# ESense.net
KiCad netlist of a schematic drawn in Altium Designer
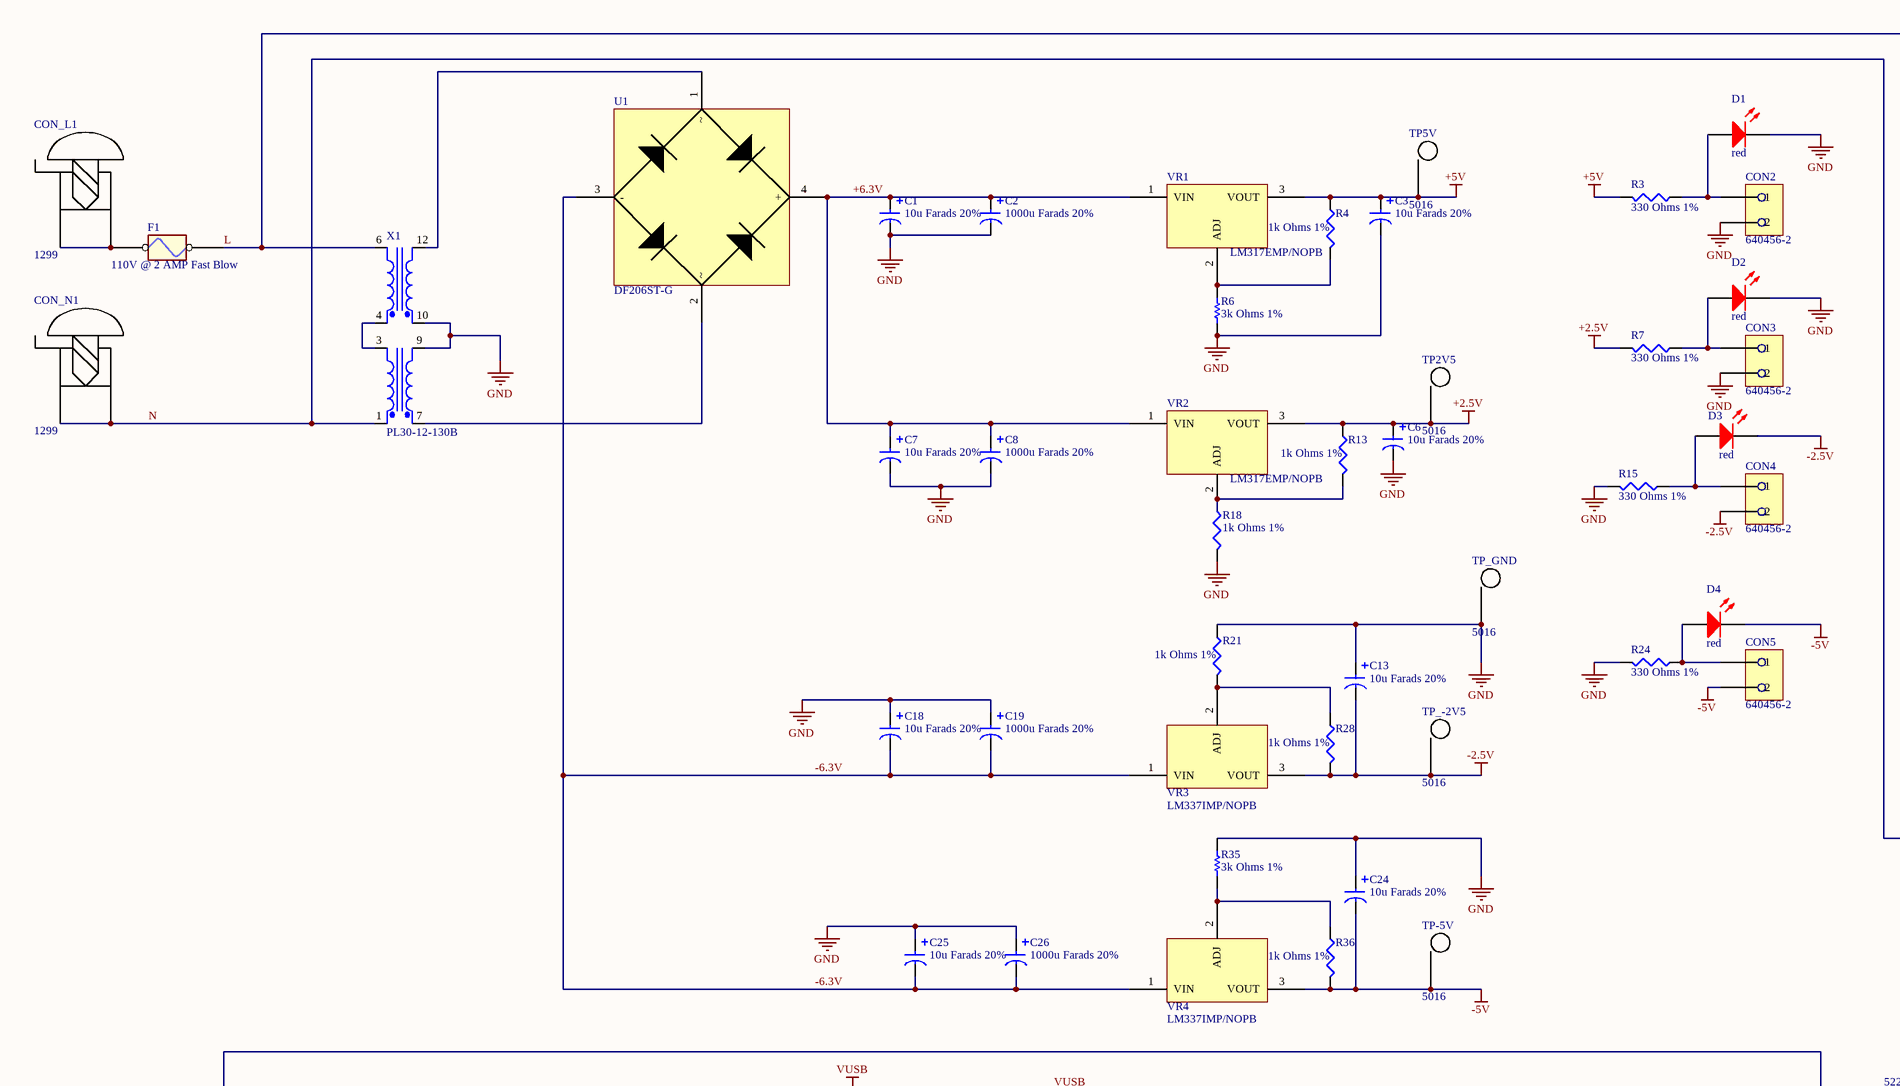
[diagram p0: ESense.SchDoc, top left]
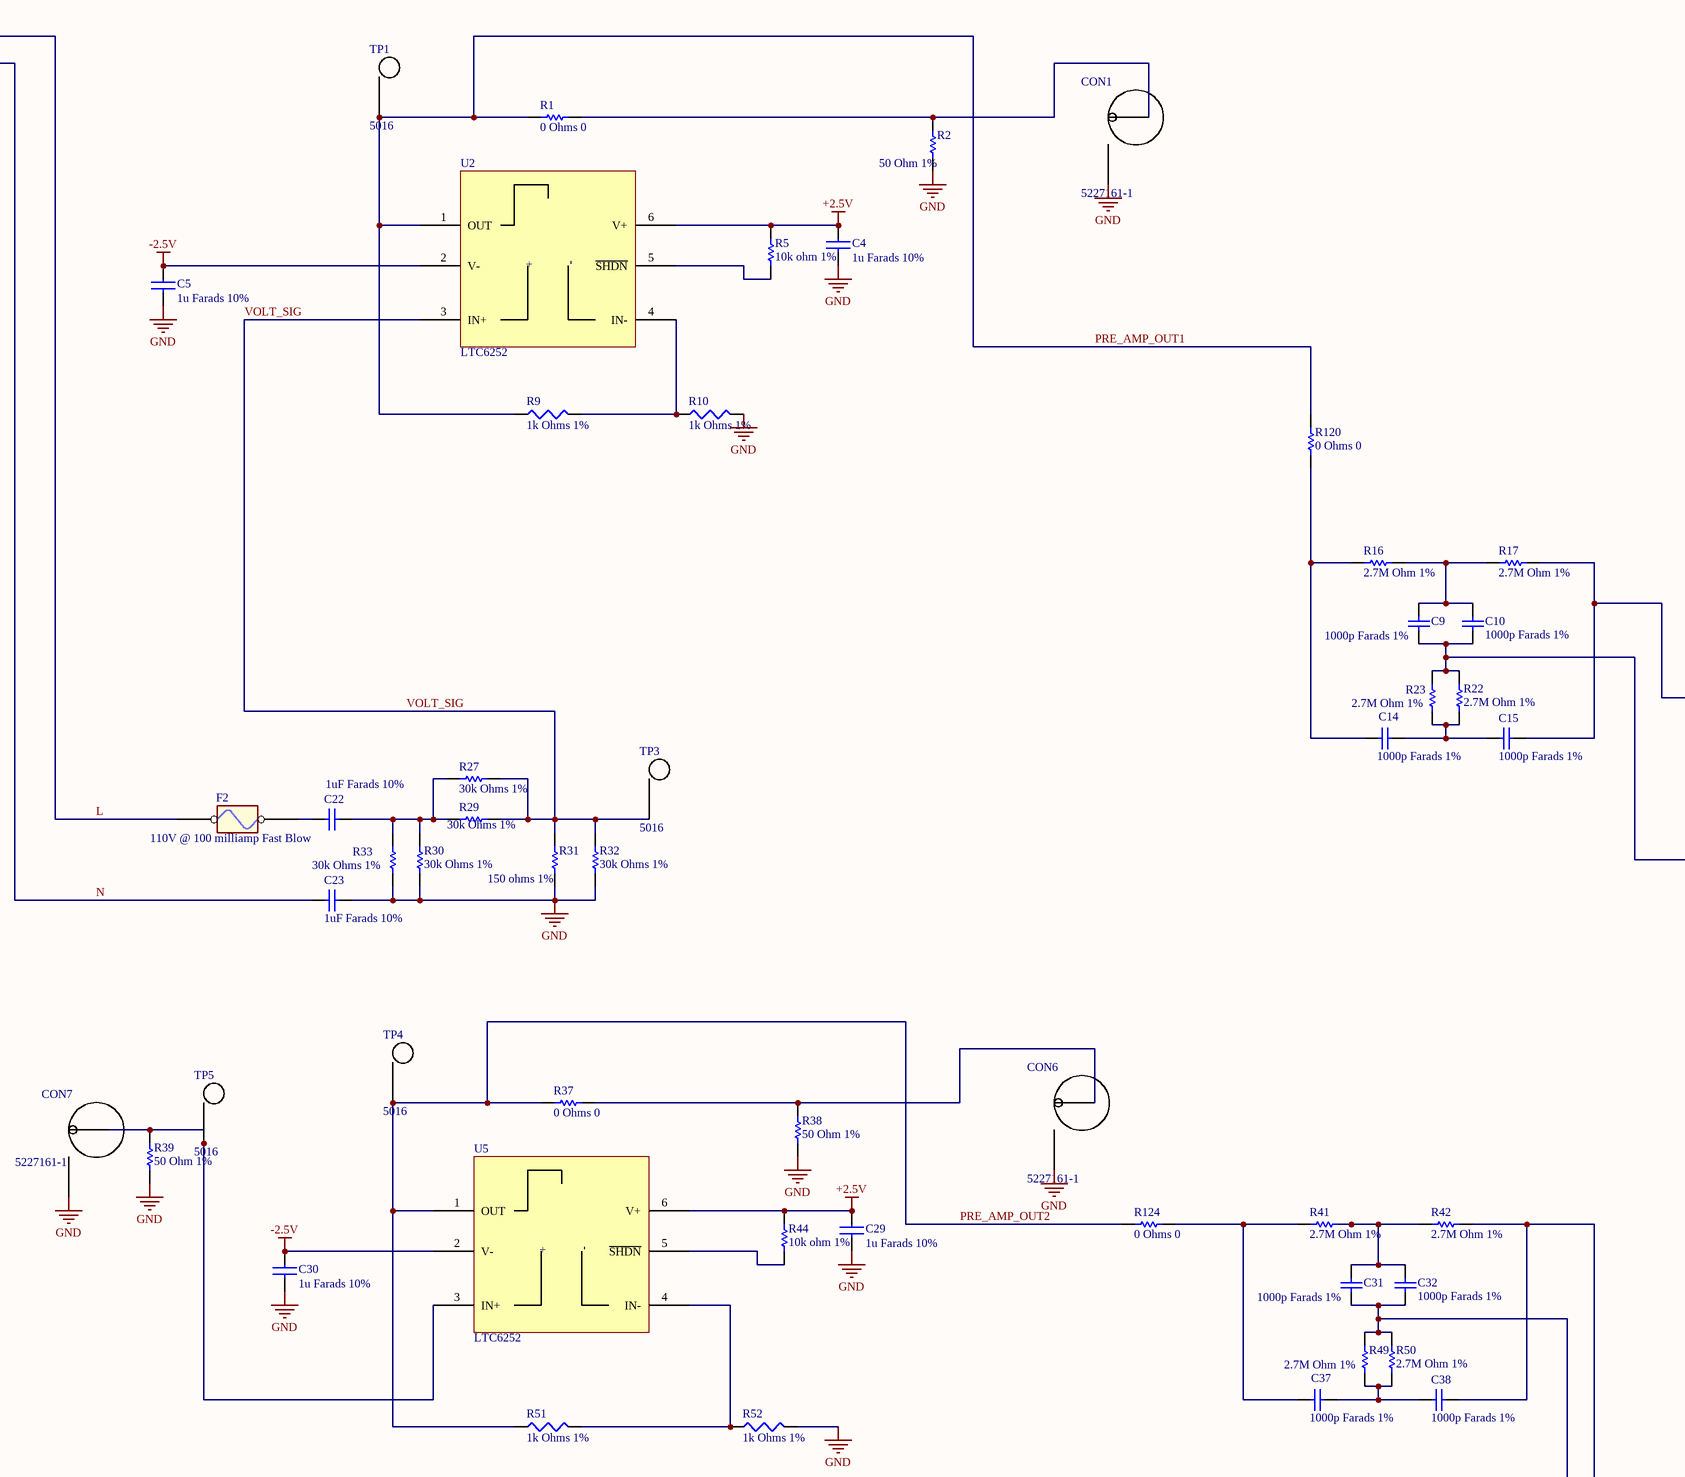
[diagram p1: ESense.SchDoc, top middle]
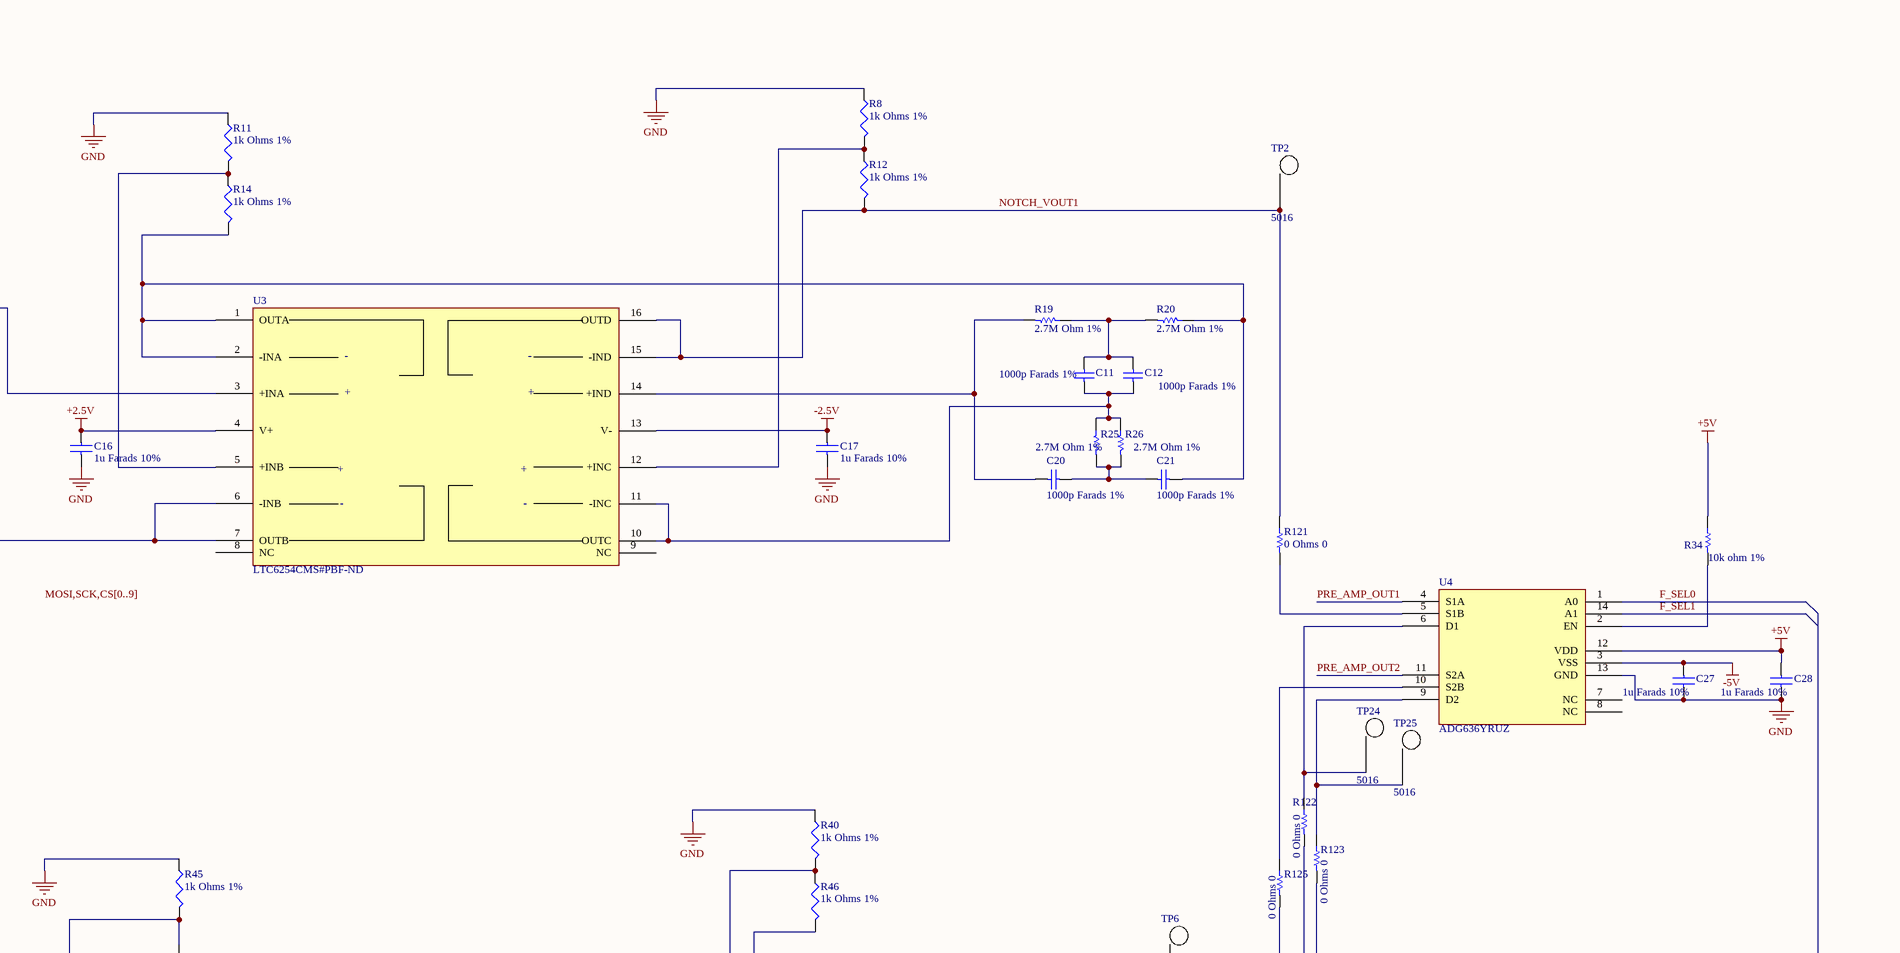
[diagram p2: ESense.SchDoc, top right]
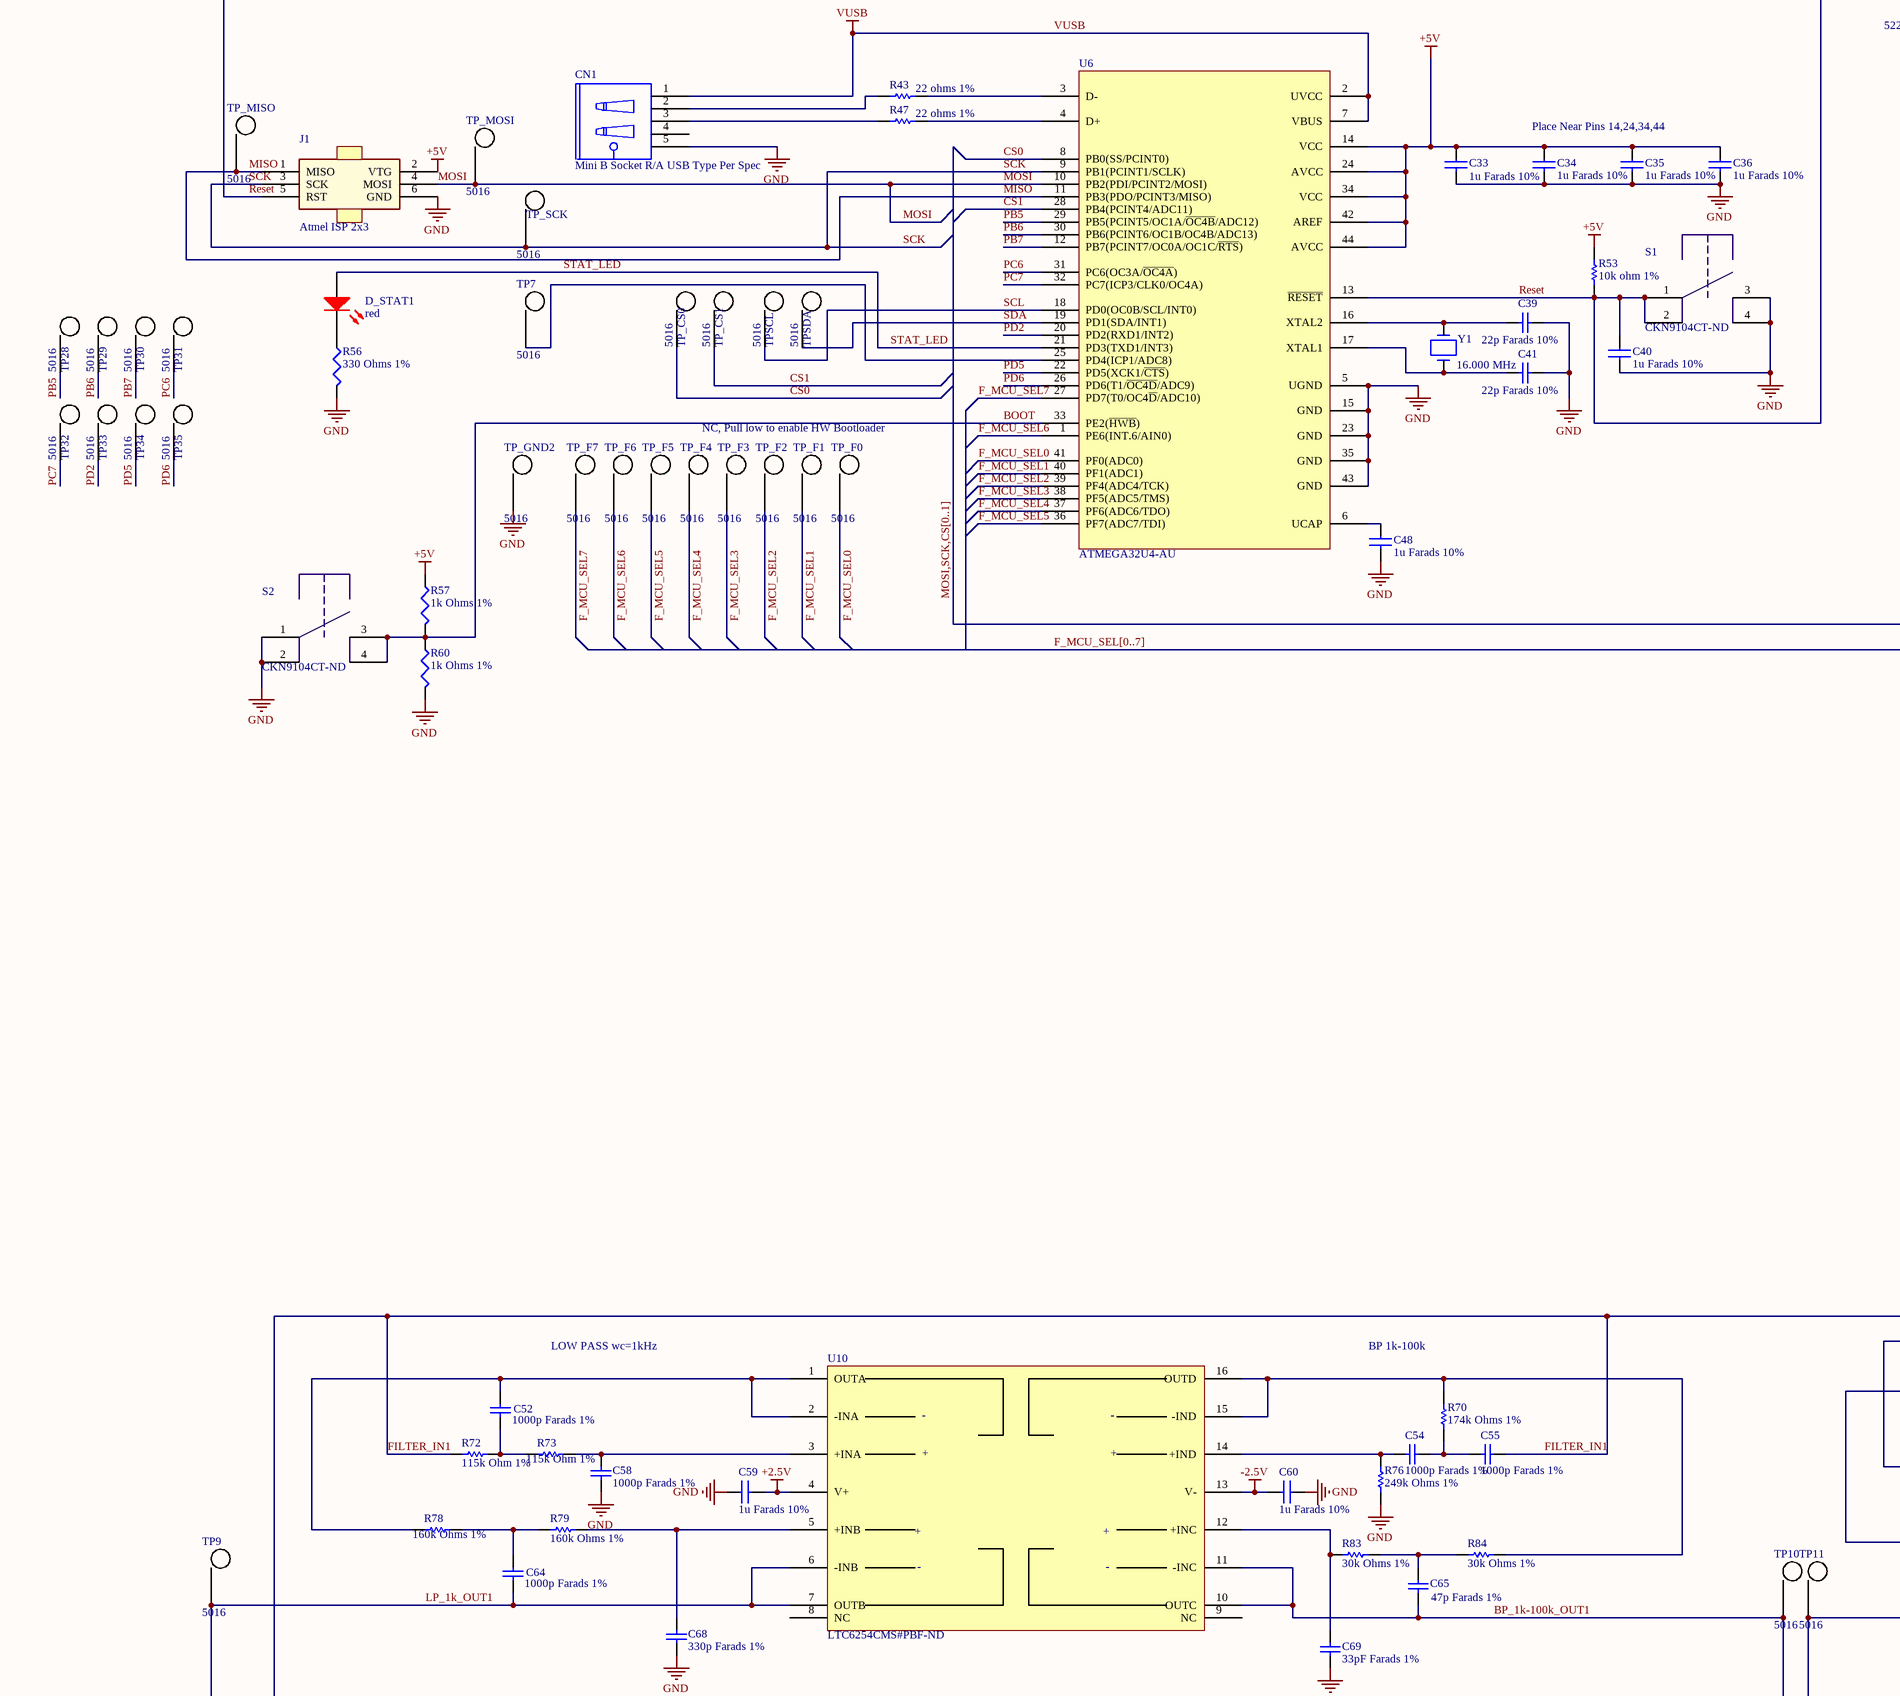
[diagram p3: ESense.SchDoc, centre left]
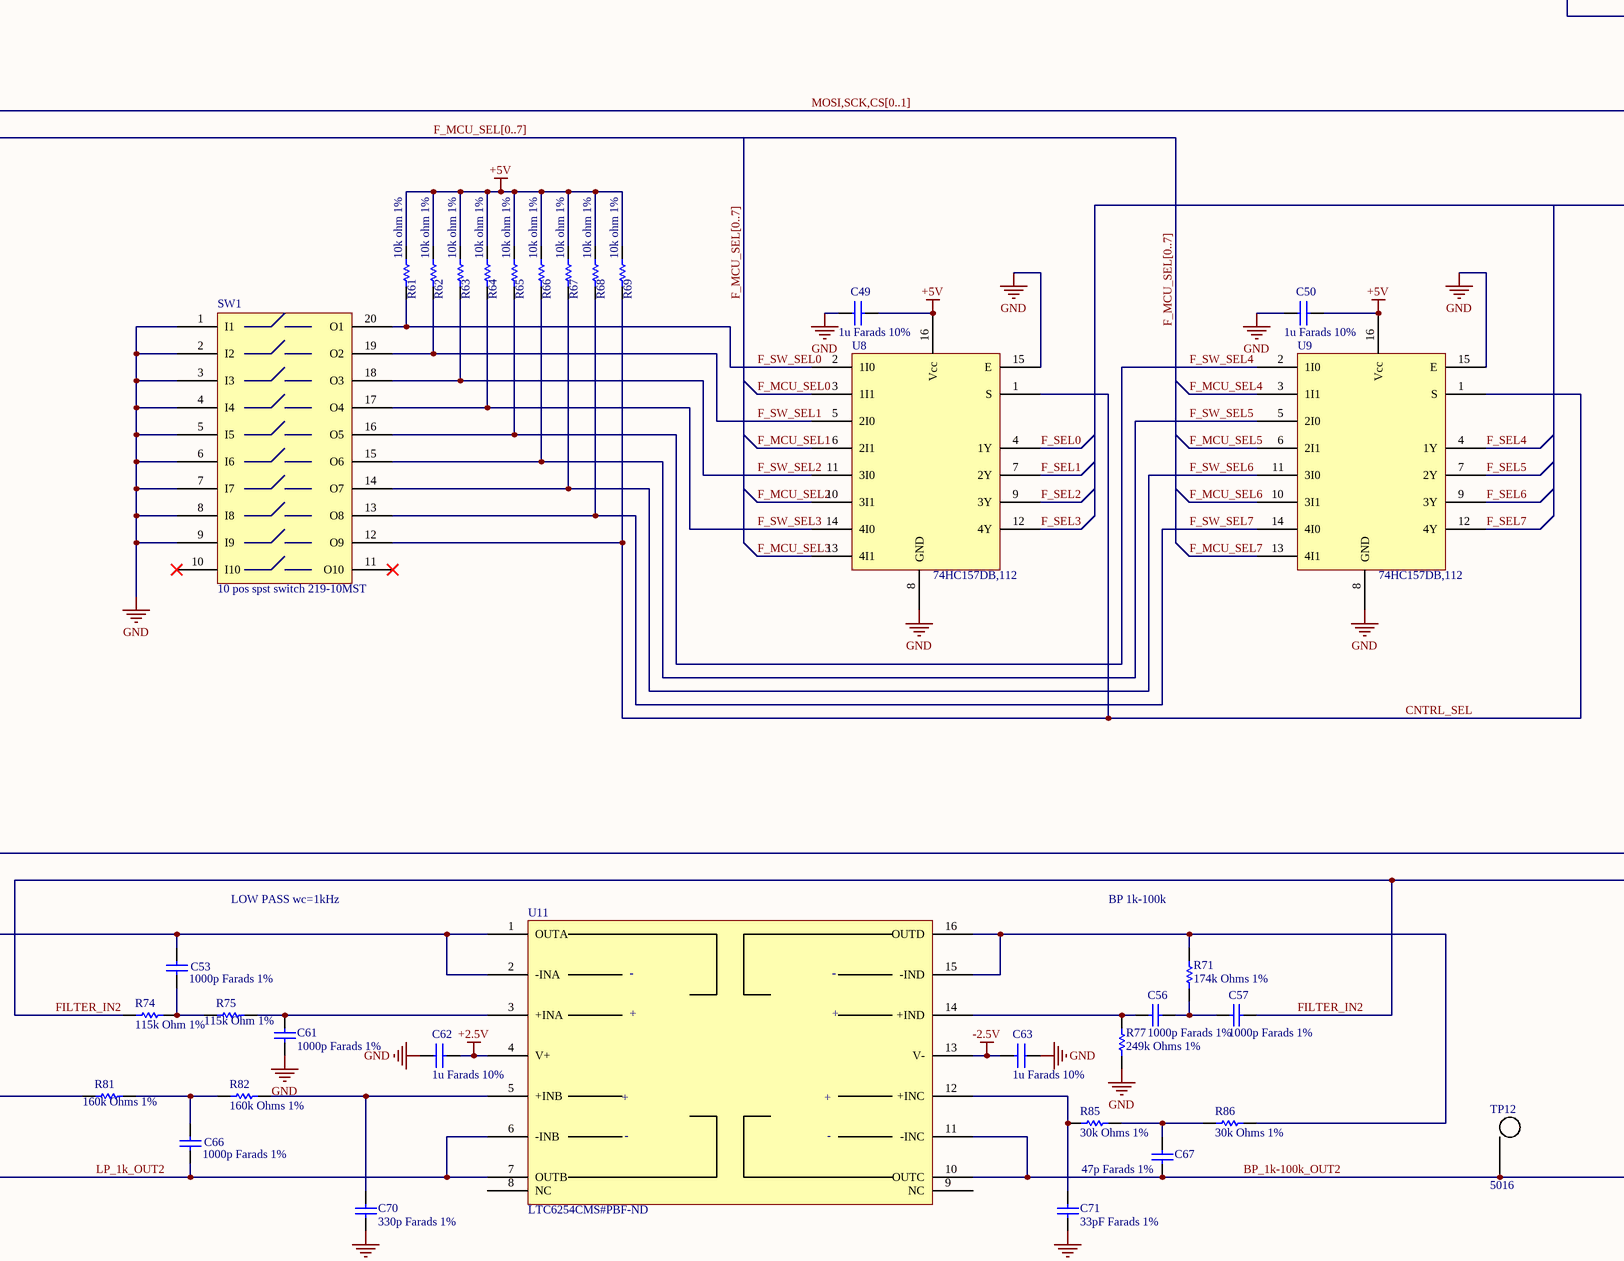
[diagram p4: ESense.SchDoc, centre middle]
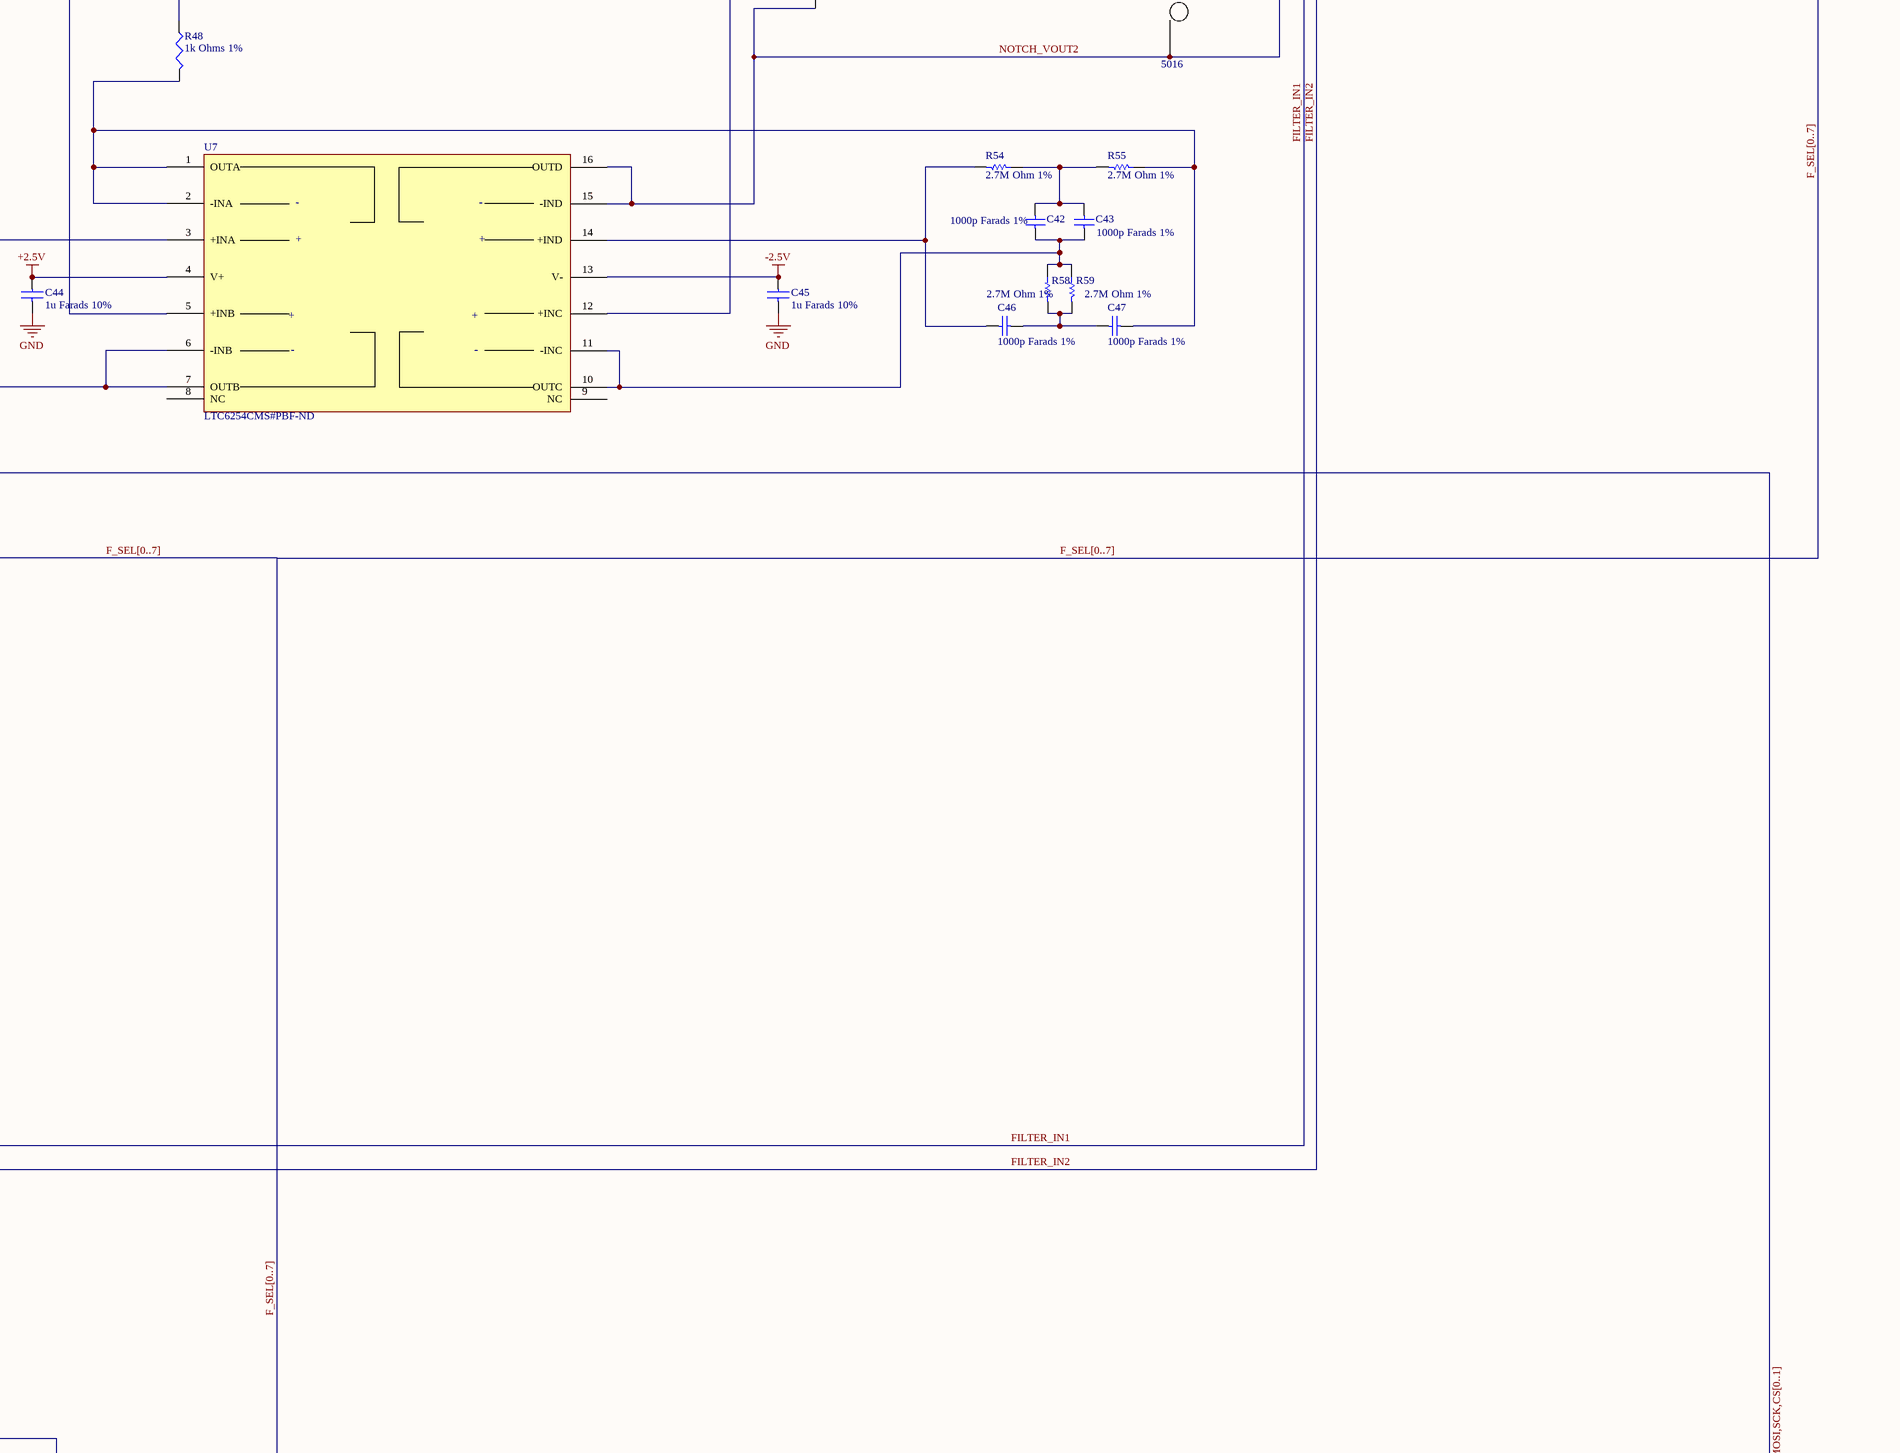
[diagram p5: ESense.SchDoc, centre right]
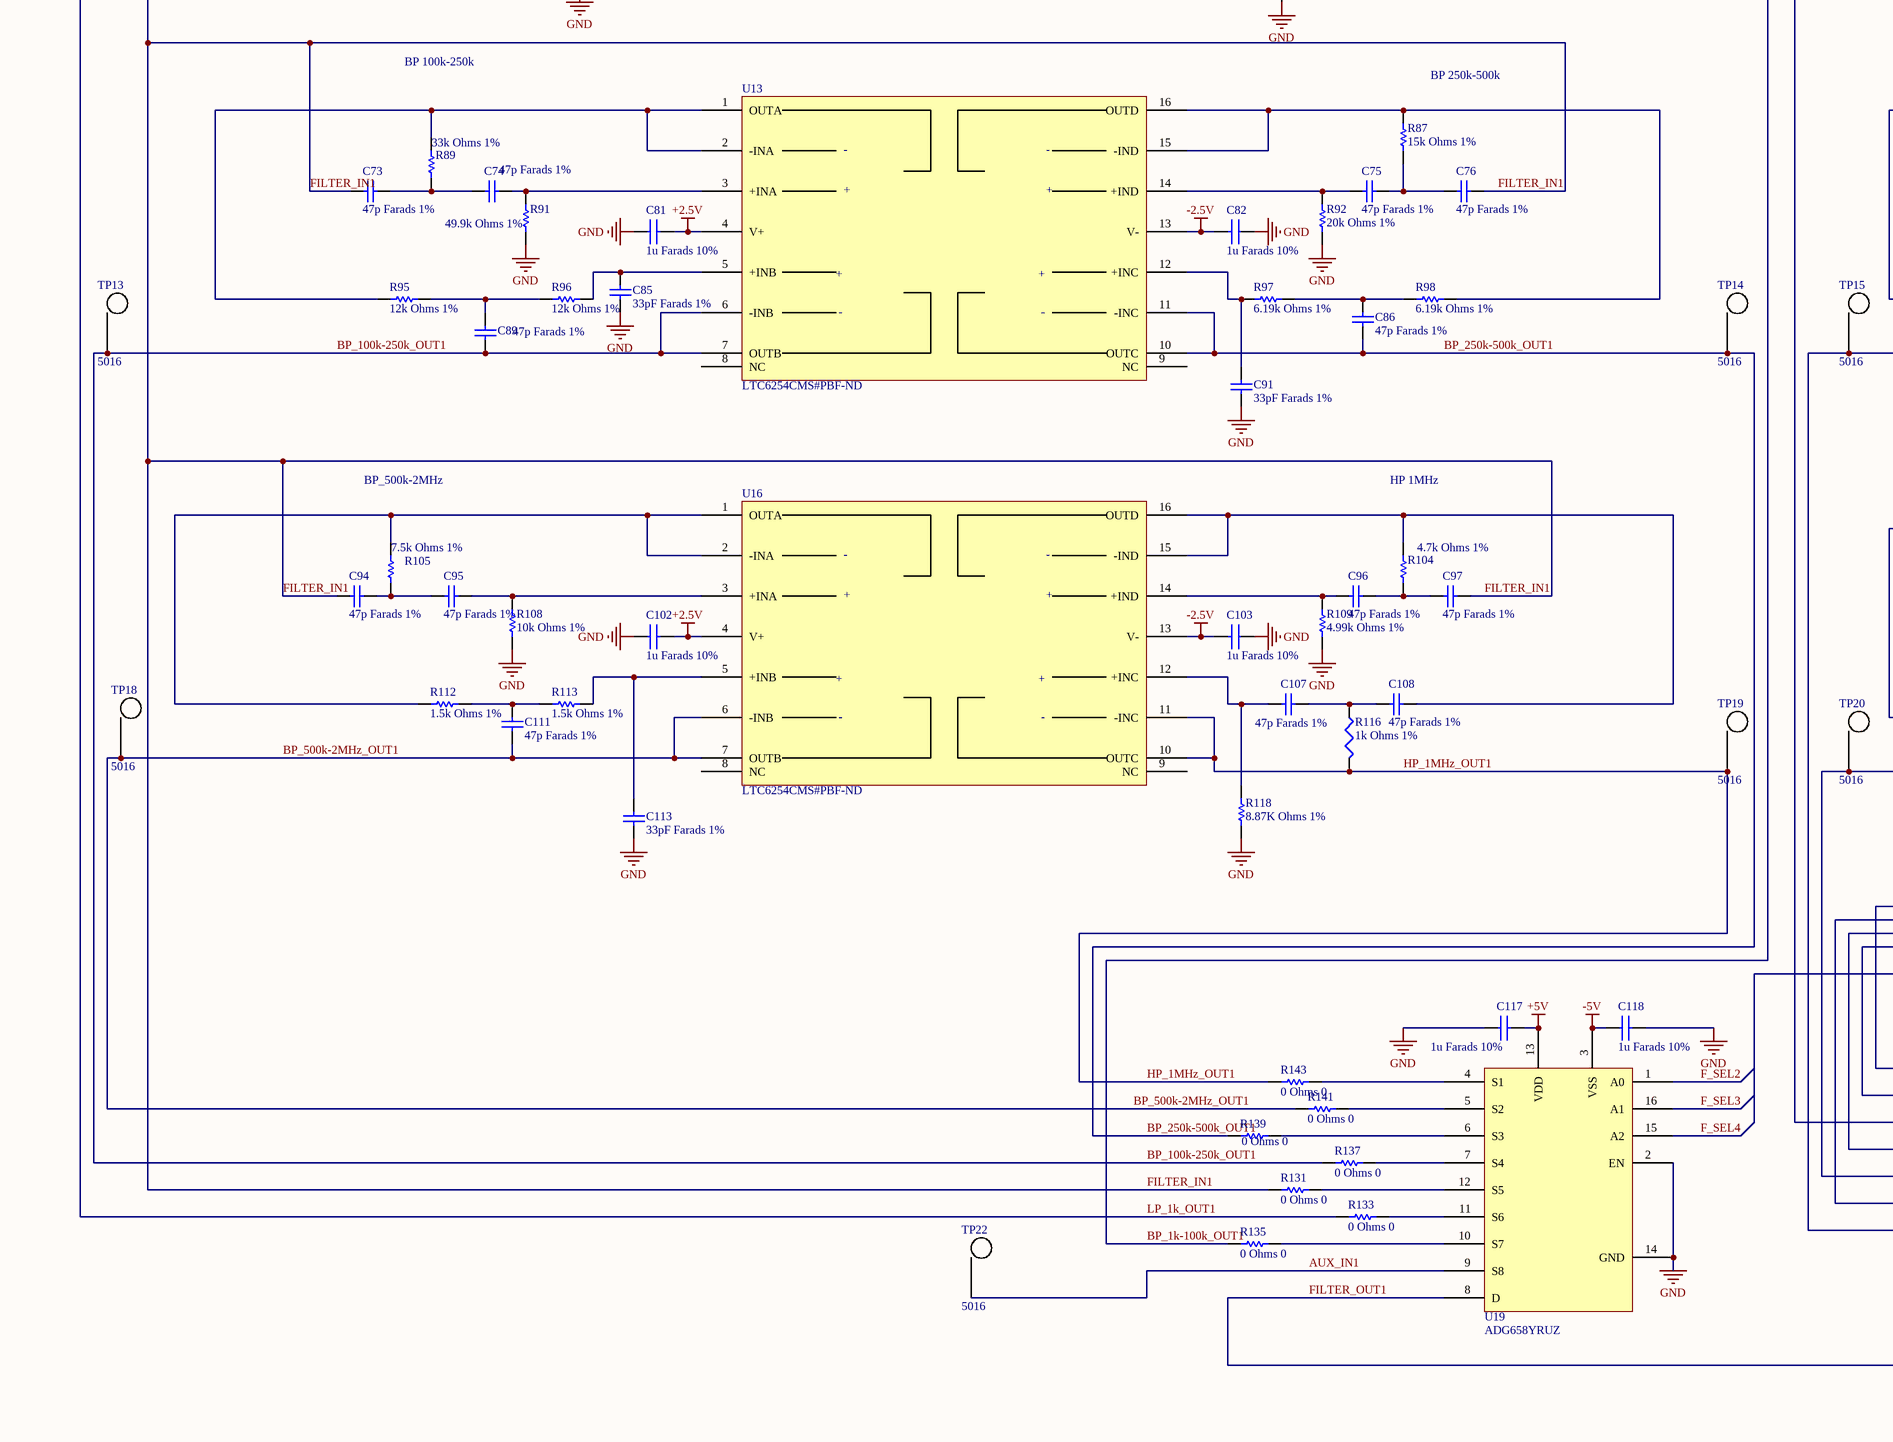
[diagram p6: ESense.SchDoc, bottom left]
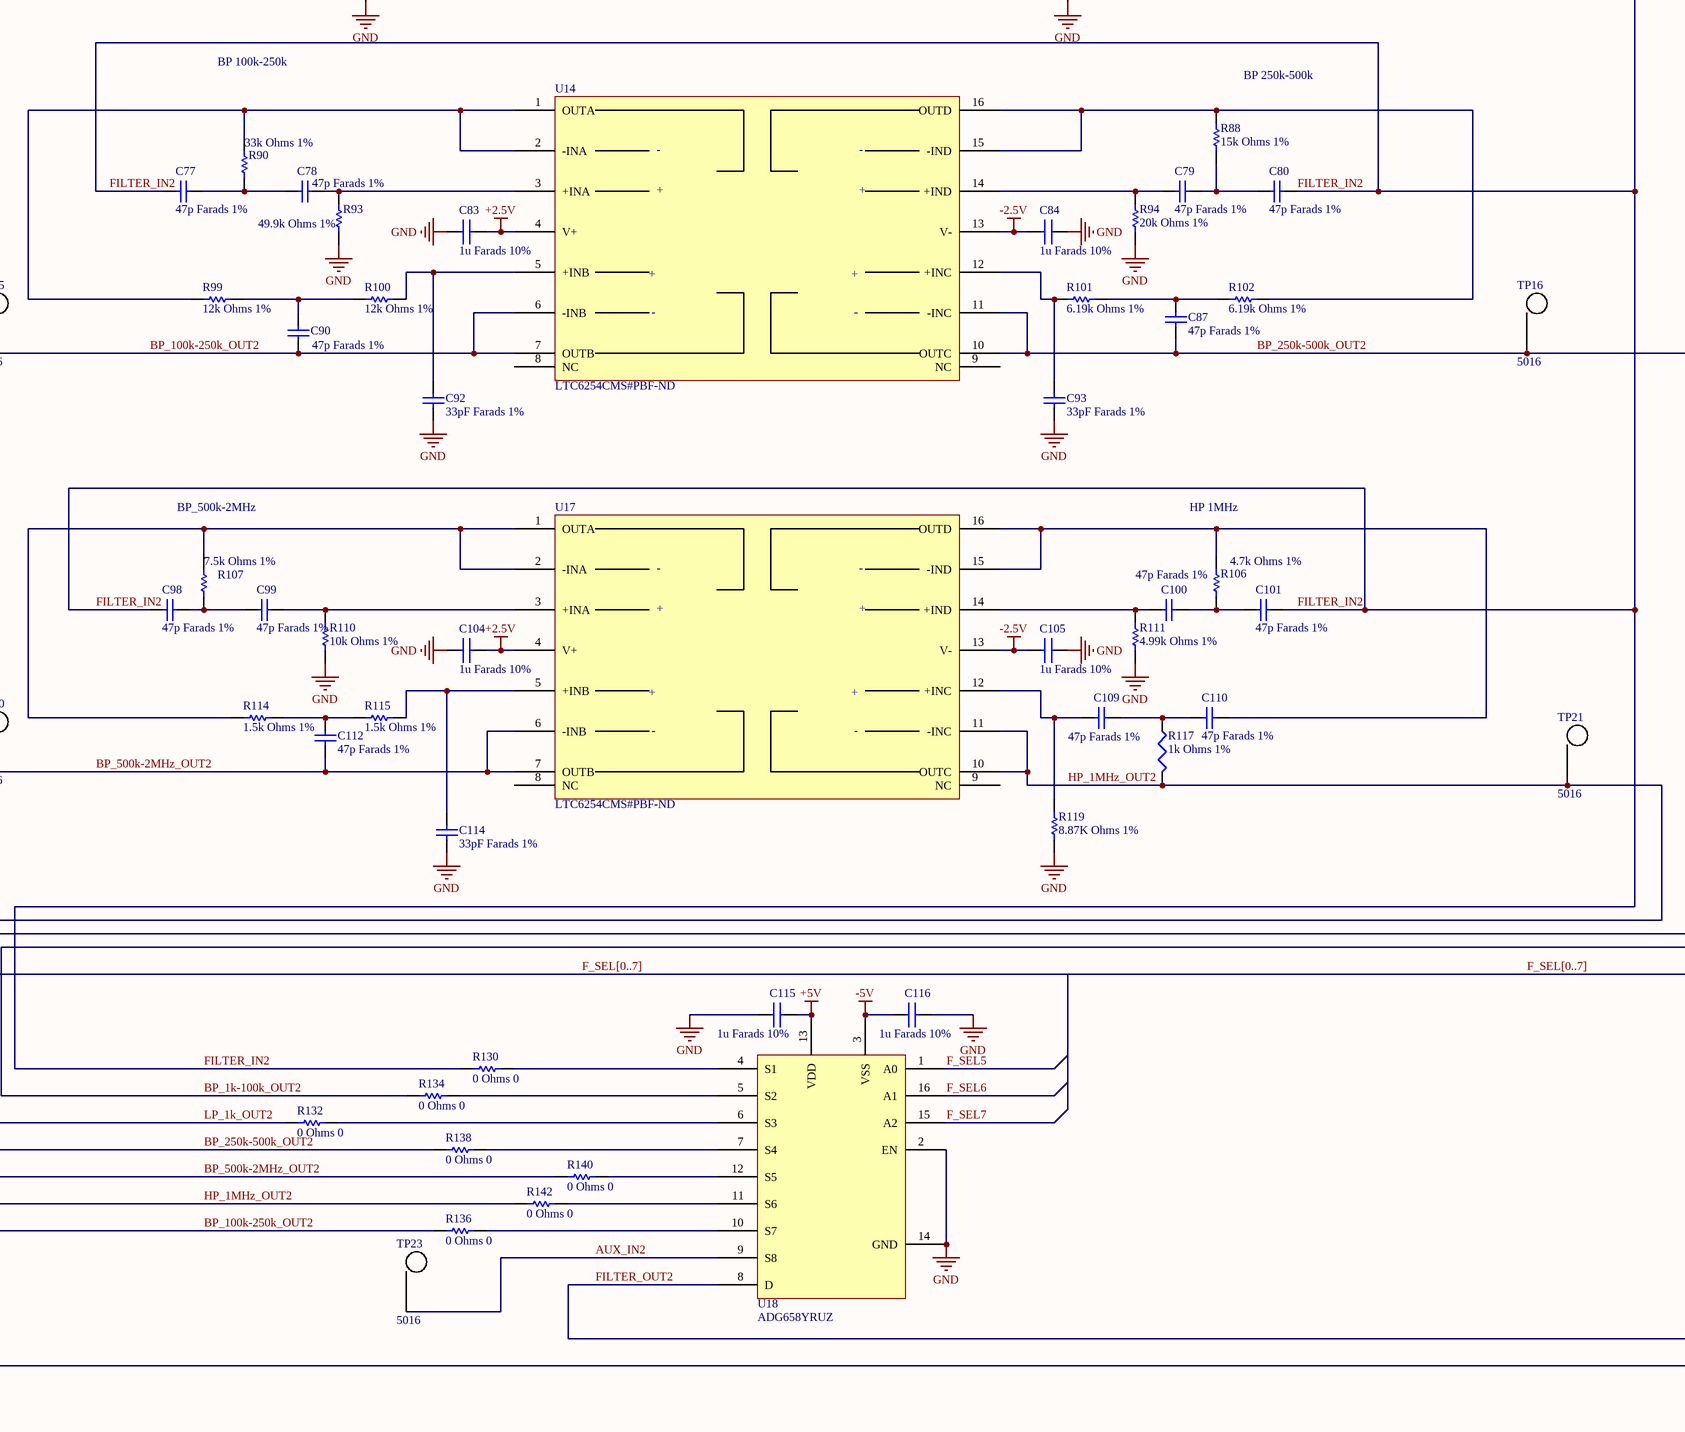
[diagram p7: ESense.SchDoc, bottom middle]
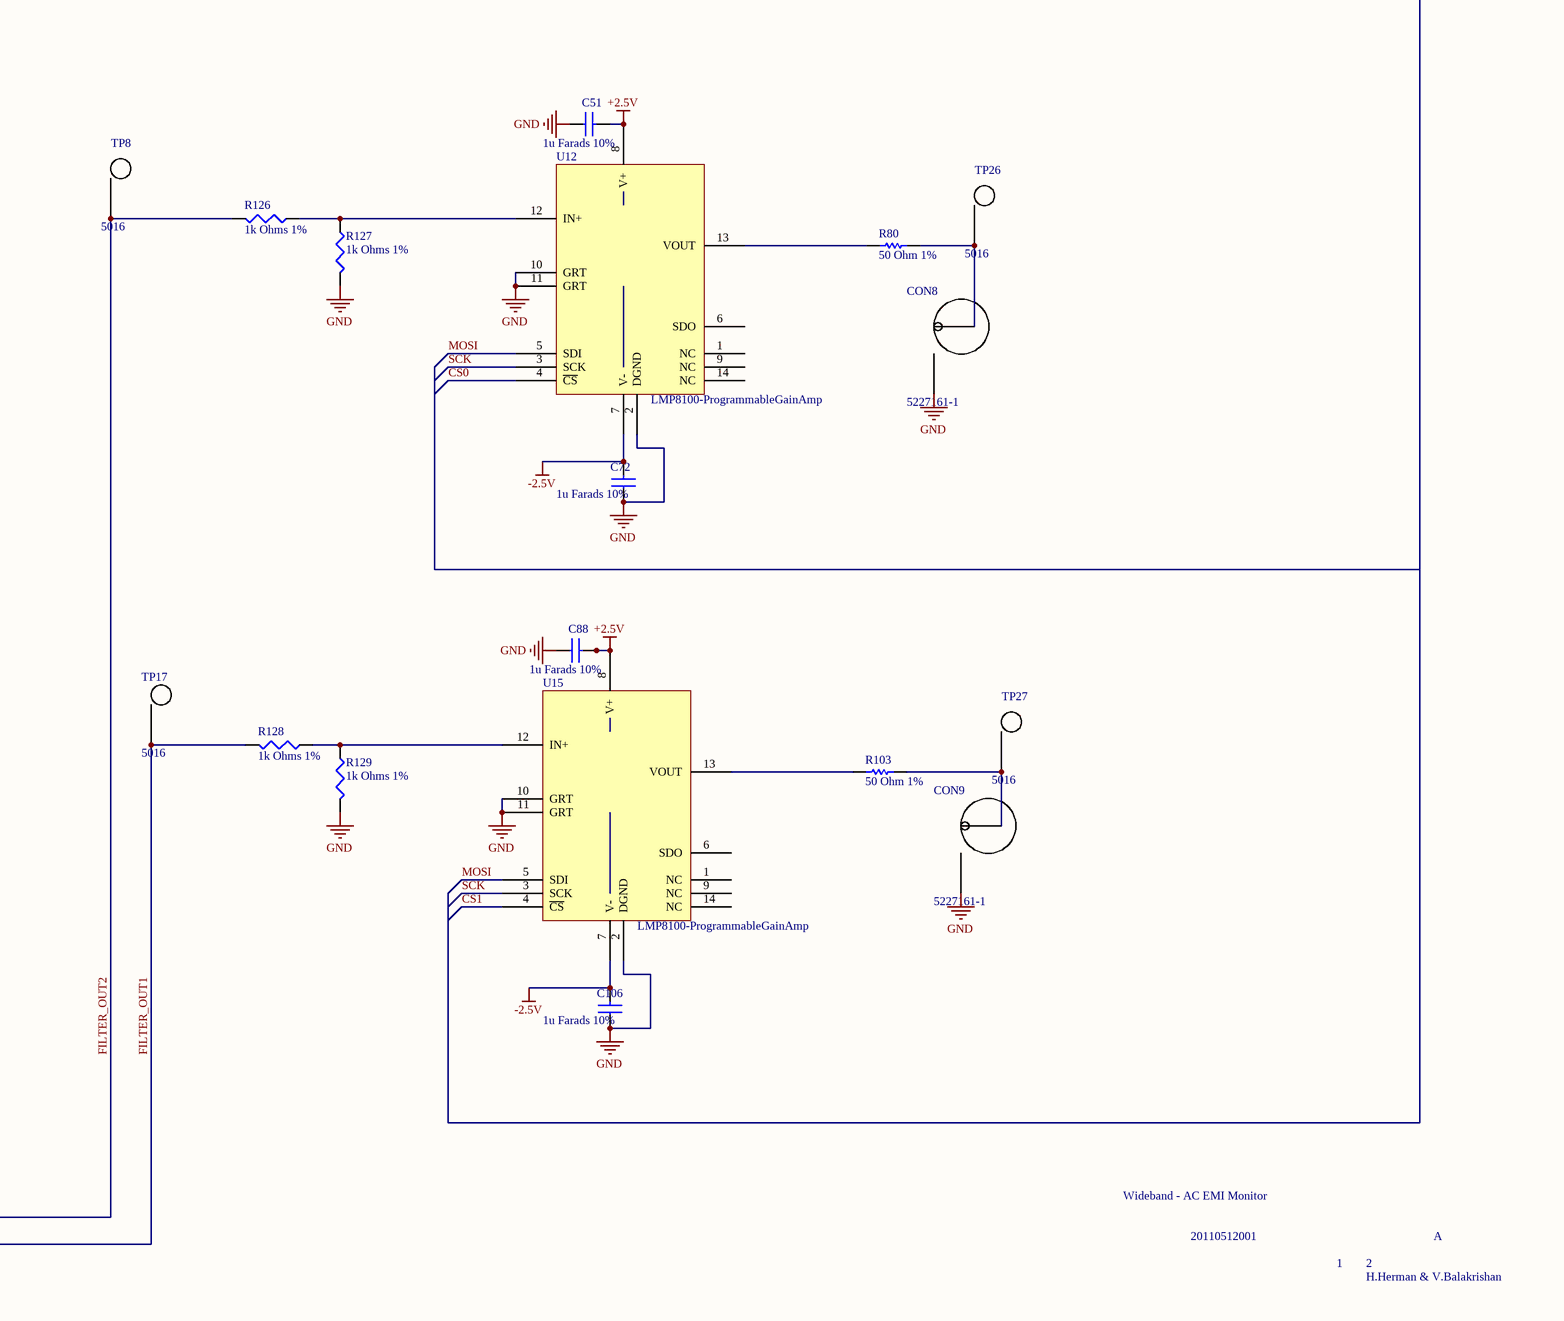
[diagram p8: ESense.SchDoc, bottom right]

(export (version "E")
  (design (tool "Eeschema 10.0.6"))
  (components
    (comp (ref "C1")
      (value "10u Farads 20%")
      (footprint "CAP-SMD-POL-5mmDia")
      (description "capacitor, case c, 10uf, 25v; application:general purpose;")
      (fields (field (name "MFRPARTNUM") "EEE1EA100SR"))
      (libsource (lib "FriedParts") (part "CAP_POL"))
    )
    (comp (ref "C2")
      (value "1000u Farads 20%")
      (footprint "CAP-CAN-SMD-POL-12.5mmDia")
      (description "cap aluminum 1000uf 25vdc 20% 12.5 x 13.5mm smd 1100ma 5000")
      (fields (field (name "MFRPARTNUM") "EEV-FK1E102Q"))
      (libsource (lib "FriedParts") (part "CAP_POL"))
    )
    (comp (ref "C3")
      (value "10u Farads 20%")
      (footprint "CAP-SMD-POL-5mmDia")
      (description "capacitor, case c, 10uf, 25v; application:general purpose;")
      (fields (field (name "MFRPARTNUM") "EEE1EA100SR"))
      (libsource (lib "FriedParts") (part "CAP_POL"))
    )
    (comp (ref "C4")
      (value "1u Farads 10%")
      (footprint "SM/C_0603")
      (description "CAP CER 1.0UF 10V 10% X5R 0603")
      (fields (field (name "MFRPARTNUM") "GRM188R61A105KA61D"))
      (libsource (lib "FriedParts") (part "CAP NP"))
    )
    (comp (ref "C5")
      (value "1u Farads 10%")
      (footprint "SM/C_0603")
      (description "CAP CER 1.0UF 10V 10% X5R 0603")
      (fields (field (name "MFRPARTNUM") "GRM188R61A105KA61D"))
      (libsource (lib "FriedParts") (part "CAP NP"))
    )
    (comp (ref "C6")
      (value "10u Farads 20%")
      (footprint "CAP-SMD-POL-5mmDia")
      (description "capacitor, case c, 10uf, 25v; application:general purpose;")
      (fields (field (name "MFRPARTNUM") "EEE1EA100SR"))
      (libsource (lib "FriedParts") (part "CAP_POL"))
    )
    (comp (ref "C7")
      (value "10u Farads 20%")
      (footprint "CAP-SMD-POL-5mmDia")
      (description "capacitor, case c, 10uf, 25v; application:general purpose;")
      (fields (field (name "MFRPARTNUM") "EEE1EA100SR"))
      (libsource (lib "FriedParts") (part "CAP_POL"))
    )
    (comp (ref "C8")
      (value "1000u Farads 20%")
      (footprint "CAP-CAN-SMD-POL-12.5mmDia")
      (description "cap aluminum 1000uf 25vdc 20% 12.5 x 13.5mm smd 1100ma 5000")
      (fields (field (name "MFRPARTNUM") "EEV-FK1E102Q"))
      (libsource (lib "FriedParts") (part "CAP_POL"))
    )
    (comp (ref "C9")
      (value "1000p Farads 1%")
      (footprint "SM/C_0603")
      (description "capacitor ceramic 1000pf, 50v, c0g, 0603; dielectric")
      (fields (field (name "MFRPARTNUM") "06035A102FAT2A"))
      (libsource (lib "FriedParts") (part "CAP"))
    )
    (comp (ref "C10")
      (value "1000p Farads 1%")
      (footprint "SM/C_0603")
      (description "capacitor ceramic 1000pf, 50v, c0g, 0603; dielectric")
      (fields (field (name "MFRPARTNUM") "06035A102FAT2A"))
      (libsource (lib "FriedParts") (part "CAP"))
    )
    (comp (ref "C11")
      (value "1000p Farads 1%")
      (footprint "SM/C_0603")
      (description "capacitor ceramic 1000pf, 50v, c0g, 0603; dielectric")
      (fields (field (name "MFRPARTNUM") "06035A102FAT2A"))
      (libsource (lib "FriedParts") (part "CAP"))
    )
    (comp (ref "C12")
      (value "1000p Farads 1%")
      (footprint "SM/C_0603")
      (description "capacitor ceramic 1000pf, 50v, c0g, 0603; dielectric")
      (fields (field (name "MFRPARTNUM") "06035A102FAT2A"))
      (libsource (lib "FriedParts") (part "CAP"))
    )
    (comp (ref "C13")
      (value "10u Farads 20%")
      (footprint "CAP-SMD-POL-5mmDia")
      (description "capacitor, case c, 10uf, 25v; application:general purpose;")
      (fields (field (name "MFRPARTNUM") "EEE1EA100SR"))
      (libsource (lib "FriedParts") (part "CAP_POL"))
    )
    (comp (ref "C14")
      (value "1000p Farads 1%")
      (footprint "SM/C_0603")
      (description "capacitor ceramic 1000pf, 50v, c0g, 0603; dielectric")
      (fields (field (name "MFRPARTNUM") "06035A102FAT2A"))
      (libsource (lib "FriedParts") (part "CAP"))
    )
    (comp (ref "C15")
      (value "1000p Farads 1%")
      (footprint "SM/C_0603")
      (description "capacitor ceramic 1000pf, 50v, c0g, 0603; dielectric")
      (fields (field (name "MFRPARTNUM") "06035A102FAT2A"))
      (libsource (lib "FriedParts") (part "CAP"))
    )
    (comp (ref "C16")
      (value "1u Farads 10%")
      (footprint "SM/C_0603")
      (description "CAP CER 1.0UF 10V 10% X5R 0603")
      (fields (field (name "MFRPARTNUM") "GRM188R61A105KA61D"))
      (libsource (lib "FriedParts") (part "CAP NP"))
    )
    (comp (ref "C17")
      (value "1u Farads 10%")
      (footprint "SM/C_0603")
      (description "CAP CER 1.0UF 10V 10% X5R 0603")
      (fields (field (name "MFRPARTNUM") "GRM188R61A105KA61D"))
      (libsource (lib "FriedParts") (part "CAP NP"))
    )
    (comp (ref "C18")
      (value "10u Farads 20%")
      (footprint "CAP-SMD-POL-5mmDia")
      (description "capacitor, case c, 10uf, 25v; application:general purpose;")
      (fields (field (name "MFRPARTNUM") "EEE1EA100SR"))
      (libsource (lib "FriedParts") (part "CAP_POL"))
    )
    (comp (ref "C19")
      (value "1000u Farads 20%")
      (footprint "CAP-CAN-SMD-POL-12.5mmDia")
      (description "cap aluminum 1000uf 25vdc 20% 12.5 x 13.5mm smd 1100ma 5000")
      (fields (field (name "MFRPARTNUM") "EEV-FK1E102Q"))
      (libsource (lib "FriedParts") (part "CAP_POL"))
    )
    (comp (ref "C20")
      (value "1000p Farads 1%")
      (footprint "SM/C_0603")
      (description "capacitor ceramic 1000pf, 50v, c0g, 0603; dielectric")
      (fields (field (name "MFRPARTNUM") "06035A102FAT2A"))
      (libsource (lib "FriedParts") (part "CAP"))
    )
    (comp (ref "C21")
      (value "1000p Farads 1%")
      (footprint "SM/C_0603")
      (description "capacitor ceramic 1000pf, 50v, c0g, 0603; dielectric")
      (fields (field (name "MFRPARTNUM") "06035A102FAT2A"))
      (libsource (lib "FriedParts") (part "CAP"))
    )
    (comp (ref "C22")
      (value "1uF Farads 10%")
      (footprint "Y2-Caps-Epocs-1uF-10%")
      (description "Y2 Caps 1uF Epocs")
      (fields (field (name "MFRPARTNUM") "B32026B3105K"))
      (libsource (lib "FriedParts") (part "CAP"))
    )
    (comp (ref "C23")
      (value "1uF Farads 10%")
      (footprint "Y2-Caps-Epocs-1uF-10%")
      (description "Y2 Caps 1uF Epocs")
      (fields (field (name "MFRPARTNUM") "B32026B3105K"))
      (libsource (lib "FriedParts") (part "CAP"))
    )
    (comp (ref "C24")
      (value "10u Farads 20%")
      (footprint "CAP-SMD-POL-5mmDia")
      (description "capacitor, case c, 10uf, 25v; application:general purpose;")
      (fields (field (name "MFRPARTNUM") "EEE1EA100SR"))
      (libsource (lib "FriedParts") (part "CAP_POL"))
    )
    (comp (ref "C25")
      (value "10u Farads 20%")
      (footprint "CAP-SMD-POL-5mmDia")
      (description "capacitor, case c, 10uf, 25v; application:general purpose;")
      (fields (field (name "MFRPARTNUM") "EEE1EA100SR"))
      (libsource (lib "FriedParts") (part "CAP_POL"))
    )
    (comp (ref "C26")
      (value "1000u Farads 20%")
      (footprint "CAP-CAN-SMD-POL-12.5mmDia")
      (description "cap aluminum 1000uf 25vdc 20% 12.5 x 13.5mm smd 1100ma 5000")
      (fields (field (name "MFRPARTNUM") "EEV-FK1E102Q"))
      (libsource (lib "FriedParts") (part "CAP_POL"))
    )
    (comp (ref "C27")
      (value "1u Farads 10%")
      (footprint "SM/C_0603")
      (description "CAP CER 1.0UF 10V 10% X5R 0603")
      (fields (field (name "MFRPARTNUM") "GRM188R61A105KA61D"))
      (libsource (lib "FriedParts") (part "CAP NP"))
    )
    (comp (ref "C28")
      (value "1u Farads 10%")
      (footprint "SM/C_0603")
      (description "CAP CER 1.0UF 10V 10% X5R 0603")
      (fields (field (name "MFRPARTNUM") "GRM188R61A105KA61D"))
      (libsource (lib "FriedParts") (part "CAP NP"))
    )
    (comp (ref "C29")
      (value "1u Farads 10%")
      (footprint "SM/C_0603")
      (description "CAP CER 1.0UF 10V 10% X5R 0603")
      (fields (field (name "MFRPARTNUM") "GRM188R61A105KA61D"))
      (libsource (lib "FriedParts") (part "CAP NP"))
    )
    (comp (ref "C30")
      (value "1u Farads 10%")
      (footprint "SM/C_0603")
      (description "CAP CER 1.0UF 10V 10% X5R 0603")
      (fields (field (name "MFRPARTNUM") "GRM188R61A105KA61D"))
      (libsource (lib "FriedParts") (part "CAP NP"))
    )
    (comp (ref "C31")
      (value "1000p Farads 1%")
      (footprint "SM/C_0603")
      (description "capacitor ceramic 1000pf, 50v, c0g, 0603; dielectric")
      (fields (field (name "MFRPARTNUM") "06035A102FAT2A"))
      (libsource (lib "FriedParts") (part "CAP"))
    )
    (comp (ref "C32")
      (value "1000p Farads 1%")
      (footprint "SM/C_0603")
      (description "capacitor ceramic 1000pf, 50v, c0g, 0603; dielectric")
      (fields (field (name "MFRPARTNUM") "06035A102FAT2A"))
      (libsource (lib "FriedParts") (part "CAP"))
    )
    (comp (ref "C33")
      (value "1u Farads 10%")
      (footprint "SM/C_0603")
      (description "CAP CER 1.0UF 10V 10% X5R 0603")
      (fields (field (name "MFRPARTNUM") "GRM188R61A105KA61D"))
      (libsource (lib "FriedParts") (part "CAP NP"))
    )
    (comp (ref "C34")
      (value "1u Farads 10%")
      (footprint "SM/C_0603")
      (description "CAP CER 1.0UF 10V 10% X5R 0603")
      (fields (field (name "MFRPARTNUM") "GRM188R61A105KA61D"))
      (libsource (lib "FriedParts") (part "CAP NP"))
    )
    (comp (ref "C35")
      (value "1u Farads 10%")
      (footprint "SM/C_0603")
      (description "CAP CER 1.0UF 10V 10% X5R 0603")
      (fields (field (name "MFRPARTNUM") "GRM188R61A105KA61D"))
      (libsource (lib "FriedParts") (part "CAP NP"))
    )
    (comp (ref "C36")
      (value "1u Farads 10%")
      (footprint "SM/C_0603")
      (description "CAP CER 1.0UF 10V 10% X5R 0603")
      (fields (field (name "MFRPARTNUM") "GRM188R61A105KA61D"))
      (libsource (lib "FriedParts") (part "CAP NP"))
    )
    (comp (ref "C37")
      (value "1000p Farads 1%")
      (footprint "SM/C_0603")
      (description "capacitor ceramic 1000pf, 50v, c0g, 0603; dielectric")
      (fields (field (name "MFRPARTNUM") "06035A102FAT2A"))
      (libsource (lib "FriedParts") (part "CAP"))
    )
    (comp (ref "C38")
      (value "1000p Farads 1%")
      (footprint "SM/C_0603")
      (description "capacitor ceramic 1000pf, 50v, c0g, 0603; dielectric")
      (fields (field (name "MFRPARTNUM") "06035A102FAT2A"))
      (libsource (lib "FriedParts") (part "CAP"))
    )
    (comp (ref "C39")
      (value "22p Farads 10%")
      (footprint "SM/C_0603")
      (description "ceramic multilayer capacitor; capacitor type:general")
      (fields (field (name "MFRPARTNUM") "06031A220KAT2A"))
      (libsource (lib "FriedParts") (part "CAP"))
    )
    (comp (ref "C40")
      (value "1u Farads 10%")
      (footprint "SM/C_0603")
      (description "CAP CER 1.0UF 10V 10% X5R 0603")
      (fields (field (name "MFRPARTNUM") "GRM188R61A105KA61D"))
      (libsource (lib "FriedParts") (part "CAP NP"))
    )
    (comp (ref "C41")
      (value "22p Farads 10%")
      (footprint "SM/C_0603")
      (description "ceramic multilayer capacitor; capacitor type:general")
      (fields (field (name "MFRPARTNUM") "06031A220KAT2A"))
      (libsource (lib "FriedParts") (part "CAP"))
    )
    (comp (ref "C42")
      (value "1000p Farads 1%")
      (footprint "SM/C_0603")
      (description "capacitor ceramic 1000pf, 50v, c0g, 0603; dielectric")
      (fields (field (name "MFRPARTNUM") "06035A102FAT2A"))
      (libsource (lib "FriedParts") (part "CAP"))
    )
    (comp (ref "C43")
      (value "1000p Farads 1%")
      (footprint "SM/C_0603")
      (description "capacitor ceramic 1000pf, 50v, c0g, 0603; dielectric")
      (fields (field (name "MFRPARTNUM") "06035A102FAT2A"))
      (libsource (lib "FriedParts") (part "CAP"))
    )
    (comp (ref "C44")
      (value "1u Farads 10%")
      (footprint "SM/C_0603")
      (description "CAP CER 1.0UF 10V 10% X5R 0603")
      (fields (field (name "MFRPARTNUM") "GRM188R61A105KA61D"))
      (libsource (lib "FriedParts") (part "CAP NP"))
    )
    (comp (ref "C45")
      (value "1u Farads 10%")
      (footprint "SM/C_0603")
      (description "CAP CER 1.0UF 10V 10% X5R 0603")
      (fields (field (name "MFRPARTNUM") "GRM188R61A105KA61D"))
      (libsource (lib "FriedParts") (part "CAP NP"))
    )
    (comp (ref "C46")
      (value "1000p Farads 1%")
      (footprint "SM/C_0603")
      (description "capacitor ceramic 1000pf, 50v, c0g, 0603; dielectric")
      (fields (field (name "MFRPARTNUM") "06035A102FAT2A"))
      (libsource (lib "FriedParts") (part "CAP"))
    )
    (comp (ref "C47")
      (value "1000p Farads 1%")
      (footprint "SM/C_0603")
      (description "capacitor ceramic 1000pf, 50v, c0g, 0603; dielectric")
      (fields (field (name "MFRPARTNUM") "06035A102FAT2A"))
      (libsource (lib "FriedParts") (part "CAP"))
    )
    (comp (ref "C48")
      (value "1u Farads 10%")
      (footprint "SM/C_0603")
      (description "CAP CER 1.0UF 10V 10% X5R 0603")
      (fields (field (name "MFRPARTNUM") "GRM188R61A105KA61D"))
      (libsource (lib "FriedParts") (part "CAP NP"))
    )
    (comp (ref "C49")
      (value "1u Farads 10%")
      (footprint "SM/C_0603")
      (description "CAP CER 1.0UF 10V 10% X5R 0603")
      (fields (field (name "MFRPARTNUM") "GRM188R61A105KA61D"))
      (libsource (lib "FriedParts") (part "CAP NP"))
    )
    (comp (ref "C50")
      (value "1u Farads 10%")
      (footprint "SM/C_0603")
      (description "CAP CER 1.0UF 10V 10% X5R 0603")
      (fields (field (name "MFRPARTNUM") "GRM188R61A105KA61D"))
      (libsource (lib "FriedParts") (part "CAP NP"))
    )
    (comp (ref "C51")
      (value "1u Farads 10%")
      (footprint "SM/C_0603")
      (description "CAP CER 1.0UF 10V 10% X5R 0603")
      (fields (field (name "MFRPARTNUM") "GRM188R61A105KA61D"))
      (libsource (lib "FriedParts") (part "CAP NP"))
    )
    (comp (ref "C52")
      (value "1000p Farads 1%")
      (footprint "SM/C_0603")
      (description "capacitor ceramic 1000pf, 50v, c0g, 0603; dielectric")
      (fields (field (name "MFRPARTNUM") "06035A102FAT2A"))
      (libsource (lib "FriedParts") (part "CAP"))
    )
    (comp (ref "C53")
      (value "1000p Farads 1%")
      (footprint "SM/C_0603")
      (description "capacitor ceramic 1000pf, 50v, c0g, 0603; dielectric")
      (fields (field (name "MFRPARTNUM") "06035A102FAT2A"))
      (libsource (lib "FriedParts") (part "CAP"))
    )
    (comp (ref "C54")
      (value "1000p Farads 1%")
      (footprint "SM/C_0603")
      (description "capacitor ceramic 1000pf, 50v, c0g, 0603; dielectric")
      (fields (field (name "MFRPARTNUM") "06035A102FAT2A"))
      (libsource (lib "FriedParts") (part "CAP"))
    )
    (comp (ref "C55")
      (value "1000p Farads 1%")
      (footprint "SM/C_0603")
      (description "capacitor ceramic 1000pf, 50v, c0g, 0603; dielectric")
      (fields (field (name "MFRPARTNUM") "06035A102FAT2A"))
      (libsource (lib "FriedParts") (part "CAP"))
    )
    (comp (ref "C56")
      (value "1000p Farads 1%")
      (footprint "SM/C_0603")
      (description "capacitor ceramic 1000pf, 50v, c0g, 0603; dielectric")
      (fields (field (name "MFRPARTNUM") "06035A102FAT2A"))
      (libsource (lib "FriedParts") (part "CAP"))
    )
    (comp (ref "C57")
      (value "1000p Farads 1%")
      (footprint "SM/C_0603")
      (description "capacitor ceramic 1000pf, 50v, c0g, 0603; dielectric")
      (fields (field (name "MFRPARTNUM") "06035A102FAT2A"))
      (libsource (lib "FriedParts") (part "CAP"))
    )
    (comp (ref "C58")
      (value "1000p Farads 1%")
      (footprint "SM/C_0603")
      (description "capacitor ceramic 1000pf, 50v, c0g, 0603; dielectric")
      (fields (field (name "MFRPARTNUM") "06035A102FAT2A"))
      (libsource (lib "FriedParts") (part "CAP"))
    )
    (comp (ref "C59")
      (value "1u Farads 10%")
      (footprint "SM/C_0603")
      (description "CAP CER 1.0UF 10V 10% X5R 0603")
      (fields (field (name "MFRPARTNUM") "GRM188R61A105KA61D"))
      (libsource (lib "FriedParts") (part "CAP NP"))
    )
    (comp (ref "C60")
      (value "1u Farads 10%")
      (footprint "SM/C_0603")
      (description "CAP CER 1.0UF 10V 10% X5R 0603")
      (fields (field (name "MFRPARTNUM") "GRM188R61A105KA61D"))
      (libsource (lib "FriedParts") (part "CAP NP"))
    )
    (comp (ref "C61")
      (value "1000p Farads 1%")
      (footprint "SM/C_0603")
      (description "capacitor ceramic 1000pf, 50v, c0g, 0603; dielectric")
      (fields (field (name "MFRPARTNUM") "06035A102FAT2A"))
      (libsource (lib "FriedParts") (part "CAP"))
    )
    (comp (ref "C62")
      (value "1u Farads 10%")
      (footprint "SM/C_0603")
      (description "CAP CER 1.0UF 10V 10% X5R 0603")
      (fields (field (name "MFRPARTNUM") "GRM188R61A105KA61D"))
      (libsource (lib "FriedParts") (part "CAP NP"))
    )
    (comp (ref "C63")
      (value "1u Farads 10%")
      (footprint "SM/C_0603")
      (description "CAP CER 1.0UF 10V 10% X5R 0603")
      (fields (field (name "MFRPARTNUM") "GRM188R61A105KA61D"))
      (libsource (lib "FriedParts") (part "CAP NP"))
    )
    (comp (ref "C64")
      (value "1000p Farads 1%")
      (footprint "SM/C_0603")
      (description "capacitor ceramic 1000pf, 50v, c0g, 0603; dielectric")
      (fields (field (name "MFRPARTNUM") "06035A102FAT2A"))
      (libsource (lib "FriedParts") (part "CAP"))
    )
    (comp (ref "C65")
      (value "47p Farads 1%")
      (footprint "SM/C_0603")
      (description "ceramic multilayer capacitor; capacitor type:general")
      (fields (field (name "MFRPARTNUM") "06031A470FAT2A"))
      (libsource (lib "FriedParts") (part "CAP"))
    )
    (comp (ref "C66")
      (value "1000p Farads 1%")
      (footprint "SM/C_0603")
      (description "capacitor ceramic 1000pf, 50v, c0g, 0603; dielectric")
      (fields (field (name "MFRPARTNUM") "06035A102FAT2A"))
      (libsource (lib "FriedParts") (part "CAP"))
    )
    (comp (ref "C67")
      (value "47p Farads 1%")
      (footprint "SM/C_0603")
      (description "ceramic multilayer capacitor; capacitor type:general")
      (fields (field (name "MFRPARTNUM") "06031A470FAT2A"))
      (libsource (lib "FriedParts") (part "CAP"))
    )
    (comp (ref "C68")
      (value "330p Farads 1%")
      (footprint "SM/C_0603")
      (description "capacitor ceramic 330pf, 50v, c0g, 0603; dielectric")
      (fields (field (name "MFRPARTNUM") "06035A331FAT2A"))
      (libsource (lib "FriedParts") (part "CAP"))
    )
    (comp (ref "C69")
      (value "33pF Farads 1%")
      (footprint "SM/C_0603")
      (description "ceramic multilayer capacitor; capacitor type:general")
      (fields (field (name "MFRPARTNUM") "06031A330FAT2A"))
      (libsource (lib "FriedParts") (part "CAP"))
    )
    (comp (ref "C70")
      (value "330p Farads 1%")
      (footprint "SM/C_0603")
      (description "capacitor ceramic 330pf, 50v, c0g, 0603; dielectric")
      (fields (field (name "MFRPARTNUM") "06035A331FAT2A"))
      (libsource (lib "FriedParts") (part "CAP"))
    )
    (comp (ref "C71")
      (value "33pF Farads 1%")
      (footprint "SM/C_0603")
      (description "ceramic multilayer capacitor; capacitor type:general")
      (fields (field (name "MFRPARTNUM") "06031A330FAT2A"))
      (libsource (lib "FriedParts") (part "CAP"))
    )
    (comp (ref "C72")
      (value "1u Farads 10%")
      (footprint "SM/C_0603")
      (description "CAP CER 1.0UF 10V 10% X5R 0603")
      (fields (field (name "MFRPARTNUM") "GRM188R61A105KA61D"))
      (libsource (lib "") (part "CAP NP_1"))
    )
    (comp (ref "C73")
      (value "47p Farads 1%")
      (footprint "SM/C_0603")
      (description "ceramic multilayer capacitor; capacitor type:general")
      (fields (field (name "MFRPARTNUM") "06031A470FAT2A"))
      (libsource (lib "FriedParts") (part "CAP"))
    )
    (comp (ref "C74")
      (value "47p Farads 1%")
      (footprint "SM/C_0603")
      (description "ceramic multilayer capacitor; capacitor type:general")
      (fields (field (name "MFRPARTNUM") "06031A470FAT2A"))
      (libsource (lib "FriedParts") (part "CAP"))
    )
    (comp (ref "C75")
      (value "47p Farads 1%")
      (footprint "SM/C_0603")
      (description "ceramic multilayer capacitor; capacitor type:general")
      (fields (field (name "MFRPARTNUM") "06031A470FAT2A"))
      (libsource (lib "FriedParts") (part "CAP"))
    )
    (comp (ref "C76")
      (value "47p Farads 1%")
      (footprint "SM/C_0603")
      (description "ceramic multilayer capacitor; capacitor type:general")
      (fields (field (name "MFRPARTNUM") "06031A470FAT2A"))
      (libsource (lib "FriedParts") (part "CAP"))
    )
    (comp (ref "C77")
      (value "47p Farads 1%")
      (footprint "SM/C_0603")
      (description "ceramic multilayer capacitor; capacitor type:general")
      (fields (field (name "MFRPARTNUM") "06031A470FAT2A"))
      (libsource (lib "FriedParts") (part "CAP"))
    )
    (comp (ref "C78")
      (value "47p Farads 1%")
      (footprint "SM/C_0603")
      (description "ceramic multilayer capacitor; capacitor type:general")
      (fields (field (name "MFRPARTNUM") "06031A470FAT2A"))
      (libsource (lib "FriedParts") (part "CAP"))
    )
    (comp (ref "C79")
      (value "47p Farads 1%")
      (footprint "SM/C_0603")
      (description "ceramic multilayer capacitor; capacitor type:general")
      (fields (field (name "MFRPARTNUM") "06031A470FAT2A"))
      (libsource (lib "FriedParts") (part "CAP"))
    )
    (comp (ref "C80")
      (value "47p Farads 1%")
      (footprint "SM/C_0603")
      (description "ceramic multilayer capacitor; capacitor type:general")
      (fields (field (name "MFRPARTNUM") "06031A470FAT2A"))
      (libsource (lib "FriedParts") (part "CAP"))
    )
    (comp (ref "C81")
      (value "1u Farads 10%")
      (footprint "SM/C_0603")
      (description "CAP CER 1.0UF 10V 10% X5R 0603")
      (fields (field (name "MFRPARTNUM") "GRM188R61A105KA61D"))
      (libsource (lib "FriedParts") (part "CAP NP"))
    )
    (comp (ref "C82")
      (value "1u Farads 10%")
      (footprint "SM/C_0603")
      (description "CAP CER 1.0UF 10V 10% X5R 0603")
      (fields (field (name "MFRPARTNUM") "GRM188R61A105KA61D"))
      (libsource (lib "FriedParts") (part "CAP NP"))
    )
    (comp (ref "C83")
      (value "1u Farads 10%")
      (footprint "SM/C_0603")
      (description "CAP CER 1.0UF 10V 10% X5R 0603")
      (fields (field (name "MFRPARTNUM") "GRM188R61A105KA61D"))
      (libsource (lib "FriedParts") (part "CAP NP"))
    )
    (comp (ref "C84")
      (value "1u Farads 10%")
      (footprint "SM/C_0603")
      (description "CAP CER 1.0UF 10V 10% X5R 0603")
      (fields (field (name "MFRPARTNUM") "GRM188R61A105KA61D"))
      (libsource (lib "FriedParts") (part "CAP NP"))
    )
    (comp (ref "C85")
      (value "33pF Farads 1%")
      (footprint "SM/C_0603")
      (description "ceramic multilayer capacitor; capacitor type:general")
      (fields (field (name "MFRPARTNUM") "06031A330FAT2A"))
      (libsource (lib "FriedParts") (part "CAP"))
    )
    (comp (ref "C86")
      (value "47p Farads 1%")
      (footprint "SM/C_0603")
      (description "ceramic multilayer capacitor; capacitor type:general")
      (fields (field (name "MFRPARTNUM") "06031A470FAT2A"))
      (libsource (lib "FriedParts") (part "CAP"))
    )
    (comp (ref "C87")
      (value "47p Farads 1%")
      (footprint "SM/C_0603")
      (description "ceramic multilayer capacitor; capacitor type:general")
      (fields (field (name "MFRPARTNUM") "06031A470FAT2A"))
      (libsource (lib "FriedParts") (part "CAP"))
    )
    (comp (ref "C88")
      (value "1u Farads 10%")
      (footprint "SM/C_0603")
      (description "CAP CER 1.0UF 10V 10% X5R 0603")
      (fields (field (name "MFRPARTNUM") "GRM188R61A105KA61D"))
      (libsource (lib "FriedParts") (part "CAP NP"))
    )
    (comp (ref "C89")
      (value "47p Farads 1%")
      (footprint "SM/C_0603")
      (description "ceramic multilayer capacitor; capacitor type:general")
      (fields (field (name "MFRPARTNUM") "06031A470FAT2A"))
      (libsource (lib "FriedParts") (part "CAP"))
    )
    (comp (ref "C90")
      (value "47p Farads 1%")
      (footprint "SM/C_0603")
      (description "ceramic multilayer capacitor; capacitor type:general")
      (fields (field (name "MFRPARTNUM") "06031A470FAT2A"))
      (libsource (lib "FriedParts") (part "CAP"))
    )
    (comp (ref "C91")
      (value "33pF Farads 1%")
      (footprint "SM/C_0603")
      (description "ceramic multilayer capacitor; capacitor type:general")
      (fields (field (name "MFRPARTNUM") "06031A330FAT2A"))
      (libsource (lib "FriedParts") (part "CAP"))
    )
    (comp (ref "C92")
      (value "33pF Farads 1%")
      (footprint "SM/C_0603")
      (description "ceramic multilayer capacitor; capacitor type:general")
      (fields (field (name "MFRPARTNUM") "06031A330FAT2A"))
      (libsource (lib "FriedParts") (part "CAP"))
    )
    (comp (ref "C93")
      (value "33pF Farads 1%")
      (footprint "SM/C_0603")
      (description "ceramic multilayer capacitor; capacitor type:general")
      (fields (field (name "MFRPARTNUM") "06031A330FAT2A"))
      (libsource (lib "FriedParts") (part "CAP"))
    )
    (comp (ref "C94")
      (value "47p Farads 1%")
      (footprint "SM/C_0603")
      (description "ceramic multilayer capacitor; capacitor type:general")
      (fields (field (name "MFRPARTNUM") "06031A470FAT2A"))
      (libsource (lib "FriedParts") (part "CAP"))
    )
    (comp (ref "C95")
      (value "47p Farads 1%")
      (footprint "SM/C_0603")
      (description "ceramic multilayer capacitor; capacitor type:general")
      (fields (field (name "MFRPARTNUM") "06031A470FAT2A"))
      (libsource (lib "FriedParts") (part "CAP"))
    )
    (comp (ref "C96")
      (value "47p Farads 1%")
      (footprint "SM/C_0603")
      (description "ceramic multilayer capacitor; capacitor type:general")
      (fields (field (name "MFRPARTNUM") "06031A470FAT2A"))
      (libsource (lib "FriedParts") (part "CAP"))
    )
    (comp (ref "C97")
      (value "47p Farads 1%")
      (footprint "SM/C_0603")
      (description "ceramic multilayer capacitor; capacitor type:general")
      (fields (field (name "MFRPARTNUM") "06031A470FAT2A"))
      (libsource (lib "FriedParts") (part "CAP"))
    )
    (comp (ref "C98")
      (value "47p Farads 1%")
      (footprint "SM/C_0603")
      (description "ceramic multilayer capacitor; capacitor type:general")
      (fields (field (name "MFRPARTNUM") "06031A470FAT2A"))
      (libsource (lib "FriedParts") (part "CAP"))
    )
    (comp (ref "C99")
      (value "47p Farads 1%")
      (footprint "SM/C_0603")
      (description "ceramic multilayer capacitor; capacitor type:general")
      (fields (field (name "MFRPARTNUM") "06031A470FAT2A"))
      (libsource (lib "FriedParts") (part "CAP"))
    )
    (comp (ref "C100")
      (value "47p Farads 1%")
      (footprint "SM/C_0603")
      (description "ceramic multilayer capacitor; capacitor type:general")
      (fields (field (name "MFRPARTNUM") "06031A470FAT2A"))
      (libsource (lib "FriedParts") (part "CAP"))
    )
    (comp (ref "C101")
      (value "47p Farads 1%")
      (footprint "SM/C_0603")
      (description "ceramic multilayer capacitor; capacitor type:general")
      (fields (field (name "MFRPARTNUM") "06031A470FAT2A"))
      (libsource (lib "FriedParts") (part "CAP"))
    )
    (comp (ref "C102")
      (value "1u Farads 10%")
      (footprint "SM/C_0603")
      (description "CAP CER 1.0UF 10V 10% X5R 0603")
      (fields (field (name "MFRPARTNUM") "GRM188R61A105KA61D"))
      (libsource (lib "FriedParts") (part "CAP NP"))
    )
    (comp (ref "C103")
      (value "1u Farads 10%")
      (footprint "SM/C_0603")
      (description "CAP CER 1.0UF 10V 10% X5R 0603")
      (fields (field (name "MFRPARTNUM") "GRM188R61A105KA61D"))
      (libsource (lib "FriedParts") (part "CAP NP"))
    )
    (comp (ref "C104")
      (value "1u Farads 10%")
      (footprint "SM/C_0603")
      (description "CAP CER 1.0UF 10V 10% X5R 0603")
      (fields (field (name "MFRPARTNUM") "GRM188R61A105KA61D"))
      (libsource (lib "FriedParts") (part "CAP NP"))
    )
    (comp (ref "C105")
      (value "1u Farads 10%")
      (footprint "SM/C_0603")
      (description "CAP CER 1.0UF 10V 10% X5R 0603")
      (fields (field (name "MFRPARTNUM") "GRM188R61A105KA61D"))
      (libsource (lib "FriedParts") (part "CAP NP"))
    )
    (comp (ref "C106")
      (value "1u Farads 10%")
      (footprint "SM/C_0603")
      (description "CAP CER 1.0UF 10V 10% X5R 0603")
      (fields (field (name "MFRPARTNUM") "GRM188R61A105KA61D"))
      (libsource (lib "") (part "CAP NP_1"))
    )
    (comp (ref "C107")
      (value "47p Farads 1%")
      (footprint "SM/C_0603")
      (description "ceramic multilayer capacitor; capacitor type:general")
      (fields (field (name "MFRPARTNUM") "06031A470FAT2A"))
      (libsource (lib "FriedParts") (part "CAP"))
    )
    (comp (ref "C108")
      (value "47p Farads 1%")
      (footprint "SM/C_0603")
      (description "ceramic multilayer capacitor; capacitor type:general")
      (fields (field (name "MFRPARTNUM") "06031A470FAT2A"))
      (libsource (lib "FriedParts") (part "CAP"))
    )
    (comp (ref "C109")
      (value "47p Farads 1%")
      (footprint "SM/C_0603")
      (description "ceramic multilayer capacitor; capacitor type:general")
      (fields (field (name "MFRPARTNUM") "06031A470FAT2A"))
      (libsource (lib "FriedParts") (part "CAP"))
    )
    (comp (ref "C110")
      (value "47p Farads 1%")
      (footprint "SM/C_0603")
      (description "ceramic multilayer capacitor; capacitor type:general")
      (fields (field (name "MFRPARTNUM") "06031A470FAT2A"))
      (libsource (lib "FriedParts") (part "CAP"))
    )
    (comp (ref "C111")
      (value "47p Farads 1%")
      (footprint "SM/C_0603")
      (description "ceramic multilayer capacitor; capacitor type:general")
      (fields (field (name "MFRPARTNUM") "06031A470FAT2A"))
      (libsource (lib "FriedParts") (part "CAP"))
    )
    (comp (ref "C112")
      (value "47p Farads 1%")
      (footprint "SM/C_0603")
      (description "ceramic multilayer capacitor; capacitor type:general")
      (fields (field (name "MFRPARTNUM") "06031A470FAT2A"))
      (libsource (lib "FriedParts") (part "CAP"))
    )
    (comp (ref "C113")
      (value "33pF Farads 1%")
      (footprint "SM/C_0603")
      (description "ceramic multilayer capacitor; capacitor type:general")
      (fields (field (name "MFRPARTNUM") "06031A330FAT2A"))
      (libsource (lib "FriedParts") (part "CAP"))
    )
    (comp (ref "C114")
      (value "33pF Farads 1%")
      (footprint "SM/C_0603")
      (description "ceramic multilayer capacitor; capacitor type:general")
      (fields (field (name "MFRPARTNUM") "06031A330FAT2A"))
      (libsource (lib "FriedParts") (part "CAP"))
    )
    (comp (ref "C115")
      (value "1u Farads 10%")
      (footprint "SM/C_0603")
      (description "CAP CER 1.0UF 10V 10% X5R 0603")
      (fields (field (name "MFRPARTNUM") "GRM188R61A105KA61D"))
      (libsource (lib "FriedParts") (part "CAP NP"))
    )
    (comp (ref "C116")
      (value "1u Farads 10%")
      (footprint "SM/C_0603")
      (description "CAP CER 1.0UF 10V 10% X5R 0603")
      (fields (field (name "MFRPARTNUM") "GRM188R61A105KA61D"))
      (libsource (lib "FriedParts") (part "CAP NP"))
    )
    (comp (ref "C117")
      (value "1u Farads 10%")
      (footprint "SM/C_0603")
      (description "CAP CER 1.0UF 10V 10% X5R 0603")
      (fields (field (name "MFRPARTNUM") "GRM188R61A105KA61D"))
      (libsource (lib "FriedParts") (part "CAP NP"))
    )
    (comp (ref "C118")
      (value "1u Farads 10%")
      (footprint "SM/C_0603")
      (description "CAP CER 1.0UF 10V 10% X5R 0603")
      (fields (field (name "MFRPARTNUM") "GRM188R61A105KA61D"))
      (libsource (lib "FriedParts") (part "CAP NP"))
    )
    (comp (ref "CN1")
      (value "Mini B Socket R/A USB Type Per Spec")
      (footprint "MOLEX/54819-0579")
      (description "CONN RECEPT USB MINI-B R/A 5POS SMD")
      (fields (field (name "MFRPARTNUM") "54819-0572"))
      (libsource (lib "FriedParts") (part "USB_MINI_B/5"))
    )
    (comp (ref "CON1")
      (value "5227161-1")
      (footprint "BNC-RightAngle-PCB-50Ohm-Termination")
      (description "jack bnc, right angle, pcb; connector type:bnc, coaxial;")
      (libsource (lib "FriedParts") (part "BNC"))
    )
    (comp (ref "CON2")
      (value "640456-2")
      (footprint "M02-LockingHeader-100mil-pitch")
      (description "header, vertical, 0.1``, 2way; connector type:wire-to-board;")
      (libsource (lib "FriedParts") (part "M02"))
    )
    (comp (ref "CON3")
      (value "640456-2")
      (footprint "M02-LockingHeader-100mil-pitch")
      (description "header, vertical, 0.1``, 2way; connector type:wire-to-board;")
      (libsource (lib "FriedParts") (part "M02"))
    )
    (comp (ref "CON4")
      (value "640456-2")
      (footprint "M02-LockingHeader-100mil-pitch")
      (description "header, vertical, 0.1``, 2way; connector type:wire-to-board;")
      (libsource (lib "FriedParts") (part "M02"))
    )
    (comp (ref "CON5")
      (value "640456-2")
      (footprint "M02-LockingHeader-100mil-pitch")
      (description "header, vertical, 0.1``, 2way; connector type:wire-to-board;")
      (libsource (lib "FriedParts") (part "M02"))
    )
    (comp (ref "CON6")
      (value "5227161-1")
      (footprint "BNC-RightAngle-PCB-50Ohm-Termination")
      (description "jack bnc, right angle, pcb; connector type:bnc, coaxial;")
      (libsource (lib "FriedParts") (part "BNC"))
    )
    (comp (ref "CON7")
      (value "5227161-1")
      (footprint "BNC-RightAngle-PCB-50Ohm-Termination")
      (description "jack bnc, right angle, pcb; connector type:bnc, coaxial;")
      (libsource (lib "FriedParts") (part "BNC"))
    )
    (comp (ref "CON8")
      (value "5227161-1")
      (footprint "BNC-RightAngle-PCB-50Ohm-Termination")
      (description "jack bnc, right angle, pcb; connector type:bnc, coaxial;")
      (libsource (lib "FriedParts") (part "BNC"))
    )
    (comp (ref "CON9")
      (value "5227161-1")
      (footprint "BNC-RightAngle-PCB-50Ohm-Termination")
      (description "jack bnc, right angle, pcb; connector type:bnc, coaxial;")
      (libsource (lib "FriedParts") (part "BNC"))
    )
    (comp (ref "CON_L1")
      (value "1299")
      (footprint "LOW-PROFILE-SCREWTERMINAL")
      (description "brass tin plate low profile 10 - 32 thread with anti")
      (libsource (lib "FriedParts") (part "ScrewTerminal-PCB-ThruHole"))
    )
    (comp (ref "CON_N1")
      (value "1299")
      (footprint "LOW-PROFILE-SCREWTERMINAL")
      (description "brass tin plate low profile 10 - 32 thread with anti")
      (libsource (lib "FriedParts") (part "ScrewTerminal-PCB-ThruHole"))
    )
    (comp (ref "D1")
      (value "red")
      (footprint "LITEON/LED/0603")
      (description "LED SUPER RED CLEAR 0603 SMD")
      (fields (field (name "MFRPARTNUM") "LTST-C190KRKT") (field (name "PUBLISHER") "Altium Limited"))
      (libsource (lib "FriedParts") (part "LITEON/LED RED"))
    )
    (comp (ref "D2")
      (value "red")
      (footprint "LITEON/LED/0603")
      (description "LED SUPER RED CLEAR 0603 SMD")
      (fields (field (name "MFRPARTNUM") "LTST-C190KRKT") (field (name "PUBLISHER") "Altium Limited"))
      (libsource (lib "FriedParts") (part "LITEON/LED RED"))
    )
    (comp (ref "D3")
      (value "red")
      (footprint "LITEON/LED/0603")
      (description "LED SUPER RED CLEAR 0603 SMD")
      (fields (field (name "MFRPARTNUM") "LTST-C190KRKT") (field (name "PUBLISHER") "Altium Limited"))
      (libsource (lib "FriedParts") (part "LITEON/LED RED"))
    )
    (comp (ref "D4")
      (value "red")
      (footprint "LITEON/LED/0603")
      (description "LED SUPER RED CLEAR 0603 SMD")
      (fields (field (name "MFRPARTNUM") "LTST-C190KRKT") (field (name "PUBLISHER") "Altium Limited"))
      (libsource (lib "FriedParts") (part "LITEON/LED RED"))
    )
    (comp (ref "D_STAT1")
      (value "red")
      (footprint "LITEON/LED/0603")
      (description "LED SUPER RED CLEAR 0603 SMD")
      (fields (field (name "MFRPARTNUM") "LTST-C190KRKT") (field (name "PUBLISHER") "Altium Limited"))
      (libsource (lib "FriedParts") (part "LITEON/LED RED"))
    )
    (comp (ref "F1")
      (value "110V @ 2 AMP Fast Blow")
      (footprint "WICKMANN/WK0011-ND")
      (description "FUSEHOLDER OPEN 5X20MM PC MNT")
      (fields (field (name "MFRPARTNUM") "6490000100"))
      (libsource (lib "FriedParts") (part "FUSEHOLDER"))
    )
    (comp (ref "F2")
      (value "110V @ 100 milliamp Fast Blow")
      (footprint "WICKMANN/WK0011-ND")
      (description "FUSEHOLDER OPEN 5X20MM PC MNT")
      (fields (field (name "MFRPARTNUM") "6490000100"))
      (libsource (lib "FriedParts") (part "FUSEHOLDER"))
    )
    (comp (ref "J1")
      (value "Atmel ISP 2x3")
      (footprint "FCI/75867/6")
      (description "CONN HEADER 6POS DUAL R/A PCB")
      (fields (field (name "MFRPARTNUM") "75867-131LF"))
      (libsource (lib "FriedParts") (part "ATMEL/ISP6"))
    )
    (comp (ref "R1")
      (value "0 Ohms 0")
      (footprint "SM/R_0603")
      (description "res thick film 0603 0 ohm 1/10w molded smd punched carrier")
      (fields (field (name "MFRPARTNUM") "ERJ-3GEY0R00V") (field (name "PUBLISHER") "Altium Limited"))
      (libsource (lib "FriedParts") (part "Res1"))
    )
    (comp (ref "R2")
      (value "50 Ohm 1%")
      (footprint "SM/R_0603")
      (description "; resistance:50ohm; resistance tolerance:± 0.1%; power")
      (fields (field (name "MFRPARTNUM") "FC0603E50R0BTBST1") (field (name "PUBLISHER") "Altium Limited"))
      (libsource (lib "FriedParts") (part "Res1"))
    )
    (comp (ref "R3")
      (value "330 Ohms 1%")
      (footprint "SM/C_0603")
      (description "RES 330 OHM 1/10W 1% 0603 SMD")
      (fields (field (name "MFRPARTNUM") "ERJ-3EKF3300V"))
      (libsource (lib "FriedParts") (part "R"))
    )
    (comp (ref "R4")
      (value "1k Ohms 1%")
      (footprint "SM/C_0603")
      (description "RES 1.00K OHM 1/10W 1% 0603 SMD")
      (fields (field (name "MFRPARTNUM") "ERJ-3EKF1001V"))
      (libsource (lib "FriedParts") (part "R"))
    )
    (comp (ref "R5")
      (value "10k ohm 1%")
      (footprint "SM/C_0603")
      (description "resistor, 0603, 0.1w, 1%, 10k; resistance:10kohm; resistance")
      (fields (field (name "MFRPARTNUM") "ERJ-3EKF1002V") (field (name "PUBLISHER") "Altium Limited"))
      (libsource (lib "FriedParts") (part "Res1"))
    )
    (comp (ref "R6")
      (value "3k Ohms 1%")
      (footprint "SM/C_0603")
      (description "resistor, thick film, 30kohm, 100mw, 1%; resistance:30kohm;")
      (fields (field (name "MFRPARTNUM") "RC0603FR-0730KL") (field (name "PUBLISHER") "Altium Limited"))
      (libsource (lib "FriedParts") (part "Res1"))
    )
    (comp (ref "R7")
      (value "330 Ohms 1%")
      (footprint "SM/C_0603")
      (description "RES 330 OHM 1/10W 1% 0603 SMD")
      (fields (field (name "MFRPARTNUM") "ERJ-3EKF3300V"))
      (libsource (lib "FriedParts") (part "R"))
    )
    (comp (ref "R8")
      (value "1k Ohms 1%")
      (footprint "SM/C_0603")
      (description "RES 1.00K OHM 1/10W 1% 0603 SMD")
      (fields (field (name "MFRPARTNUM") "ERJ-3EKF1001V"))
      (libsource (lib "FriedParts") (part "R"))
    )
    (comp (ref "R9")
      (value "1k Ohms 1%")
      (footprint "SM/C_0603")
      (description "RES 1.00K OHM 1/10W 1% 0603 SMD")
      (fields (field (name "MFRPARTNUM") "ERJ-3EKF1001V"))
      (libsource (lib "FriedParts") (part "R"))
    )
    (comp (ref "R10")
      (value "1k Ohms 1%")
      (footprint "SM/C_0603")
      (description "RES 1.00K OHM 1/10W 1% 0603 SMD")
      (fields (field (name "MFRPARTNUM") "ERJ-3EKF1001V"))
      (libsource (lib "FriedParts") (part "R"))
    )
    (comp (ref "R11")
      (value "1k Ohms 1%")
      (footprint "SM/C_0603")
      (description "RES 1.00K OHM 1/10W 1% 0603 SMD")
      (fields (field (name "MFRPARTNUM") "ERJ-3EKF1001V"))
      (libsource (lib "FriedParts") (part "R"))
    )
    (comp (ref "R12")
      (value "1k Ohms 1%")
      (footprint "SM/C_0603")
      (description "RES 1.00K OHM 1/10W 1% 0603 SMD")
      (fields (field (name "MFRPARTNUM") "ERJ-3EKF1001V"))
      (libsource (lib "FriedParts") (part "R"))
    )
    (comp (ref "R13")
      (value "1k Ohms 1%")
      (footprint "SM/C_0603")
      (description "RES 1.00K OHM 1/10W 1% 0603 SMD")
      (fields (field (name "MFRPARTNUM") "ERJ-3EKF1001V"))
      (libsource (lib "FriedParts") (part "R"))
    )
    (comp (ref "R14")
      (value "1k Ohms 1%")
      (footprint "SM/C_0603")
      (description "RES 1.00K OHM 1/10W 1% 0603 SMD")
      (fields (field (name "MFRPARTNUM") "ERJ-3EKF1001V"))
      (libsource (lib "FriedParts") (part "R"))
    )
    (comp (ref "R15")
      (value "330 Ohms 1%")
      (footprint "SM/C_0603")
      (description "RES 330 OHM 1/10W 1% 0603 SMD")
      (fields (field (name "MFRPARTNUM") "ERJ-3EKF3300V"))
      (libsource (lib "FriedParts") (part "R"))
    )
    (comp (ref "R16")
      (value "2.7M Ohm 1%")
      (footprint "SM/R_0603")
      (description "res, thick film, 2.7mohm, 100mw, 1%; resistance:2.7mohm;")
      (fields (field (name "MFRPARTNUM") "CRCW06032M70FKEA") (field (name "PUBLISHER") "Altium Limited"))
      (libsource (lib "FriedParts") (part "Res1"))
    )
    (comp (ref "R17")
      (value "2.7M Ohm 1%")
      (footprint "SM/R_0603")
      (description "res, thick film, 2.7mohm, 100mw, 1%; resistance:2.7mohm;")
      (fields (field (name "MFRPARTNUM") "CRCW06032M70FKEA") (field (name "PUBLISHER") "Altium Limited"))
      (libsource (lib "FriedParts") (part "Res1"))
    )
    (comp (ref "R18")
      (value "1k Ohms 1%")
      (footprint "SM/C_0603")
      (description "RES 1.00K OHM 1/10W 1% 0603 SMD")
      (fields (field (name "MFRPARTNUM") "ERJ-3EKF1001V"))
      (libsource (lib "FriedParts") (part "R"))
    )
    (comp (ref "R19")
      (value "2.7M Ohm 1%")
      (footprint "SM/R_0603")
      (description "res, thick film, 2.7mohm, 100mw, 1%; resistance:2.7mohm;")
      (fields (field (name "MFRPARTNUM") "CRCW06032M70FKEA") (field (name "PUBLISHER") "Altium Limited"))
      (libsource (lib "FriedParts") (part "Res1"))
    )
    (comp (ref "R20")
      (value "2.7M Ohm 1%")
      (footprint "SM/R_0603")
      (description "res, thick film, 2.7mohm, 100mw, 1%; resistance:2.7mohm;")
      (fields (field (name "MFRPARTNUM") "CRCW06032M70FKEA") (field (name "PUBLISHER") "Altium Limited"))
      (libsource (lib "FriedParts") (part "Res1"))
    )
    (comp (ref "R21")
      (value "1k Ohms 1%")
      (footprint "SM/C_0603")
      (description "RES 1.00K OHM 1/10W 1% 0603 SMD")
      (fields (field (name "MFRPARTNUM") "ERJ-3EKF1001V"))
      (libsource (lib "FriedParts") (part "R"))
    )
    (comp (ref "R22")
      (value "2.7M Ohm 1%")
      (footprint "SM/R_0603")
      (description "res, thick film, 2.7mohm, 100mw, 1%; resistance:2.7mohm;")
      (fields (field (name "MFRPARTNUM") "CRCW06032M70FKEA") (field (name "PUBLISHER") "Altium Limited"))
      (libsource (lib "FriedParts") (part "Res1"))
    )
    (comp (ref "R23")
      (value "2.7M Ohm 1%")
      (footprint "SM/R_0603")
      (description "res, thick film, 2.7mohm, 100mw, 1%; resistance:2.7mohm;")
      (fields (field (name "MFRPARTNUM") "CRCW06032M70FKEA") (field (name "PUBLISHER") "Altium Limited"))
      (libsource (lib "FriedParts") (part "Res1"))
    )
    (comp (ref "R24")
      (value "330 Ohms 1%")
      (footprint "SM/C_0603")
      (description "RES 330 OHM 1/10W 1% 0603 SMD")
      (fields (field (name "MFRPARTNUM") "ERJ-3EKF3300V"))
      (libsource (lib "FriedParts") (part "R"))
    )
    (comp (ref "R25")
      (value "2.7M Ohm 1%")
      (footprint "SM/R_0603")
      (description "res, thick film, 2.7mohm, 100mw, 1%; resistance:2.7mohm;")
      (fields (field (name "MFRPARTNUM") "CRCW06032M70FKEA") (field (name "PUBLISHER") "Altium Limited"))
      (libsource (lib "FriedParts") (part "Res1"))
    )
    (comp (ref "R26")
      (value "2.7M Ohm 1%")
      (footprint "SM/R_0603")
      (description "res, thick film, 2.7mohm, 100mw, 1%; resistance:2.7mohm;")
      (fields (field (name "MFRPARTNUM") "CRCW06032M70FKEA") (field (name "PUBLISHER") "Altium Limited"))
      (libsource (lib "FriedParts") (part "Res1"))
    )
    (comp (ref "R27")
      (value "30k Ohms 1%")
      (footprint "Resistor-3.2mm x 1.70mm")
      (description "Resistor")
      (fields (field (name "MFRPARTNUM") "ERO-S2PHF3002-2") (field (name "PUBLISHER") "Altium Limited"))
      (libsource (lib "FriedParts") (part "Res1"))
    )
    (comp (ref "R28")
      (value "1k Ohms 1%")
      (footprint "SM/C_0603")
      (description "RES 1.00K OHM 1/10W 1% 0603 SMD")
      (fields (field (name "MFRPARTNUM") "ERJ-3EKF1001V"))
      (libsource (lib "FriedParts") (part "R"))
    )
    (comp (ref "R29")
      (value "30k Ohms 1%")
      (footprint "SM/R_2512")
      (description "single components passive components resistors")
      (fields (field (name "MFRPARTNUM") "ERJ-1TNF3002U") (field (name "PUBLISHER") "Altium Limited"))
      (libsource (lib "FriedParts") (part "Res1"))
    )
    (comp (ref "R30")
      (value "30k Ohms 1%")
      (footprint "SM/R_2512")
      (description "single components passive components resistors")
      (fields (field (name "MFRPARTNUM") "ERJ-1TNF3002U") (field (name "PUBLISHER") "Altium Limited"))
      (libsource (lib "FriedParts") (part "Res1"))
    )
    (comp (ref "R31")
      (value "150 ohms 1%")
      (footprint "SM/R_2512")
      (description "single components passive components resistors")
      (fields (field (name "MFRPARTNUM") "ERJ-1TNF15R0U") (field (name "PUBLISHER") "Altium Limited"))
      (libsource (lib "FriedParts") (part "Res1"))
    )
    (comp (ref "R32")
      (value "30k Ohms 1%")
      (footprint "Resistor-3.2mm x 1.70mm")
      (description "Resistor")
      (fields (field (name "MFRPARTNUM") "ERO-S2PHF3002-2") (field (name "PUBLISHER") "Altium Limited"))
      (libsource (lib "FriedParts") (part "Res1"))
    )
    (comp (ref "R33")
      (value "30k Ohms 1%")
      (footprint "Resistor-3.2mm x 1.70mm")
      (description "Resistor")
      (fields (field (name "MFRPARTNUM") "ERO-S2PHF3002-2") (field (name "PUBLISHER") "Altium Limited"))
      (libsource (lib "FriedParts") (part "Res1"))
    )
    (comp (ref "R34")
      (value "10k ohm 1%")
      (footprint "SM/C_0603")
      (description "resistor, 0603, 0.1w, 1%, 10k; resistance:10kohm; resistance")
      (fields (field (name "MFRPARTNUM") "ERJ-3EKF1002V") (field (name "PUBLISHER") "Altium Limited"))
      (libsource (lib "FriedParts") (part "Res1"))
    )
    (comp (ref "R35")
      (value "3k Ohms 1%")
      (footprint "SM/C_0603")
      (description "resistor, thick film, 30kohm, 100mw, 1%; resistance:30kohm;")
      (fields (field (name "MFRPARTNUM") "RC0603FR-0730KL") (field (name "PUBLISHER") "Altium Limited"))
      (libsource (lib "FriedParts") (part "Res1"))
    )
    (comp (ref "R36")
      (value "1k Ohms 1%")
      (footprint "SM/C_0603")
      (description "RES 1.00K OHM 1/10W 1% 0603 SMD")
      (fields (field (name "MFRPARTNUM") "ERJ-3EKF1001V"))
      (libsource (lib "FriedParts") (part "R"))
    )
    (comp (ref "R37")
      (value "0 Ohms 0")
      (footprint "SM/R_0603")
      (description "res thick film 0603 0 ohm 1/10w molded smd punched carrier")
      (fields (field (name "MFRPARTNUM") "ERJ-3GEY0R00V") (field (name "PUBLISHER") "Altium Limited"))
      (libsource (lib "FriedParts") (part "Res1"))
    )
    (comp (ref "R38")
      (value "50 Ohm 1%")
      (footprint "SM/R_0603")
      (description "; resistance:50ohm; resistance tolerance:± 0.1%; power")
      (fields (field (name "MFRPARTNUM") "FC0603E50R0BTBST1") (field (name "PUBLISHER") "Altium Limited"))
      (libsource (lib "FriedParts") (part "Res1"))
    )
    (comp (ref "R39")
      (value "50 Ohm 1%")
      (footprint "SM/R_0603")
      (description "; resistance:50ohm; resistance tolerance:± 0.1%; power")
      (fields (field (name "MFRPARTNUM") "FC0603E50R0BTBST1") (field (name "PUBLISHER") "Altium Limited"))
      (libsource (lib "FriedParts") (part "Res1"))
    )
    (comp (ref "R40")
      (value "1k Ohms 1%")
      (footprint "SM/C_0603")
      (description "RES 1.00K OHM 1/10W 1% 0603 SMD")
      (fields (field (name "MFRPARTNUM") "ERJ-3EKF1001V"))
      (libsource (lib "FriedParts") (part "R"))
    )
    (comp (ref "R41")
      (value "2.7M Ohm 1%")
      (footprint "SM/R_0603")
      (description "res, thick film, 2.7mohm, 100mw, 1%; resistance:2.7mohm;")
      (fields (field (name "MFRPARTNUM") "CRCW06032M70FKEA") (field (name "PUBLISHER") "Altium Limited"))
      (libsource (lib "FriedParts") (part "Res1"))
    )
    (comp (ref "R42")
      (value "2.7M Ohm 1%")
      (footprint "SM/R_0603")
      (description "res, thick film, 2.7mohm, 100mw, 1%; resistance:2.7mohm;")
      (fields (field (name "MFRPARTNUM") "CRCW06032M70FKEA") (field (name "PUBLISHER") "Altium Limited"))
      (libsource (lib "FriedParts") (part "Res1"))
    )
    (comp (ref "R43")
      (value "22 ohms 1%")
      (footprint "SM/C_0603")
      (description "rating:75v; temperature coefficient")
      (fields (field (name "MFRPARTNUM") "ERJ3EKF22R0V") (field (name "PUBLISHER") "Altium Limited"))
      (libsource (lib "FriedParts") (part "Res1"))
    )
    (comp (ref "R44")
      (value "10k ohm 1%")
      (footprint "SM/C_0603")
      (description "resistor, 0603, 0.1w, 1%, 10k; resistance:10kohm; resistance")
      (fields (field (name "MFRPARTNUM") "ERJ-3EKF1002V") (field (name "PUBLISHER") "Altium Limited"))
      (libsource (lib "FriedParts") (part "Res1"))
    )
    (comp (ref "R45")
      (value "1k Ohms 1%")
      (footprint "SM/C_0603")
      (description "RES 1.00K OHM 1/10W 1% 0603 SMD")
      (fields (field (name "MFRPARTNUM") "ERJ-3EKF1001V"))
      (libsource (lib "FriedParts") (part "R"))
    )
    (comp (ref "R46")
      (value "1k Ohms 1%")
      (footprint "SM/C_0603")
      (description "RES 1.00K OHM 1/10W 1% 0603 SMD")
      (fields (field (name "MFRPARTNUM") "ERJ-3EKF1001V"))
      (libsource (lib "FriedParts") (part "R"))
    )
    (comp (ref "R47")
      (value "22 ohms 1%")
      (footprint "SM/C_0603")
      (description "rating:75v; temperature coefficient")
      (fields (field (name "MFRPARTNUM") "ERJ3EKF22R0V") (field (name "PUBLISHER") "Altium Limited"))
      (libsource (lib "FriedParts") (part "Res1"))
    )
    (comp (ref "R48")
      (value "1k Ohms 1%")
      (footprint "SM/C_0603")
      (description "RES 1.00K OHM 1/10W 1% 0603 SMD")
      (fields (field (name "MFRPARTNUM") "ERJ-3EKF1001V"))
      (libsource (lib "FriedParts") (part "R"))
    )
    (comp (ref "R49")
      (value "2.7M Ohm 1%")
      (footprint "SM/R_0603")
      (description "res, thick film, 2.7mohm, 100mw, 1%; resistance:2.7mohm;")
      (fields (field (name "MFRPARTNUM") "CRCW06032M70FKEA") (field (name "PUBLISHER") "Altium Limited"))
      (libsource (lib "FriedParts") (part "Res1"))
    )
    (comp (ref "R50")
      (value "2.7M Ohm 1%")
      (footprint "SM/R_0603")
      (description "res, thick film, 2.7mohm, 100mw, 1%; resistance:2.7mohm;")
      (fields (field (name "MFRPARTNUM") "CRCW06032M70FKEA") (field (name "PUBLISHER") "Altium Limited"))
      (libsource (lib "FriedParts") (part "Res1"))
    )
    (comp (ref "R51")
      (value "1k Ohms 1%")
      (footprint "SM/C_0603")
      (description "RES 1.00K OHM 1/10W 1% 0603 SMD")
      (fields (field (name "MFRPARTNUM") "ERJ-3EKF1001V"))
      (libsource (lib "FriedParts") (part "R"))
    )
    (comp (ref "R52")
      (value "1k Ohms 1%")
      (footprint "SM/C_0603")
      (description "RES 1.00K OHM 1/10W 1% 0603 SMD")
      (fields (field (name "MFRPARTNUM") "ERJ-3EKF1001V"))
      (libsource (lib "FriedParts") (part "R"))
    )
    (comp (ref "R53")
      (value "10k ohm 1%")
      (footprint "SM/C_0603")
      (description "resistor, 0603, 0.1w, 1%, 10k; resistance:10kohm; resistance")
      (fields (field (name "MFRPARTNUM") "ERJ-3EKF1002V") (field (name "PUBLISHER") "Altium Limited"))
      (libsource (lib "FriedParts") (part "Res1"))
    )
    (comp (ref "R54")
      (value "2.7M Ohm 1%")
      (footprint "SM/R_0603")
      (description "res, thick film, 2.7mohm, 100mw, 1%; resistance:2.7mohm;")
      (fields (field (name "MFRPARTNUM") "CRCW06032M70FKEA") (field (name "PUBLISHER") "Altium Limited"))
      (libsource (lib "FriedParts") (part "Res1"))
    )
    (comp (ref "R55")
      (value "2.7M Ohm 1%")
      (footprint "SM/R_0603")
      (description "res, thick film, 2.7mohm, 100mw, 1%; resistance:2.7mohm;")
      (fields (field (name "MFRPARTNUM") "CRCW06032M70FKEA") (field (name "PUBLISHER") "Altium Limited"))
      (libsource (lib "FriedParts") (part "Res1"))
    )
    (comp (ref "R56")
      (value "330 Ohms 1%")
      (footprint "SM/C_0603")
      (description "RES 330 OHM 1/10W 1% 0603 SMD")
      (fields (field (name "MFRPARTNUM") "ERJ-3EKF3300V"))
      (libsource (lib "FriedParts") (part "R"))
    )
    (comp (ref "R57")
      (value "1k Ohms 1%")
      (footprint "SM/C_0603")
      (description "RES 1.00K OHM 1/10W 1% 0603 SMD")
      (fields (field (name "MFRPARTNUM") "ERJ-3EKF1001V"))
      (libsource (lib "FriedParts") (part "R"))
    )
    (comp (ref "R58")
      (value "2.7M Ohm 1%")
      (footprint "SM/R_0603")
      (description "res, thick film, 2.7mohm, 100mw, 1%; resistance:2.7mohm;")
      (fields (field (name "MFRPARTNUM") "CRCW06032M70FKEA") (field (name "PUBLISHER") "Altium Limited"))
      (libsource (lib "FriedParts") (part "Res1"))
    )
    (comp (ref "R59")
      (value "2.7M Ohm 1%")
      (footprint "SM/R_0603")
      (description "res, thick film, 2.7mohm, 100mw, 1%; resistance:2.7mohm;")
      (fields (field (name "MFRPARTNUM") "CRCW06032M70FKEA") (field (name "PUBLISHER") "Altium Limited"))
      (libsource (lib "FriedParts") (part "Res1"))
    )
    (comp (ref "R60")
      (value "1k Ohms 1%")
      (footprint "SM/C_0603")
      (description "RES 1.00K OHM 1/10W 1% 0603 SMD")
      (fields (field (name "MFRPARTNUM") "ERJ-3EKF1001V"))
      (libsource (lib "FriedParts") (part "R"))
    )
    (comp (ref "R61")
      (value "10k ohm 1%")
      (description "Resistor")
      (fields (field (name "PUBLISHER") "Altium Limited"))
      (libsource (lib "FriedParts") (part "Res1"))
    )
    (comp (ref "R62")
      (value "10k ohm 1%")
      (description "Resistor")
      (fields (field (name "PUBLISHER") "Altium Limited"))
      (libsource (lib "FriedParts") (part "Res1"))
    )
    (comp (ref "R63")
      (value "10k ohm 1%")
      (description "Resistor")
      (fields (field (name "PUBLISHER") "Altium Limited"))
      (libsource (lib "FriedParts") (part "Res1"))
    )
    (comp (ref "R64")
      (value "10k ohm 1%")
      (description "Resistor")
      (fields (field (name "PUBLISHER") "Altium Limited"))
      (libsource (lib "FriedParts") (part "Res1"))
    )
    (comp (ref "R65")
      (value "10k ohm 1%")
      (description "Resistor")
      (fields (field (name "PUBLISHER") "Altium Limited"))
      (libsource (lib "FriedParts") (part "Res1"))
    )
    (comp (ref "R66")
      (value "10k ohm 1%")
      (description "Resistor")
      (fields (field (name "PUBLISHER") "Altium Limited"))
      (libsource (lib "FriedParts") (part "Res1"))
    )
    (comp (ref "R67")
      (value "10k ohm 1%")
      (description "Resistor")
      (fields (field (name "PUBLISHER") "Altium Limited"))
      (libsource (lib "FriedParts") (part "Res1"))
    )
    (comp (ref "R68")
      (value "10k ohm 1%")
      (description "Resistor")
      (fields (field (name "PUBLISHER") "Altium Limited"))
      (libsource (lib "FriedParts") (part "Res1"))
    )
    (comp (ref "R69")
      (value "10k ohm 1%")
      (description "Resistor")
      (fields (field (name "PUBLISHER") "Altium Limited"))
      (libsource (lib "FriedParts") (part "Res1"))
    )
    (comp (ref "R70")
      (value "174k Ohms 1%")
      (footprint "SM/R_0603")
      (description "rc series 0603 0.1 w 174 kohms 1% ±100 ppm/°c smt thick film")
      (fields (field (name "MFRPARTNUM") "RC0603FR-07174KL") (field (name "PUBLISHER") "Altium Limited"))
      (libsource (lib "FriedParts") (part "Res1"))
    )
    (comp (ref "R71")
      (value "174k Ohms 1%")
      (footprint "SM/R_0603")
      (description "rc series 0603 0.1 w 174 kohms 1% ±100 ppm/°c smt thick film")
      (fields (field (name "MFRPARTNUM") "RC0603FR-07174KL") (field (name "PUBLISHER") "Altium Limited"))
      (libsource (lib "FriedParts") (part "Res1"))
    )
    (comp (ref "R72")
      (value "115k Ohm 1%")
      (footprint "SM/R_0603")
      (description "res thick film 0603 1.15k ohm 1% 1/10w ?100ppm/?c molded smd")
      (fields (field (name "MFRPARTNUM") "ERJ-3EKF1151V") (field (name "PUBLISHER") "Altium Limited"))
      (libsource (lib "FriedParts") (part "Res1"))
    )
    (comp (ref "R73")
      (value "115k Ohm 1%")
      (footprint "SM/R_0603")
      (description "res thick film 0603 1.15k ohm 1% 1/10w ?100ppm/?c molded smd")
      (fields (field (name "MFRPARTNUM") "ERJ-3EKF1151V") (field (name "PUBLISHER") "Altium Limited"))
      (libsource (lib "FriedParts") (part "Res1"))
    )
    (comp (ref "R74")
      (value "115k Ohm 1%")
      (footprint "SM/R_0603")
      (description "res thick film 0603 1.15k ohm 1% 1/10w ?100ppm/?c molded smd")
      (fields (field (name "MFRPARTNUM") "ERJ-3EKF1151V") (field (name "PUBLISHER") "Altium Limited"))
      (libsource (lib "FriedParts") (part "Res1"))
    )
    (comp (ref "R75")
      (value "115k Ohm 1%")
      (footprint "SM/R_0603")
      (description "res thick film 0603 1.15k ohm 1% 1/10w ?100ppm/?c molded smd")
      (fields (field (name "MFRPARTNUM") "ERJ-3EKF1151V") (field (name "PUBLISHER") "Altium Limited"))
      (libsource (lib "FriedParts") (part "Res1"))
    )
    (comp (ref "R76")
      (value "249k Ohms 1%")
      (footprint "SM/C_0603")
      (description "res thick film 0603 249k ohm 1% 1/10w ?100ppm/?c molded smd")
      (fields (field (name "MFRPARTNUM") "ERJ-3EKF2493V") (field (name "PUBLISHER") "Altium Limited"))
      (libsource (lib "FriedParts") (part "Res1"))
    )
    (comp (ref "R77")
      (value "249k Ohms 1%")
      (footprint "SM/C_0603")
      (description "res thick film 0603 249k ohm 1% 1/10w ?100ppm/?c molded smd")
      (fields (field (name "MFRPARTNUM") "ERJ-3EKF2493V") (field (name "PUBLISHER") "Altium Limited"))
      (libsource (lib "FriedParts") (part "Res1"))
    )
    (comp (ref "R78")
      (value "160k Ohms 1%")
      (footprint "SM/R_0603")
      (description "res 160k ohm 1/10w 1% 0603 smd")
      (fields (field (name "MFRPARTNUM") "ERJ-3EKF1603V") (field (name "PUBLISHER") "Altium Limited"))
      (libsource (lib "FriedParts") (part "Res1"))
    )
    (comp (ref "R79")
      (value "160k Ohms 1%")
      (footprint "SM/R_0603")
      (description "res 160k ohm 1/10w 1% 0603 smd")
      (fields (field (name "MFRPARTNUM") "ERJ-3EKF1603V") (field (name "PUBLISHER") "Altium Limited"))
      (libsource (lib "FriedParts") (part "Res1"))
    )
    (comp (ref "R80")
      (value "50 Ohm 1%")
      (footprint "SM/R_0603")
      (description "; resistance:50ohm; resistance tolerance:± 0.1%; power")
      (fields (field (name "MFRPARTNUM") "FC0603E50R0BTBST1") (field (name "PUBLISHER") "Altium Limited"))
      (libsource (lib "FriedParts") (part "Res1"))
    )
    (comp (ref "R81")
      (value "160k Ohms 1%")
      (footprint "SM/R_0603")
      (description "res 160k ohm 1/10w 1% 0603 smd")
      (fields (field (name "MFRPARTNUM") "ERJ-3EKF1603V") (field (name "PUBLISHER") "Altium Limited"))
      (libsource (lib "FriedParts") (part "Res1"))
    )
    (comp (ref "R82")
      (value "160k Ohms 1%")
      (footprint "SM/R_0603")
      (description "res 160k ohm 1/10w 1% 0603 smd")
      (fields (field (name "MFRPARTNUM") "ERJ-3EKF1603V") (field (name "PUBLISHER") "Altium Limited"))
      (libsource (lib "FriedParts") (part "Res1"))
    )
    (comp (ref "R83")
      (value "30k Ohms 1%")
      (footprint "SM/R_0603")
      (description "res thick film 0603 300k ohm 1% 1/10w ±100ppm/°c molded smd")
      (fields (field (name "MFRPARTNUM") "ERJ-3EKF3003V") (field (name "PUBLISHER") "Altium Limited"))
      (libsource (lib "FriedParts") (part "Res1"))
    )
    (comp (ref "R84")
      (value "30k Ohms 1%")
      (footprint "SM/R_0603")
      (description "res thick film 0603 300k ohm 1% 1/10w ±100ppm/°c molded smd")
      (fields (field (name "MFRPARTNUM") "ERJ-3EKF3003V") (field (name "PUBLISHER") "Altium Limited"))
      (libsource (lib "FriedParts") (part "Res1"))
    )
    (comp (ref "R85")
      (value "30k Ohms 1%")
      (footprint "SM/R_0603")
      (description "res thick film 0603 300k ohm 1% 1/10w ±100ppm/°c molded smd")
      (fields (field (name "MFRPARTNUM") "ERJ-3EKF3003V") (field (name "PUBLISHER") "Altium Limited"))
      (libsource (lib "FriedParts") (part "Res1"))
    )
    (comp (ref "R86")
      (value "30k Ohms 1%")
      (footprint "SM/R_0603")
      (description "res thick film 0603 300k ohm 1% 1/10w ±100ppm/°c molded smd")
      (fields (field (name "MFRPARTNUM") "ERJ-3EKF3003V") (field (name "PUBLISHER") "Altium Limited"))
      (libsource (lib "FriedParts") (part "Res1"))
    )
    (comp (ref "R87")
      (value "15k Ohms 1%")
      (footprint "SM/R_0603")
      (description "resistor, thick film, 15kohm, 100mw, 1%; resistance:15kohm;")
      (fields (field (name "MFRPARTNUM") "RC0603FR-0715KL") (field (name "PUBLISHER") "Altium Limited"))
      (libsource (lib "FriedParts") (part "Res1"))
    )
    (comp (ref "R88")
      (value "15k Ohms 1%")
      (footprint "SM/R_0603")
      (description "resistor, thick film, 15kohm, 100mw, 1%; resistance:15kohm;")
      (fields (field (name "MFRPARTNUM") "RC0603FR-0715KL") (field (name "PUBLISHER") "Altium Limited"))
      (libsource (lib "FriedParts") (part "Res1"))
    )
    (comp (ref "R89")
      (value "33k Ohms 1%")
      (footprint "SM/R_0603")
      (description "resistor, rc22h 0603 33k; power rating:0.1w;")
      (fields (field (name "MFRPARTNUM") "RC0603FR-0733KL") (field (name "PUBLISHER") "Altium Limited"))
      (libsource (lib "FriedParts") (part "Res1"))
    )
    (comp (ref "R90")
      (value "33k Ohms 1%")
      (footprint "SM/R_0603")
      (description "resistor, rc22h 0603 33k; power rating:0.1w;")
      (fields (field (name "MFRPARTNUM") "RC0603FR-0733KL") (field (name "PUBLISHER") "Altium Limited"))
      (libsource (lib "FriedParts") (part "Res1"))
    )
    (comp (ref "R91")
      (value "49.9k Ohms 1%")
      (footprint "SM/R_0603")
      (description "res thick film 0603 49.9k ohm 1% 1/10w ±100ppm/°c molded smd")
      (fields (field (name "MFRPARTNUM") "ERJ-3EKF4992V") (field (name "PUBLISHER") "Altium Limited"))
      (libsource (lib "FriedParts") (part "Res1"))
    )
    (comp (ref "R92")
      (value "20k Ohms 1%")
      (footprint "SM/R_0603")
      (description "res thick film 0603 20k ohm 1% 1/10w ?100ppm/?c molded smd")
      (fields (field (name "MFRPARTNUM") "ERJ-3EKF2002V") (field (name "PUBLISHER") "Altium Limited"))
      (libsource (lib "FriedParts") (part "Res1"))
    )
    (comp (ref "R93")
      (value "49.9k Ohms 1%")
      (footprint "SM/R_0603")
      (description "res thick film 0603 49.9k ohm 1% 1/10w ±100ppm/°c molded smd")
      (fields (field (name "MFRPARTNUM") "ERJ-3EKF4992V") (field (name "PUBLISHER") "Altium Limited"))
      (libsource (lib "FriedParts") (part "Res1"))
    )
    (comp (ref "R94")
      (value "20k Ohms 1%")
      (footprint "SM/R_0603")
      (description "res thick film 0603 20k ohm 1% 1/10w ?100ppm/?c molded smd")
      (fields (field (name "MFRPARTNUM") "ERJ-3EKF2002V") (field (name "PUBLISHER") "Altium Limited"))
      (libsource (lib "FriedParts") (part "Res1"))
    )
    (comp (ref "R95")
      (value "12k Ohms 1%")
      (footprint "SM/R_0603")
      (description "resistor, rc22h 0603 12k; resistance:12kohm; resistance")
      (fields (field (name "MFRPARTNUM") "RC0603FR-0712KL") (field (name "PUBLISHER") "Altium Limited"))
      (libsource (lib "FriedParts") (part "Res1"))
    )
    (comp (ref "R96")
      (value "12k Ohms 1%")
      (footprint "SM/R_0603")
      (description "resistor, rc22h 0603 12k; resistance:12kohm; resistance")
      (fields (field (name "MFRPARTNUM") "RC0603FR-0712KL") (field (name "PUBLISHER") "Altium Limited"))
      (libsource (lib "FriedParts") (part "Res1"))
    )
    (comp (ref "R97")
      (value "6.19k Ohms 1%")
      (footprint "SM/R_0603")
      (description "res thick film 0603 6.19k ohm 1% 1/10w ±100ppm/°c smd")
      (fields (field (name "MFRPARTNUM") "ERJ-3EKF6191V") (field (name "PUBLISHER") "Altium Limited"))
      (libsource (lib "FriedParts") (part "Res1"))
    )
    (comp (ref "R98")
      (value "6.19k Ohms 1%")
      (footprint "SM/R_0603")
      (description "res thick film 0603 6.19k ohm 1% 1/10w ±100ppm/°c smd")
      (fields (field (name "MFRPARTNUM") "ERJ-3EKF6191V") (field (name "PUBLISHER") "Altium Limited"))
      (libsource (lib "FriedParts") (part "Res1"))
    )
    (comp (ref "R99")
      (value "12k Ohms 1%")
      (footprint "SM/R_0603")
      (description "resistor, rc22h 0603 12k; resistance:12kohm; resistance")
      (fields (field (name "MFRPARTNUM") "RC0603FR-0712KL") (field (name "PUBLISHER") "Altium Limited"))
      (libsource (lib "FriedParts") (part "Res1"))
    )
    (comp (ref "R100")
      (value "12k Ohms 1%")
      (footprint "SM/R_0603")
      (description "resistor, rc22h 0603 12k; resistance:12kohm; resistance")
      (fields (field (name "MFRPARTNUM") "RC0603FR-0712KL") (field (name "PUBLISHER") "Altium Limited"))
      (libsource (lib "FriedParts") (part "Res1"))
    )
    (comp (ref "R101")
      (value "6.19k Ohms 1%")
      (footprint "SM/R_0603")
      (description "res thick film 0603 6.19k ohm 1% 1/10w ±100ppm/°c smd")
      (fields (field (name "MFRPARTNUM") "ERJ-3EKF6191V") (field (name "PUBLISHER") "Altium Limited"))
      (libsource (lib "FriedParts") (part "Res1"))
    )
    (comp (ref "R102")
      (value "6.19k Ohms 1%")
      (footprint "SM/R_0603")
      (description "res thick film 0603 6.19k ohm 1% 1/10w ±100ppm/°c smd")
      (fields (field (name "MFRPARTNUM") "ERJ-3EKF6191V") (field (name "PUBLISHER") "Altium Limited"))
      (libsource (lib "FriedParts") (part "Res1"))
    )
    (comp (ref "R103")
      (value "50 Ohm 1%")
      (footprint "SM/R_0603")
      (description "; resistance:50ohm; resistance tolerance:± 0.1%; power")
      (fields (field (name "MFRPARTNUM") "FC0603E50R0BTBST1") (field (name "PUBLISHER") "Altium Limited"))
      (libsource (lib "FriedParts") (part "Res1"))
    )
    (comp (ref "R104")
      (value "4.7k Ohms 1%")
      (footprint "SM/R_0603")
      (description "resistor, rc22h 0603 470k; power rating:0.1w;")
      (fields (field (name "MFRPARTNUM") "RC0603FR-07470KL") (field (name "PUBLISHER") "Altium Limited"))
      (libsource (lib "FriedParts") (part "Res1"))
    )
    (comp (ref "R105")
      (value "7.5k Ohms 1%")
      (footprint "SM/R_0603")
      (description "res thick film 0603 7.5k ohm 1% 1/10w ±100ppm/°c molded smd")
      (fields (field (name "MFRPARTNUM") "ERJ-3EKF7501V") (field (name "PUBLISHER") "Altium Limited"))
      (libsource (lib "FriedParts") (part "Res1"))
    )
    (comp (ref "R106")
      (value "4.7k Ohms 1%")
      (footprint "SM/R_0603")
      (description "resistor, rc22h 0603 470k; power rating:0.1w;")
      (fields (field (name "MFRPARTNUM") "RC0603FR-07470KL") (field (name "PUBLISHER") "Altium Limited"))
      (libsource (lib "FriedParts") (part "Res1"))
    )
    (comp (ref "R107")
      (value "7.5k Ohms 1%")
      (footprint "SM/R_0603")
      (description "res thick film 0603 7.5k ohm 1% 1/10w ±100ppm/°c molded smd")
      (fields (field (name "MFRPARTNUM") "ERJ-3EKF7501V") (field (name "PUBLISHER") "Altium Limited"))
      (libsource (lib "FriedParts") (part "Res1"))
    )
    (comp (ref "R108")
      (value "10k Ohms 1%")
      (footprint "SM/R_0603")
      (description "resistor, rc22h 0603 1k; power rating:0.1w;")
      (fields (field (name "MFRPARTNUM") "RC0603FR-071KL") (field (name "PUBLISHER") "Altium Limited"))
      (libsource (lib "FriedParts") (part "Res1"))
    )
    (comp (ref "R109")
      (value "4.99k Ohms 1%")
      (footprint "SM/R_0603")
      (description "res thick film 0603 4.99k ohm 1% 1/10w ±100ppm/°c smd")
      (fields (field (name "MFRPARTNUM") "ERJ-3EKF4991V") (field (name "PUBLISHER") "Altium Limited"))
      (libsource (lib "FriedParts") (part "Res1"))
    )
    (comp (ref "R110")
      (value "10k Ohms 1%")
      (footprint "SM/R_0603")
      (description "resistor, rc22h 0603 1k; power rating:0.1w;")
      (fields (field (name "MFRPARTNUM") "RC0603FR-071KL") (field (name "PUBLISHER") "Altium Limited"))
      (libsource (lib "FriedParts") (part "Res1"))
    )
    (comp (ref "R111")
      (value "4.99k Ohms 1%")
      (footprint "SM/R_0603")
      (description "res thick film 0603 4.99k ohm 1% 1/10w ±100ppm/°c smd")
      (fields (field (name "MFRPARTNUM") "ERJ-3EKF4991V") (field (name "PUBLISHER") "Altium Limited"))
      (libsource (lib "FriedParts") (part "Res1"))
    )
    (comp (ref "R112")
      (value "1.5k Ohms 1%")
      (footprint "SM/R_0603")
      (description "resistor, rc22h 0603 1k5; power rating:0.1w;")
      (fields (field (name "MFRPARTNUM") "RC0603FR-071K5L") (field (name "PUBLISHER") "Altium Limited"))
      (libsource (lib "FriedParts") (part "Res1"))
    )
    (comp (ref "R113")
      (value "1.5k Ohms 1%")
      (footprint "SM/R_0603")
      (description "resistor, rc22h 0603 1k5; power rating:0.1w;")
      (fields (field (name "MFRPARTNUM") "RC0603FR-071K5L") (field (name "PUBLISHER") "Altium Limited"))
      (libsource (lib "FriedParts") (part "Res1"))
    )
    (comp (ref "R114")
      (value "1.5k Ohms 1%")
      (footprint "SM/R_0603")
      (description "resistor, rc22h 0603 1k5; power rating:0.1w;")
      (fields (field (name "MFRPARTNUM") "RC0603FR-071K5L") (field (name "PUBLISHER") "Altium Limited"))
      (libsource (lib "FriedParts") (part "Res1"))
    )
    (comp (ref "R115")
      (value "1.5k Ohms 1%")
      (footprint "SM/R_0603")
      (description "resistor, rc22h 0603 1k5; power rating:0.1w;")
      (fields (field (name "MFRPARTNUM") "RC0603FR-071K5L") (field (name "PUBLISHER") "Altium Limited"))
      (libsource (lib "FriedParts") (part "Res1"))
    )
    (comp (ref "R116")
      (value "1k Ohms 1%")
      (footprint "SM/C_0603")
      (description "RES 1.00K OHM 1/10W 1% 0603 SMD")
      (fields (field (name "MFRPARTNUM") "ERJ-3EKF1001V"))
      (libsource (lib "FriedParts") (part "R"))
    )
    (comp (ref "R117")
      (value "1k Ohms 1%")
      (footprint "SM/C_0603")
      (description "RES 1.00K OHM 1/10W 1% 0603 SMD")
      (fields (field (name "MFRPARTNUM") "ERJ-3EKF1001V"))
      (libsource (lib "FriedParts") (part "R"))
    )
    (comp (ref "R118")
      (value "8.87K Ohms 1%")
      (footprint "SM/C_0603")
      (description "res thick film 0603 8.87k ohm 1% 1/10w ±100ppm/°c molded smd")
      (fields (field (name "MFRPARTNUM") "ERJ-3EKF8871V") (field (name "PUBLISHER") "Altium Limited"))
      (libsource (lib "FriedParts") (part "Res1"))
    )
    (comp (ref "R119")
      (value "8.87K Ohms 1%")
      (footprint "SM/C_0603")
      (description "res thick film 0603 8.87k ohm 1% 1/10w ±100ppm/°c molded smd")
      (fields (field (name "MFRPARTNUM") "ERJ-3EKF8871V") (field (name "PUBLISHER") "Altium Limited"))
      (libsource (lib "FriedParts") (part "Res1"))
    )
    (comp (ref "R120")
      (value "0 Ohms 0")
      (footprint "SM/R_0603")
      (description "res thick film 0603 0 ohm 1/10w molded smd punched carrier")
      (fields (field (name "MFRPARTNUM") "ERJ-3GEY0R00V") (field (name "PUBLISHER") "Altium Limited"))
      (libsource (lib "FriedParts") (part "Res1"))
    )
    (comp (ref "R121")
      (value "0 Ohms 0")
      (footprint "SM/R_0603")
      (description "res thick film 0603 0 ohm 1/10w molded smd punched carrier")
      (fields (field (name "MFRPARTNUM") "ERJ-3GEY0R00V") (field (name "PUBLISHER") "Altium Limited"))
      (libsource (lib "FriedParts") (part "Res1"))
    )
    (comp (ref "R122")
      (value "0 Ohms 0")
      (footprint "SM/R_0603")
      (description "res thick film 0603 0 ohm 1/10w molded smd punched carrier")
      (fields (field (name "MFRPARTNUM") "ERJ-3GEY0R00V") (field (name "PUBLISHER") "Altium Limited"))
      (libsource (lib "FriedParts") (part "Res1"))
    )
    (comp (ref "R123")
      (value "0 Ohms 0")
      (footprint "SM/R_0603")
      (description "res thick film 0603 0 ohm 1/10w molded smd punched carrier")
      (fields (field (name "MFRPARTNUM") "ERJ-3GEY0R00V") (field (name "PUBLISHER") "Altium Limited"))
      (libsource (lib "FriedParts") (part "Res1"))
    )
    (comp (ref "R124")
      (value "0 Ohms 0")
      (footprint "SM/R_0603")
      (description "res thick film 0603 0 ohm 1/10w molded smd punched carrier")
      (fields (field (name "MFRPARTNUM") "ERJ-3GEY0R00V") (field (name "PUBLISHER") "Altium Limited"))
      (libsource (lib "FriedParts") (part "Res1"))
    )
    (comp (ref "R125")
      (value "0 Ohms 0")
      (footprint "SM/R_0603")
      (description "res thick film 0603 0 ohm 1/10w molded smd punched carrier")
      (fields (field (name "MFRPARTNUM") "ERJ-3GEY0R00V") (field (name "PUBLISHER") "Altium Limited"))
      (libsource (lib "FriedParts") (part "Res1"))
    )
    (comp (ref "R126")
      (value "1k Ohms 1%")
      (footprint "SM/C_0603")
      (description "RES 1.00K OHM 1/10W 1% 0603 SMD")
      (fields (field (name "MFRPARTNUM") "ERJ-3EKF1001V"))
      (libsource (lib "FriedParts") (part "R"))
    )
    (comp (ref "R127")
      (value "1k Ohms 1%")
      (footprint "SM/C_0603")
      (description "RES 1.00K OHM 1/10W 1% 0603 SMD")
      (fields (field (name "MFRPARTNUM") "ERJ-3EKF1001V"))
      (libsource (lib "FriedParts") (part "R"))
    )
    (comp (ref "R128")
      (value "1k Ohms 1%")
      (footprint "SM/C_0603")
      (description "RES 1.00K OHM 1/10W 1% 0603 SMD")
      (fields (field (name "MFRPARTNUM") "ERJ-3EKF1001V"))
      (libsource (lib "FriedParts") (part "R"))
    )
    (comp (ref "R129")
      (value "1k Ohms 1%")
      (footprint "SM/C_0603")
      (description "RES 1.00K OHM 1/10W 1% 0603 SMD")
      (fields (field (name "MFRPARTNUM") "ERJ-3EKF1001V"))
      (libsource (lib "FriedParts") (part "R"))
    )
    (comp (ref "R130")
      (value "0 Ohms 0")
      (footprint "SM/R_0603")
      (description "res thick film 0603 0 ohm 1/10w molded smd punched carrier")
      (fields (field (name "MFRPARTNUM") "ERJ-3GEY0R00V") (field (name "PUBLISHER") "Altium Limited"))
      (libsource (lib "FriedParts") (part "Res1"))
    )
    (comp (ref "R131")
      (value "0 Ohms 0")
      (footprint "SM/R_0603")
      (description "res thick film 0603 0 ohm 1/10w molded smd punched carrier")
      (fields (field (name "MFRPARTNUM") "ERJ-3GEY0R00V") (field (name "PUBLISHER") "Altium Limited"))
      (libsource (lib "FriedParts") (part "Res1"))
    )
    (comp (ref "R132")
      (value "0 Ohms 0")
      (footprint "SM/R_0603")
      (description "res thick film 0603 0 ohm 1/10w molded smd punched carrier")
      (fields (field (name "MFRPARTNUM") "ERJ-3GEY0R00V") (field (name "PUBLISHER") "Altium Limited"))
      (libsource (lib "FriedParts") (part "Res1"))
    )
    (comp (ref "R133")
      (value "0 Ohms 0")
      (footprint "SM/R_0603")
      (description "res thick film 0603 0 ohm 1/10w molded smd punched carrier")
      (fields (field (name "MFRPARTNUM") "ERJ-3GEY0R00V") (field (name "PUBLISHER") "Altium Limited"))
      (libsource (lib "FriedParts") (part "Res1"))
    )
    (comp (ref "R134")
      (value "0 Ohms 0")
      (footprint "SM/R_0603")
      (description "res thick film 0603 0 ohm 1/10w molded smd punched carrier")
      (fields (field (name "MFRPARTNUM") "ERJ-3GEY0R00V") (field (name "PUBLISHER") "Altium Limited"))
      (libsource (lib "FriedParts") (part "Res1"))
    )
    (comp (ref "R135")
      (value "0 Ohms 0")
      (footprint "SM/R_0603")
      (description "res thick film 0603 0 ohm 1/10w molded smd punched carrier")
      (fields (field (name "MFRPARTNUM") "ERJ-3GEY0R00V") (field (name "PUBLISHER") "Altium Limited"))
      (libsource (lib "FriedParts") (part "Res1"))
    )
    (comp (ref "R136")
      (value "0 Ohms 0")
      (footprint "SM/R_0603")
      (description "res thick film 0603 0 ohm 1/10w molded smd punched carrier")
      (fields (field (name "MFRPARTNUM") "ERJ-3GEY0R00V") (field (name "PUBLISHER") "Altium Limited"))
      (libsource (lib "FriedParts") (part "Res1"))
    )
    (comp (ref "R137")
      (value "0 Ohms 0")
      (footprint "SM/R_0603")
      (description "res thick film 0603 0 ohm 1/10w molded smd punched carrier")
      (fields (field (name "MFRPARTNUM") "ERJ-3GEY0R00V") (field (name "PUBLISHER") "Altium Limited"))
      (libsource (lib "FriedParts") (part "Res1"))
    )
    (comp (ref "R138")
      (value "0 Ohms 0")
      (footprint "SM/R_0603")
      (description "res thick film 0603 0 ohm 1/10w molded smd punched carrier")
      (fields (field (name "MFRPARTNUM") "ERJ-3GEY0R00V") (field (name "PUBLISHER") "Altium Limited"))
      (libsource (lib "FriedParts") (part "Res1"))
    )
    (comp (ref "R139")
      (value "0 Ohms 0")
      (footprint "SM/R_0603")
      (description "res thick film 0603 0 ohm 1/10w molded smd punched carrier")
      (fields (field (name "MFRPARTNUM") "ERJ-3GEY0R00V") (field (name "PUBLISHER") "Altium Limited"))
      (libsource (lib "FriedParts") (part "Res1"))
    )
    (comp (ref "R140")
      (value "0 Ohms 0")
      (footprint "SM/R_0603")
      (description "res thick film 0603 0 ohm 1/10w molded smd punched carrier")
      (fields (field (name "MFRPARTNUM") "ERJ-3GEY0R00V") (field (name "PUBLISHER") "Altium Limited"))
      (libsource (lib "FriedParts") (part "Res1"))
    )
    (comp (ref "R141")
      (value "0 Ohms 0")
      (footprint "SM/R_0603")
      (description "res thick film 0603 0 ohm 1/10w molded smd punched carrier")
      (fields (field (name "MFRPARTNUM") "ERJ-3GEY0R00V") (field (name "PUBLISHER") "Altium Limited"))
      (libsource (lib "FriedParts") (part "Res1"))
    )
    (comp (ref "R142")
      (value "0 Ohms 0")
      (footprint "SM/R_0603")
      (description "res thick film 0603 0 ohm 1/10w molded smd punched carrier")
      (fields (field (name "MFRPARTNUM") "ERJ-3GEY0R00V") (field (name "PUBLISHER") "Altium Limited"))
      (libsource (lib "FriedParts") (part "Res1"))
    )
    (comp (ref "R143")
      (value "0 Ohms 0")
      (footprint "SM/R_0603")
      (description "res thick film 0603 0 ohm 1/10w molded smd punched carrier")
      (fields (field (name "MFRPARTNUM") "ERJ-3GEY0R00V") (field (name "PUBLISHER") "Altium Limited"))
      (libsource (lib "FriedParts") (part "Res1"))
    )
    (comp (ref "S1")
      (value "CKN9104CT-ND")
      (footprint "MOM-SW")
      (description "SW - SPST-NO - SM")
      (libsource (lib "FriedParts") (part "MOM-BUT"))
    )
    (comp (ref "S2")
      (value "CKN9104CT-ND")
      (footprint "MOM-SW")
      (description "SW - SPST-NO - SM")
      (libsource (lib "FriedParts") (part "MOM-BUT"))
    )
    (comp (ref "SW1")
      (value "10 pos spst switch 219-10MST")
      (footprint "SW-10pos-SPST")
      (libsource (lib "FriedParts") (part "10 pos spst switch 219-10MST"))
    )
    (comp (ref "TP-5V")
      (value "5016")
      (footprint "TEST_PT_SMD")
      (description "test point, connector; connector type:test; mounting type:pc")
      (libsource (lib "FriedParts") (part "TEST_PT"))
    )
    (comp (ref "TP1")
      (value "5016")
      (footprint "TEST_PT_SMD")
      (description "test point, connector; connector type:test; mounting type:pc")
      (libsource (lib "FriedParts") (part "TEST_PT"))
    )
    (comp (ref "TP2")
      (value "5016")
      (footprint "TEST_PT_SMD")
      (description "test point, connector; connector type:test; mounting type:pc")
      (libsource (lib "FriedParts") (part "TEST_PT"))
    )
    (comp (ref "TP2V5")
      (value "5016")
      (footprint "TEST_PT_SMD")
      (description "test point, connector; connector type:test; mounting type:pc")
      (libsource (lib "FriedParts") (part "TEST_PT"))
    )
    (comp (ref "TP3")
      (value "5016")
      (footprint "TEST_PT_SMD")
      (description "test point, connector; connector type:test; mounting type:pc")
      (libsource (lib "FriedParts") (part "TEST_PT"))
    )
    (comp (ref "TP4")
      (value "5016")
      (footprint "TEST_PT_SMD")
      (description "test point, connector; connector type:test; mounting type:pc")
      (libsource (lib "FriedParts") (part "TEST_PT"))
    )
    (comp (ref "TP5")
      (value "5016")
      (footprint "TEST_PT_SMD")
      (description "test point, connector; connector type:test; mounting type:pc")
      (libsource (lib "FriedParts") (part "TEST_PT"))
    )
    (comp (ref "TP5V")
      (value "5016")
      (footprint "TEST_PT_SMD")
      (description "test point, connector; connector type:test; mounting type:pc")
      (libsource (lib "FriedParts") (part "TEST_PT"))
    )
    (comp (ref "TP6")
      (value "5016")
      (footprint "TEST_PT_SMD")
      (description "test point, connector; connector type:test; mounting type:pc")
      (libsource (lib "FriedParts") (part "TEST_PT"))
    )
    (comp (ref "TP7")
      (value "5016")
      (footprint "TEST_PT_SMD")
      (description "test point, connector; connector type:test; mounting type:pc")
      (libsource (lib "FriedParts") (part "TEST_PT"))
    )
    (comp (ref "TP8")
      (value "5016")
      (footprint "TEST_PT_SMD")
      (description "test point, connector; connector type:test; mounting type:pc")
      (libsource (lib "FriedParts") (part "TEST_PT"))
    )
    (comp (ref "TP9")
      (value "5016")
      (footprint "TEST_PT_SMD")
      (description "test point, connector; connector type:test; mounting type:pc")
      (libsource (lib "FriedParts") (part "TEST_PT"))
    )
    (comp (ref "TP10")
      (value "5016")
      (footprint "TEST_PT_SMD")
      (description "test point, connector; connector type:test; mounting type:pc")
      (libsource (lib "FriedParts") (part "TEST_PT"))
    )
    (comp (ref "TP11")
      (value "5016")
      (footprint "TEST_PT_SMD")
      (description "test point, connector; connector type:test; mounting type:pc")
      (libsource (lib "FriedParts") (part "TEST_PT"))
    )
    (comp (ref "TP12")
      (value "5016")
      (footprint "TEST_PT_SMD")
      (description "test point, connector; connector type:test; mounting type:pc")
      (libsource (lib "FriedParts") (part "TEST_PT"))
    )
    (comp (ref "TP13")
      (value "5016")
      (footprint "TEST_PT_SMD")
      (description "test point, connector; connector type:test; mounting type:pc")
      (libsource (lib "FriedParts") (part "TEST_PT"))
    )
    (comp (ref "TP14")
      (value "5016")
      (footprint "TEST_PT_SMD")
      (description "test point, connector; connector type:test; mounting type:pc")
      (libsource (lib "FriedParts") (part "TEST_PT"))
    )
    (comp (ref "TP15")
      (value "5016")
      (footprint "TEST_PT_SMD")
      (description "test point, connector; connector type:test; mounting type:pc")
      (libsource (lib "FriedParts") (part "TEST_PT"))
    )
    (comp (ref "TP16")
      (value "5016")
      (footprint "TEST_PT_SMD")
      (description "test point, connector; connector type:test; mounting type:pc")
      (libsource (lib "FriedParts") (part "TEST_PT"))
    )
    (comp (ref "TP17")
      (value "5016")
      (footprint "TEST_PT_SMD")
      (description "test point, connector; connector type:test; mounting type:pc")
      (libsource (lib "FriedParts") (part "TEST_PT"))
    )
    (comp (ref "TP18")
      (value "5016")
      (footprint "TEST_PT_SMD")
      (description "test point, connector; connector type:test; mounting type:pc")
      (libsource (lib "FriedParts") (part "TEST_PT"))
    )
    (comp (ref "TP19")
      (value "5016")
      (footprint "TEST_PT_SMD")
      (description "test point, connector; connector type:test; mounting type:pc")
      (libsource (lib "FriedParts") (part "TEST_PT"))
    )
    (comp (ref "TP20")
      (value "5016")
      (footprint "TEST_PT_SMD")
      (description "test point, connector; connector type:test; mounting type:pc")
      (libsource (lib "FriedParts") (part "TEST_PT"))
    )
    (comp (ref "TP21")
      (value "5016")
      (footprint "TEST_PT_SMD")
      (description "test point, connector; connector type:test; mounting type:pc")
      (libsource (lib "FriedParts") (part "TEST_PT"))
    )
    (comp (ref "TP22")
      (value "5016")
      (footprint "TEST_PT_SMD")
      (description "test point, connector; connector type:test; mounting type:pc")
      (libsource (lib "FriedParts") (part "TEST_PT"))
    )
    (comp (ref "TP23")
      (value "5016")
      (footprint "TEST_PT_SMD")
      (description "test point, connector; connector type:test; mounting type:pc")
      (libsource (lib "FriedParts") (part "TEST_PT"))
    )
    (comp (ref "TP24")
      (value "5016")
      (footprint "TEST_PT_SMD")
      (description "test point, connector; connector type:test; mounting type:pc")
      (libsource (lib "FriedParts") (part "TEST_PT"))
    )
    (comp (ref "TP25")
      (value "5016")
      (footprint "TEST_PT_SMD")
      (description "test point, connector; connector type:test; mounting type:pc")
      (libsource (lib "FriedParts") (part "TEST_PT"))
    )
    (comp (ref "TP26")
      (value "5016")
      (footprint "TEST_PT_SMD")
      (description "test point, connector; connector type:test; mounting type:pc")
      (libsource (lib "FriedParts") (part "TEST_PT"))
    )
    (comp (ref "TP27")
      (value "5016")
      (footprint "TEST_PT_SMD")
      (description "test point, connector; connector type:test; mounting type:pc")
      (libsource (lib "FriedParts") (part "TEST_PT"))
    )
    (comp (ref "TP28")
      (value "5016")
      (footprint "TEST_PT_SMD")
      (description "test point, connector; connector type:test; mounting type:pc")
      (libsource (lib "FriedParts") (part "TEST_PT"))
    )
    (comp (ref "TP29")
      (value "5016")
      (footprint "TEST_PT_SMD")
      (description "test point, connector; connector type:test; mounting type:pc")
      (libsource (lib "FriedParts") (part "TEST_PT"))
    )
    (comp (ref "TP30")
      (value "5016")
      (footprint "TEST_PT_SMD")
      (description "test point, connector; connector type:test; mounting type:pc")
      (libsource (lib "FriedParts") (part "TEST_PT"))
    )
    (comp (ref "TP31")
      (value "5016")
      (footprint "TEST_PT_SMD")
      (description "test point, connector; connector type:test; mounting type:pc")
      (libsource (lib "FriedParts") (part "TEST_PT"))
    )
    (comp (ref "TP32")
      (value "5016")
      (footprint "TEST_PT_SMD")
      (description "test point, connector; connector type:test; mounting type:pc")
      (libsource (lib "FriedParts") (part "TEST_PT"))
    )
    (comp (ref "TP33")
      (value "5016")
      (footprint "TEST_PT_SMD")
      (description "test point, connector; connector type:test; mounting type:pc")
      (libsource (lib "FriedParts") (part "TEST_PT"))
    )
    (comp (ref "TP34")
      (value "5016")
      (footprint "TEST_PT_SMD")
      (description "test point, connector; connector type:test; mounting type:pc")
      (libsource (lib "FriedParts") (part "TEST_PT"))
    )
    (comp (ref "TP35")
      (value "5016")
      (footprint "TEST_PT_SMD")
      (description "test point, connector; connector type:test; mounting type:pc")
      (libsource (lib "FriedParts") (part "TEST_PT"))
    )
    (comp (ref "TPSCL")
      (value "5016")
      (footprint "TEST_PT_SMD")
      (description "test point, connector; connector type:test; mounting type:pc")
      (libsource (lib "FriedParts") (part "TEST_PT"))
    )
    (comp (ref "TPSDA")
      (value "5016")
      (footprint "TEST_PT_SMD")
      (description "test point, connector; connector type:test; mounting type:pc")
      (libsource (lib "FriedParts") (part "TEST_PT"))
    )
    (comp (ref "TP_-2V5")
      (value "5016")
      (footprint "TEST_PT_SMD")
      (description "test point, connector; connector type:test; mounting type:pc")
      (libsource (lib "FriedParts") (part "TEST_PT"))
    )
    (comp (ref "TP_CS0")
      (value "5016")
      (footprint "TEST_PT_SMD")
      (description "test point, connector; connector type:test; mounting type:pc")
      (libsource (lib "FriedParts") (part "TEST_PT"))
    )
    (comp (ref "TP_CS1")
      (value "5016")
      (footprint "TEST_PT_SMD")
      (description "test point, connector; connector type:test; mounting type:pc")
      (libsource (lib "FriedParts") (part "TEST_PT"))
    )
    (comp (ref "TP_F0")
      (value "5016")
      (footprint "TEST_PT_SMD")
      (description "test point, connector; connector type:test; mounting type:pc")
      (libsource (lib "FriedParts") (part "TEST_PT"))
    )
    (comp (ref "TP_F1")
      (value "5016")
      (footprint "TEST_PT_SMD")
      (description "test point, connector; connector type:test; mounting type:pc")
      (libsource (lib "FriedParts") (part "TEST_PT"))
    )
    (comp (ref "TP_F2")
      (value "5016")
      (footprint "TEST_PT_SMD")
      (description "test point, connector; connector type:test; mounting type:pc")
      (libsource (lib "FriedParts") (part "TEST_PT"))
    )
    (comp (ref "TP_F3")
      (value "5016")
      (footprint "TEST_PT_SMD")
      (description "test point, connector; connector type:test; mounting type:pc")
      (libsource (lib "FriedParts") (part "TEST_PT"))
    )
    (comp (ref "TP_F4")
      (value "5016")
      (footprint "TEST_PT_SMD")
      (description "test point, connector; connector type:test; mounting type:pc")
      (libsource (lib "FriedParts") (part "TEST_PT"))
    )
    (comp (ref "TP_F5")
      (value "5016")
      (footprint "TEST_PT_SMD")
      (description "test point, connector; connector type:test; mounting type:pc")
      (libsource (lib "FriedParts") (part "TEST_PT"))
    )
    (comp (ref "TP_F6")
      (value "5016")
      (footprint "TEST_PT_SMD")
      (description "test point, connector; connector type:test; mounting type:pc")
      (libsource (lib "FriedParts") (part "TEST_PT"))
    )
    (comp (ref "TP_F7")
      (value "5016")
      (footprint "TEST_PT_SMD")
      (description "test point, connector; connector type:test; mounting type:pc")
      (libsource (lib "FriedParts") (part "TEST_PT"))
    )
    (comp (ref "TP_GND")
      (value "5016")
      (footprint "TEST_PT_SMD")
      (description "test point, connector; connector type:test; mounting type:pc")
      (libsource (lib "FriedParts") (part "TEST_PT"))
    )
    (comp (ref "TP_GND2")
      (value "5016")
      (footprint "TEST_PT_SMD")
      (description "test point, connector; connector type:test; mounting type:pc")
      (libsource (lib "FriedParts") (part "TEST_PT"))
    )
    (comp (ref "TP_MISO")
      (value "5016")
      (footprint "TEST_PT_SMD")
      (description "test point, connector; connector type:test; mounting type:pc")
      (libsource (lib "FriedParts") (part "TEST_PT"))
    )
    (comp (ref "TP_MOSI")
      (value "5016")
      (footprint "TEST_PT_SMD")
      (description "test point, connector; connector type:test; mounting type:pc")
      (libsource (lib "FriedParts") (part "TEST_PT"))
    )
    (comp (ref "TP_SCK")
      (value "5016")
      (footprint "TEST_PT_SMD")
      (description "test point, connector; connector type:test; mounting type:pc")
      (libsource (lib "FriedParts") (part "TEST_PT"))
    )
    (comp (ref "U1")
      (value "DF206ST-G")
      (footprint "BridgeRectifier-DFS")
      (description "schottky diode; operating temperature range:0°c to +70°c;")
      (libsource (lib "FriedParts") (part "Bridge_Rectifier"))
    )
    (comp (ref "U2")
      (value "LTC6252")
      (footprint "TSOT-23-LTC6252-OpAmp")
      (description "op amp, r/r 200mhz single, soic8; no. of amplifiers:1; op amp")
      (libsource (lib "FriedParts") (part "LTC6252"))
    )
    (comp (ref "U3")
      (value "LTC6254CMS#PBF-ND")
      (footprint "MSOP-16Lead-LTC6254")
      (description "op amp, dual, r-r, 180mhz, 8msop; op amp type:unity gain")
      (libsource (lib "FriedParts") (part "LTC6254"))
    )
    (comp (ref "U4")
      (value "ADG636YRUZ")
      (footprint "TSSOP-14Lead-AnalogDevices-ADG636")
      (description "switch, spdt dual, tssop14, 636; switch type, analogue:spdt;")
      (libsource (lib "FriedParts") (part "ADG636"))
    )
    (comp (ref "U5")
      (value "LTC6252")
      (footprint "TSOT-23-LTC6252-OpAmp")
      (description "op amp, r/r 200mhz single, soic8; no. of amplifiers:1; op amp")
      (libsource (lib "FriedParts") (part "LTC6252"))
    )
    (comp (ref "U6")
      (value "ATMEGA32U4-AU")
      (footprint "TQFP80P1200X1200X120-44L")
      (description "mcu, 8bit, avr, 32k flash, usb, 44tqfp; eeprom memory")
      (libsource (lib "FriedParts") (part "ATMega32U4"))
    )
    (comp (ref "U7")
      (value "LTC6254CMS#PBF-ND")
      (footprint "MSOP-16Lead-LTC6254")
      (description "op amp, dual, r-r, 180mhz, 8msop; op amp type:unity gain")
      (libsource (lib "FriedParts") (part "LTC6254"))
    )
    (comp (ref "U8")
      (value "74HC157DB,112")
      (footprint "SSOP16 NXP")
      (description "ic quad 2-in mux 16-ssop")
      (libsource (lib "FriedParts") (part "74HC157DB,112-4x2x1mux"))
    )
    (comp (ref "U9")
      (value "74HC157DB,112")
      (footprint "SSOP16 NXP")
      (description "ic quad 2-in mux 16-ssop")
      (libsource (lib "FriedParts") (part "74HC157DB,112-4x2x1mux"))
    )
    (comp (ref "U10")
      (value "LTC6254CMS#PBF-ND")
      (footprint "MSOP-16Lead-LTC6254")
      (description "op amp, dual, r-r, 180mhz, 8msop; op amp type:unity gain")
      (libsource (lib "FriedParts") (part "LTC6254"))
    )
    (comp (ref "U11")
      (value "LTC6254CMS#PBF-ND")
      (footprint "MSOP-16Lead-LTC6254")
      (description "op amp, dual, r-r, 180mhz, 8msop; op amp type:unity gain")
      (libsource (lib "FriedParts") (part "LTC6254"))
    )
    (comp (ref "U12")
      (value "LMP8100-ProgrammableGainAmp")
      (footprint "SOIC-14pin-National-Semiconductor")
      (libsource (lib "FriedParts") (part "LMP8100-ProgrammableGainAmp"))
    )
    (comp (ref "U13")
      (value "LTC6254CMS#PBF-ND")
      (footprint "MSOP-16Lead-LTC6254")
      (description "op amp, dual, r-r, 180mhz, 8msop; op amp type:unity gain")
      (libsource (lib "FriedParts") (part "LTC6254"))
    )
    (comp (ref "U14")
      (value "LTC6254CMS#PBF-ND")
      (footprint "MSOP-16Lead-LTC6254")
      (description "op amp, dual, r-r, 180mhz, 8msop; op amp type:unity gain")
      (libsource (lib "FriedParts") (part "LTC6254"))
    )
    (comp (ref "U15")
      (value "LMP8100-ProgrammableGainAmp")
      (footprint "SOIC-14pin-National-Semiconductor")
      (libsource (lib "FriedParts") (part "LMP8100-ProgrammableGainAmp"))
    )
    (comp (ref "U16")
      (value "LTC6254CMS#PBF-ND")
      (footprint "MSOP-16Lead-LTC6254")
      (description "op amp, dual, r-r, 180mhz, 8msop; op amp type:unity gain")
      (libsource (lib "FriedParts") (part "LTC6254"))
    )
    (comp (ref "U17")
      (value "LTC6254CMS#PBF-ND")
      (footprint "MSOP-16Lead-LTC6254")
      (description "op amp, dual, r-r, 180mhz, 8msop; op amp type:unity gain")
      (libsource (lib "FriedParts") (part "LTC6254"))
    )
    (comp (ref "U18")
      (value "ADG658YRUZ")
      (footprint "TSSOP-16-pin-analog-devices-RU-16")
      (description "mux, 8-ch, smd, tssop16, 658; analogue multiplexer")
      (libsource (lib "FriedParts") (part "ADG658"))
    )
    (comp (ref "U19")
      (value "ADG658YRUZ")
      (footprint "TSSOP-16-pin-analog-devices-RU-16")
      (description "mux, 8-ch, smd, tssop16, 658; analogue multiplexer")
      (libsource (lib "FriedParts") (part "ADG658"))
    )
    (comp (ref "VR1")
      (value "LM317EMP/NOPB")
      (footprint "LM317-SOT233-POS-ADJ-VOLT_REG")
      (description "v reg, linear, 37v, smd; voltage regulator type:adjustable")
      (libsource (lib "FriedParts") (part "ADJ_VOLT_REG"))
    )
    (comp (ref "VR2")
      (value "LM317EMP/NOPB")
      (footprint "LM317-SOT233-POS-ADJ-VOLT_REG")
      (description "v reg, linear, 37v, smd; voltage regulator type:adjustable")
      (libsource (lib "FriedParts") (part "ADJ_VOLT_REG"))
    )
    (comp (ref "VR3")
      (value "LM337IMP/NOPB")
      (footprint "LM337-ADJ-NEG-VOLT-REG")
      (description "linear voltage regulator ic; output voltage adjustable")
      (libsource (lib "") (part "ADJ_VOLT_REG_1"))
    )
    (comp (ref "VR4")
      (value "LM337IMP/NOPB")
      (footprint "LM337-ADJ-NEG-VOLT-REG")
      (description "linear voltage regulator ic; output voltage adjustable")
      (libsource (lib "") (part "ADJ_VOLT_REG_1"))
    )
    (comp (ref "X1")
      (value "PL30-12-130B")
      (footprint "TRANSFORMER-DUAL-PRIMARY")
      (description "transformers 12.6vct @ 2.40a 6.3v @ 4.80a")
      (libsource (lib "FriedParts") (part "PowerTransformer-DualIput-Tamura-PL30-12-130B"))
    )
    (comp (ref "Y1")
      (value "16.000 MHz")
      (footprint "ECS/CSM-7/2")
      (description "CRYSTAL 16.00MHZ 20PF SMD")
      (fields (field (name "MFRPARTNUM") "ECS-160-20-5P-TR"))
      (libsource (lib "FriedParts") (part "CRYSTAL"))
    )
  )
  (nets
    (net (code "11") (name "+2.5V") (class "Default")
      (node (ref "C102") (pin "2") (pinfunction "2_2") (pintype "passive"))
      (node (ref "C104") (pin "2") (pinfunction "2_2") (pintype "passive"))
      (node (ref "C16") (pin "1") (pinfunction "1_1") (pintype "passive"))
      (node (ref "C29") (pin "1") (pinfunction "1_1") (pintype "passive"))
      (node (ref "C4") (pin "1") (pinfunction "1_1") (pintype "passive"))
      (node (ref "C44") (pin "1") (pinfunction "1_1") (pintype "passive"))
      (node (ref "C51") (pin "2") (pinfunction "2_2") (pintype "passive"))
      (node (ref "C59") (pin "2") (pinfunction "2_2") (pintype "passive"))
      (node (ref "C6") (pin "1") (pinfunction "1_1") (pintype "passive"))
      (node (ref "C62") (pin "2") (pinfunction "2_2") (pintype "passive"))
      (node (ref "C81") (pin "2") (pinfunction "2_2") (pintype "passive"))
      (node (ref "C83") (pin "2") (pinfunction "2_2") (pintype "passive"))
      (node (ref "C88") (pin "2") (pinfunction "2_2") (pintype "passive"))
      (node (ref "R13") (pin "1") (pinfunction "1_1") (pintype "passive"))
      (node (ref "R44") (pin "2") (pinfunction "2_2") (pintype "passive"))
      (node (ref "R5") (pin "2") (pinfunction "2_2") (pintype "passive"))
      (node (ref "R7") (pin "2") (pinfunction "2_2") (pintype "passive"))
      (node (ref "TP2V5") (pin "1") (pinfunction "TP?_1") (pintype "passive"))
      (node (ref "U10") (pin "4") (pinfunction "V+_4") (pintype "passive"))
      (node (ref "U11") (pin "4") (pinfunction "V+_4") (pintype "passive"))
      (node (ref "U12") (pin "8") (pinfunction "V+_8") (pintype "passive"))
      (node (ref "U13") (pin "4") (pinfunction "V+_4") (pintype "passive"))
      (node (ref "U14") (pin "4") (pinfunction "V+_4") (pintype "passive"))
      (node (ref "U15") (pin "8") (pinfunction "V+_8") (pintype "passive"))
      (node (ref "U16") (pin "4") (pinfunction "V+_4") (pintype "passive"))
      (node (ref "U17") (pin "4") (pinfunction "V+_4") (pintype "passive"))
      (node (ref "U2") (pin "6") (pinfunction "V+_6") (pintype "passive"))
      (node (ref "U3") (pin "4") (pinfunction "V+_4") (pintype "passive"))
      (node (ref "U5") (pin "6") (pinfunction "V+_6") (pintype "passive"))
      (node (ref "U7") (pin "4") (pinfunction "V+_4") (pintype "passive"))
      (node (ref "VR2") (pin "3") (pinfunction "VOUT_3") (pintype "passive"))
    )
    (net (code "12") (name "+5V") (class "Default")
      (node (ref "C115") (pin "2") (pinfunction "2_2") (pintype "passive"))
      (node (ref "C117") (pin "2") (pinfunction "2_2") (pintype "passive"))
      (node (ref "C28") (pin "1") (pinfunction "1_1") (pintype "passive"))
      (node (ref "C3") (pin "1") (pinfunction "1_1") (pintype "passive"))
      (node (ref "C33") (pin "1") (pinfunction "1_1") (pintype "passive"))
      (node (ref "C34") (pin "1") (pinfunction "1_1") (pintype "passive"))
      (node (ref "C35") (pin "1") (pinfunction "1_1") (pintype "passive"))
      (node (ref "C36") (pin "1") (pinfunction "1_1") (pintype "passive"))
      (node (ref "C49") (pin "2") (pinfunction "2_2") (pintype "passive"))
      (node (ref "C50") (pin "2") (pinfunction "2_2") (pintype "passive"))
      (node (ref "J1") (pin "2") (pinfunction "VTG_2") (pintype "passive"))
      (node (ref "R3") (pin "2") (pinfunction "2_2") (pintype "passive"))
      (node (ref "R34") (pin "1") (pinfunction "1_1") (pintype "passive"))
      (node (ref "R4") (pin "1") (pinfunction "1_1") (pintype "passive"))
      (node (ref "R53") (pin "2") (pinfunction "2_2") (pintype "passive"))
      (node (ref "R57") (pin "1") (pinfunction "1_1") (pintype "passive"))
      (node (ref "R61") (pin "2") (pinfunction "2_2") (pintype "passive"))
      (node (ref "R62") (pin "2") (pinfunction "2_2") (pintype "passive"))
      (node (ref "R63") (pin "2") (pinfunction "2_2") (pintype "passive"))
      (node (ref "R64") (pin "2") (pinfunction "2_2") (pintype "passive"))
      (node (ref "R65") (pin "2") (pinfunction "2_2") (pintype "passive"))
      (node (ref "R66") (pin "2") (pinfunction "2_2") (pintype "passive"))
      (node (ref "R67") (pin "2") (pinfunction "2_2") (pintype "passive"))
      (node (ref "R68") (pin "2") (pinfunction "2_2") (pintype "passive"))
      (node (ref "R69") (pin "2") (pinfunction "2_2") (pintype "passive"))
      (node (ref "TP5V") (pin "1") (pinfunction "TP?_1") (pintype "passive"))
      (node (ref "U18") (pin "13") (pinfunction "VDD_13") (pintype "passive"))
      (node (ref "U19") (pin "13") (pinfunction "VDD_13") (pintype "passive"))
      (node (ref "U4") (pin "12") (pinfunction "VDD_12") (pintype "passive"))
      (node (ref "U6") (pin "14") (pinfunction "VCC_14") (pintype "passive"))
      (node (ref "U6") (pin "24") (pinfunction "AVCC_24") (pintype "passive"))
      (node (ref "U6") (pin "34") (pinfunction "VCC_34") (pintype "passive"))
      (node (ref "U6") (pin "42") (pinfunction "AREF_42") (pintype "passive"))
      (node (ref "U6") (pin "44") (pinfunction "AVCC_44") (pintype "passive"))
      (node (ref "U8") (pin "16") (pinfunction "Vcc_16") (pintype "passive"))
      (node (ref "U9") (pin "16") (pinfunction "Vcc_16") (pintype "passive"))
      (node (ref "VR1") (pin "3") (pinfunction "VOUT_3") (pintype "passive"))
    )
    (net (code "13") (name "-2.5V") (class "Default")
      (node (ref "C103") (pin "2") (pinfunction "2_2") (pintype "passive"))
      (node (ref "C105") (pin "2") (pinfunction "2_2") (pintype "passive"))
      (node (ref "C106") (pin "2") (pinfunction "2_2") (pintype "passive"))
      (node (ref "C13") (pin "2") (pinfunction "2_2") (pintype "passive"))
      (node (ref "C17") (pin "1") (pinfunction "1_1") (pintype "passive"))
      (node (ref "C30") (pin "1") (pinfunction "1_1") (pintype "passive"))
      (node (ref "C45") (pin "1") (pinfunction "1_1") (pintype "passive"))
      (node (ref "C5") (pin "1") (pinfunction "1_1") (pintype "passive"))
      (node (ref "C60") (pin "2") (pinfunction "2_2") (pintype "passive"))
      (node (ref "C63") (pin "2") (pinfunction "2_2") (pintype "passive"))
      (node (ref "C72") (pin "2") (pinfunction "2_2") (pintype "passive"))
      (node (ref "C82") (pin "2") (pinfunction "2_2") (pintype "passive"))
      (node (ref "C84") (pin "2") (pinfunction "2_2") (pintype "passive"))
      (node (ref "CON4") (pin "2") (pinfunction "2_2") (pintype "passive"))
      (node (ref "D3") (pin "2") (pinfunction "K_2") (pintype "passive"))
      (node (ref "R28") (pin "2") (pinfunction "2_2") (pintype "passive"))
      (node (ref "TP_-2V5") (pin "1") (pinfunction "TP?_1") (pintype "passive"))
      (node (ref "U10") (pin "13") (pinfunction "V-_13") (pintype "passive"))
      (node (ref "U11") (pin "13") (pinfunction "V-_13") (pintype "passive"))
      (node (ref "U12") (pin "7") (pinfunction "V-_7") (pintype "passive"))
      (node (ref "U13") (pin "13") (pinfunction "V-_13") (pintype "passive"))
      (node (ref "U14") (pin "13") (pinfunction "V-_13") (pintype "passive"))
      (node (ref "U15") (pin "7") (pinfunction "V-_7") (pintype "passive"))
      (node (ref "U16") (pin "13") (pinfunction "V-_13") (pintype "passive"))
      (node (ref "U17") (pin "13") (pinfunction "V-_13") (pintype "passive"))
      (node (ref "U2") (pin "2") (pinfunction "V-_2") (pintype "passive"))
      (node (ref "U3") (pin "13") (pinfunction "V-_13") (pintype "passive"))
      (node (ref "U5") (pin "2") (pinfunction "V-_2") (pintype "passive"))
      (node (ref "U7") (pin "13") (pinfunction "V-_13") (pintype "passive"))
      (node (ref "VR3") (pin "3") (pinfunction "VOUT_3") (pintype "passive"))
    )
    (net (code "14") (name "-5V") (class "Default")
      (node (ref "C116") (pin "1") (pinfunction "1_1") (pintype "passive"))
      (node (ref "C118") (pin "1") (pinfunction "1_1") (pintype "passive"))
      (node (ref "C24") (pin "2") (pinfunction "2_2") (pintype "passive"))
      (node (ref "C27") (pin "1") (pinfunction "1_1") (pintype "passive"))
      (node (ref "CON5") (pin "2") (pinfunction "2_2") (pintype "passive"))
      (node (ref "D4") (pin "2") (pinfunction "K_2") (pintype "passive"))
      (node (ref "R36") (pin "2") (pinfunction "2_2") (pintype "passive"))
      (node (ref "TP-5V") (pin "1") (pinfunction "TP?_1") (pintype "passive"))
      (node (ref "U18") (pin "3") (pinfunction "VSS_3") (pintype "passive"))
      (node (ref "U19") (pin "3") (pinfunction "VSS_3") (pintype "passive"))
      (node (ref "U4") (pin "3") (pinfunction "VSS_3") (pintype "passive"))
      (node (ref "VR4") (pin "3") (pinfunction "VOUT_3") (pintype "passive"))
    )
    (net (code "15") (name "/+6.3V") (class "Default")
      (node (ref "C1") (pin "1") (pinfunction "1_1") (pintype "passive"))
      (node (ref "C2") (pin "1") (pinfunction "1_1") (pintype "passive"))
      (node (ref "C7") (pin "1") (pinfunction "1_1") (pintype "passive"))
      (node (ref "C8") (pin "1") (pinfunction "1_1") (pintype "passive"))
      (node (ref "U1") (pin "4") (pinfunction "+_4") (pintype "passive"))
      (node (ref "VR1") (pin "1") (pinfunction "VIN_1") (pintype "passive"))
      (node (ref "VR2") (pin "1") (pinfunction "VIN_1") (pintype "passive"))
    )
    (net (code "16") (name "/-6.3V") (class "Default")
      (node (ref "C18") (pin "2") (pinfunction "2_2") (pintype "passive"))
      (node (ref "C19") (pin "2") (pinfunction "2_2") (pintype "passive"))
      (node (ref "C25") (pin "2") (pinfunction "2_2") (pintype "passive"))
      (node (ref "C26") (pin "2") (pinfunction "2_2") (pintype "passive"))
      (node (ref "U1") (pin "3") (pinfunction "-_3") (pintype "passive"))
      (node (ref "VR3") (pin "1") (pinfunction "VIN_1") (pintype "passive"))
      (node (ref "VR4") (pin "1") (pinfunction "VIN_1") (pintype "passive"))
    )
    (net (code "17") (name "/AUX_IN1") (class "Default")
      (node (ref "TP22") (pin "1") (pinfunction "TP?_1") (pintype "passive"))
      (node (ref "U19") (pin "9") (pinfunction "S8_9") (pintype "passive"))
    )
    (net (code "18") (name "/AUX_IN2") (class "Default")
      (node (ref "TP23") (pin "1") (pinfunction "TP?_1") (pintype "passive"))
      (node (ref "U18") (pin "9") (pinfunction "S8_9") (pintype "passive"))
    )
    (net (code "19") (name "/BOOT") (class "Default")
      (node (ref "R57") (pin "2") (pinfunction "2_2") (pintype "passive"))
      (node (ref "R60") (pin "1") (pinfunction "1_1") (pintype "passive"))
      (node (ref "S2") (pin "3") (pinfunction "3_3") (pintype "passive"))
      (node (ref "S2") (pin "4") (pinfunction "4_4") (pintype "passive"))
      (node (ref "U6") (pin "33") (pinfunction "PE2(~{HWB})_33") (pintype "passive"))
    )
    (net (code "20") (name "/BP_1k-100k_OUT1") (class "Default")
      (node (ref "C65") (pin "1") (pinfunction "1_1") (pintype "passive"))
      (node (ref "R135") (pin "2") (pinfunction "2_2") (pintype "passive"))
      (node (ref "TP10") (pin "1") (pinfunction "TP?_1") (pintype "passive"))
      (node (ref "U10") (pin "10") (pinfunction "OUTC_10") (pintype "passive"))
      (node (ref "U10") (pin "11") (pinfunction "-INC_11") (pintype "passive"))
    )
    (net (code "21") (name "/BP_1k-100k_OUT2") (class "Default")
      (node (ref "C67") (pin "1") (pinfunction "1_1") (pintype "passive"))
      (node (ref "R134") (pin "2") (pinfunction "2_2") (pintype "passive"))
      (node (ref "TP12") (pin "1") (pinfunction "TP?_1") (pintype "passive"))
      (node (ref "U11") (pin "10") (pinfunction "OUTC_10") (pintype "passive"))
      (node (ref "U11") (pin "11") (pinfunction "-INC_11") (pintype "passive"))
    )
    (net (code "22") (name "/BP_100k-250k_OUT1") (class "Default")
      (node (ref "C89") (pin "1") (pinfunction "1_1") (pintype "passive"))
      (node (ref "R137") (pin "2") (pinfunction "2_2") (pintype "passive"))
      (node (ref "TP13") (pin "1") (pinfunction "TP?_1") (pintype "passive"))
      (node (ref "U13") (pin "6") (pinfunction "-INB_6") (pintype "passive"))
      (node (ref "U13") (pin "7") (pinfunction "OUTB_7") (pintype "passive"))
    )
    (net (code "23") (name "/BP_100k-250k_OUT2") (class "Default")
      (node (ref "C90") (pin "1") (pinfunction "1_1") (pintype "passive"))
      (node (ref "R136") (pin "2") (pinfunction "2_2") (pintype "passive"))
      (node (ref "TP15") (pin "1") (pinfunction "TP?_1") (pintype "passive"))
      (node (ref "U14") (pin "6") (pinfunction "-INB_6") (pintype "passive"))
      (node (ref "U14") (pin "7") (pinfunction "OUTB_7") (pintype "passive"))
    )
    (net (code "24") (name "/BP_250k-500k_OUT1") (class "Default")
      (node (ref "C86") (pin "1") (pinfunction "1_1") (pintype "passive"))
      (node (ref "R139") (pin "2") (pinfunction "2_2") (pintype "passive"))
      (node (ref "TP14") (pin "1") (pinfunction "TP?_1") (pintype "passive"))
      (node (ref "U13") (pin "10") (pinfunction "OUTC_10") (pintype "passive"))
      (node (ref "U13") (pin "11") (pinfunction "-INC_11") (pintype "passive"))
    )
    (net (code "25") (name "/BP_250k-500k_OUT2") (class "Default")
      (node (ref "C87") (pin "1") (pinfunction "1_1") (pintype "passive"))
      (node (ref "R138") (pin "2") (pinfunction "2_2") (pintype "passive"))
      (node (ref "TP16") (pin "1") (pinfunction "TP?_1") (pintype "passive"))
      (node (ref "U14") (pin "10") (pinfunction "OUTC_10") (pintype "passive"))
      (node (ref "U14") (pin "11") (pinfunction "-INC_11") (pintype "passive"))
    )
    (net (code "26") (name "/BP_500k-2MHz_OUT1") (class "Default")
      (node (ref "C111") (pin "1") (pinfunction "1_1") (pintype "passive"))
      (node (ref "R141") (pin "2") (pinfunction "2_2") (pintype "passive"))
      (node (ref "TP18") (pin "1") (pinfunction "TP?_1") (pintype "passive"))
      (node (ref "U16") (pin "6") (pinfunction "-INB_6") (pintype "passive"))
      (node (ref "U16") (pin "7") (pinfunction "OUTB_7") (pintype "passive"))
    )
    (net (code "27") (name "/BP_500k-2MHz_OUT2") (class "Default")
      (node (ref "C112") (pin "1") (pinfunction "1_1") (pintype "passive"))
      (node (ref "R140") (pin "2") (pinfunction "2_2") (pintype "passive"))
      (node (ref "TP20") (pin "1") (pinfunction "TP?_1") (pintype "passive"))
      (node (ref "U17") (pin "6") (pinfunction "-INB_6") (pintype "passive"))
      (node (ref "U17") (pin "7") (pinfunction "OUTB_7") (pintype "passive"))
    )
    (net (code "28") (name "/CNTRL_SEL") (class "Default")
      (node (ref "R69") (pin "1") (pinfunction "1_1") (pintype "passive"))
      (node (ref "SW1") (pin "12") (pinfunction "O9_12") (pintype "passive"))
      (node (ref "U8") (pin "1") (pinfunction "S_1") (pintype "passive"))
      (node (ref "U9") (pin "1") (pinfunction "S_1") (pintype "passive"))
    )
    (net (code "29") (name "/CS0") (class "Default")
      (node (ref "TP_CS0") (pin "1") (pinfunction "TP?_1") (pintype "passive"))
      (node (ref "U12") (pin "4") (pinfunction "~{CS}_4") (pintype "passive"))
      (node (ref "U6") (pin "8") (pinfunction "PB0(SS/PCINT0)_8") (pintype "passive"))
    )
    (net (code "30") (name "/CS1") (class "Default")
      (node (ref "TP_CS1") (pin "1") (pinfunction "TP?_1") (pintype "passive"))
      (node (ref "U15") (pin "4") (pinfunction "~{CS}_4") (pintype "passive"))
      (node (ref "U6") (pin "28") (pinfunction "PB4(PCINT4/ADC11)_28") (pintype "passive"))
    )
    (net (code "31") (name "/FILTER_IN1") (class "Default")
      (node (ref "C55") (pin "1") (pinfunction "1_1") (pintype "passive"))
      (node (ref "C73") (pin "2") (pinfunction "2_2") (pintype "passive"))
      (node (ref "C76") (pin "1") (pinfunction "1_1") (pintype "passive"))
      (node (ref "C94") (pin "2") (pinfunction "2_2") (pintype "passive"))
      (node (ref "C97") (pin "1") (pinfunction "1_1") (pintype "passive"))
      (node (ref "R122") (pin "2") (pinfunction "2_2") (pintype "passive"))
      (node (ref "R131") (pin "2") (pinfunction "2_2") (pintype "passive"))
      (node (ref "R72") (pin "1") (pinfunction "1_1") (pintype "passive"))
    )
    (net (code "32") (name "/FILTER_IN2") (class "Default")
      (node (ref "C101") (pin "1") (pinfunction "1_1") (pintype "passive"))
      (node (ref "C57") (pin "1") (pinfunction "1_1") (pintype "passive"))
      (node (ref "C77") (pin "2") (pinfunction "2_2") (pintype "passive"))
      (node (ref "C80") (pin "1") (pinfunction "1_1") (pintype "passive"))
      (node (ref "C98") (pin "2") (pinfunction "2_2") (pintype "passive"))
      (node (ref "R123") (pin "2") (pinfunction "2_2") (pintype "passive"))
      (node (ref "R130") (pin "2") (pinfunction "2_2") (pintype "passive"))
      (node (ref "R74") (pin "1") (pinfunction "1_1") (pintype "passive"))
    )
    (net (code "33") (name "/FILTER_OUT1") (class "Default")
      (node (ref "R128") (pin "2") (pinfunction "2_2") (pintype "passive"))
      (node (ref "TP17") (pin "1") (pinfunction "TP?_1") (pintype "passive"))
      (node (ref "U19") (pin "8") (pinfunction "D_8") (pintype "passive"))
    )
    (net (code "34") (name "/FILTER_OUT2") (class "Default")
      (node (ref "R126") (pin "2") (pinfunction "2_2") (pintype "passive"))
      (node (ref "TP8") (pin "1") (pinfunction "TP?_1") (pintype "passive"))
      (node (ref "U18") (pin "8") (pinfunction "D_8") (pintype "passive"))
    )
    (net (code "35") (name "/F_MCU_SEL0") (class "Default")
      (node (ref "TP_F0") (pin "1") (pinfunction "TP?_1") (pintype "passive"))
      (node (ref "U6") (pin "41") (pinfunction "PF0(ADC0)_41") (pintype "passive"))
      (node (ref "U8") (pin "3") (pinfunction "1I1_3") (pintype "passive"))
    )
    (net (code "36") (name "/F_MCU_SEL1") (class "Default")
      (node (ref "TP_F1") (pin "1") (pinfunction "TP?_1") (pintype "passive"))
      (node (ref "U6") (pin "40") (pinfunction "PF1(ADC1)_40") (pintype "passive"))
      (node (ref "U8") (pin "6") (pinfunction "2I1_6") (pintype "passive"))
    )
    (net (code "37") (name "/F_MCU_SEL2") (class "Default")
      (node (ref "TP_F2") (pin "1") (pinfunction "TP?_1") (pintype "passive"))
      (node (ref "U6") (pin "39") (pinfunction "PF4(ADC4/TCK)_39") (pintype "passive"))
      (node (ref "U8") (pin "10") (pinfunction "3I1_10") (pintype "passive"))
    )
    (net (code "38") (name "/F_MCU_SEL3") (class "Default")
      (node (ref "TP_F3") (pin "1") (pinfunction "TP?_1") (pintype "passive"))
      (node (ref "U6") (pin "38") (pinfunction "PF5(ADC5/TMS)_38") (pintype "passive"))
      (node (ref "U8") (pin "13") (pinfunction "4I1_13") (pintype "passive"))
    )
    (net (code "39") (name "/F_MCU_SEL4") (class "Default")
      (node (ref "TP_F4") (pin "1") (pinfunction "TP?_1") (pintype "passive"))
      (node (ref "U6") (pin "37") (pinfunction "PF6(ADC6/TDO)_37") (pintype "passive"))
      (node (ref "U9") (pin "3") (pinfunction "1I1_3") (pintype "passive"))
    )
    (net (code "40") (name "/F_MCU_SEL5") (class "Default")
      (node (ref "TP_F5") (pin "1") (pinfunction "TP?_1") (pintype "passive"))
      (node (ref "U6") (pin "36") (pinfunction "PF7(ADC7/TDI)_36") (pintype "passive"))
      (node (ref "U9") (pin "6") (pinfunction "2I1_6") (pintype "passive"))
    )
    (net (code "41") (name "/F_MCU_SEL6") (class "Default")
      (node (ref "TP_F6") (pin "1") (pinfunction "TP?_1") (pintype "passive"))
      (node (ref "U6") (pin "1") (pinfunction "PE6(INT.6/AIN0)_1") (pintype "passive"))
      (node (ref "U9") (pin "10") (pinfunction "3I1_10") (pintype "passive"))
    )
    (net (code "42") (name "/F_MCU_SEL7") (class "Default")
      (node (ref "TP_F7") (pin "1") (pinfunction "TP?_1") (pintype "passive"))
      (node (ref "U6") (pin "27") (pinfunction "PD7(T0/OC4~{D}/ADC10)_27") (pintype "passive"))
      (node (ref "U9") (pin "13") (pinfunction "4I1_13") (pintype "passive"))
    )
    (net (code "44") (name "/F_SEL0") (class "Default")
      (node (ref "U4") (pin "1") (pinfunction "A0_1") (pintype "passive"))
      (node (ref "U8") (pin "4") (pinfunction "1Y_4") (pintype "passive"))
    )
    (net (code "45") (name "/F_SEL1") (class "Default")
      (node (ref "U4") (pin "14") (pinfunction "A1_14") (pintype "passive"))
      (node (ref "U8") (pin "7") (pinfunction "2Y_7") (pintype "passive"))
    )
    (net (code "46") (name "/F_SEL2") (class "Default")
      (node (ref "U19") (pin "1") (pinfunction "A0_1") (pintype "passive"))
      (node (ref "U8") (pin "9") (pinfunction "3Y_9") (pintype "passive"))
    )
    (net (code "47") (name "/F_SEL3") (class "Default")
      (node (ref "U19") (pin "16") (pinfunction "A1_16") (pintype "passive"))
      (node (ref "U8") (pin "12") (pinfunction "4Y_12") (pintype "passive"))
    )
    (net (code "48") (name "/F_SEL4") (class "Default")
      (node (ref "U19") (pin "15") (pinfunction "A2_15") (pintype "passive"))
      (node (ref "U9") (pin "4") (pinfunction "1Y_4") (pintype "passive"))
    )
    (net (code "49") (name "/F_SEL5") (class "Default")
      (node (ref "U18") (pin "1") (pinfunction "A0_1") (pintype "passive"))
      (node (ref "U9") (pin "7") (pinfunction "2Y_7") (pintype "passive"))
    )
    (net (code "50") (name "/F_SEL6") (class "Default")
      (node (ref "U18") (pin "16") (pinfunction "A1_16") (pintype "passive"))
      (node (ref "U9") (pin "9") (pinfunction "3Y_9") (pintype "passive"))
    )
    (net (code "51") (name "/F_SEL7") (class "Default")
      (node (ref "U18") (pin "15") (pinfunction "A2_15") (pintype "passive"))
      (node (ref "U9") (pin "12") (pinfunction "4Y_12") (pintype "passive"))
    )
    (net (code "53") (name "/F_SW_SEL0") (class "Default")
      (node (ref "R61") (pin "1") (pinfunction "1_1") (pintype "passive"))
      (node (ref "SW1") (pin "20") (pinfunction "O1_20") (pintype "passive"))
      (node (ref "U8") (pin "2") (pinfunction "1I0_2") (pintype "passive"))
    )
    (net (code "54") (name "/F_SW_SEL1") (class "Default")
      (node (ref "R62") (pin "1") (pinfunction "1_1") (pintype "passive"))
      (node (ref "SW1") (pin "19") (pinfunction "O2_19") (pintype "passive"))
      (node (ref "U8") (pin "5") (pinfunction "2I0_5") (pintype "passive"))
    )
    (net (code "55") (name "/F_SW_SEL2") (class "Default")
      (node (ref "R63") (pin "1") (pinfunction "1_1") (pintype "passive"))
      (node (ref "SW1") (pin "18") (pinfunction "O3_18") (pintype "passive"))
      (node (ref "U8") (pin "11") (pinfunction "3I0_11") (pintype "passive"))
    )
    (net (code "56") (name "/F_SW_SEL3") (class "Default")
      (node (ref "R64") (pin "1") (pinfunction "1_1") (pintype "passive"))
      (node (ref "SW1") (pin "17") (pinfunction "O4_17") (pintype "passive"))
      (node (ref "U8") (pin "14") (pinfunction "4I0_14") (pintype "passive"))
    )
    (net (code "57") (name "/F_SW_SEL4") (class "Default")
      (node (ref "R65") (pin "1") (pinfunction "1_1") (pintype "passive"))
      (node (ref "SW1") (pin "16") (pinfunction "O5_16") (pintype "passive"))
      (node (ref "U9") (pin "2") (pinfunction "1I0_2") (pintype "passive"))
    )
    (net (code "58") (name "/F_SW_SEL5") (class "Default")
      (node (ref "R66") (pin "1") (pinfunction "1_1") (pintype "passive"))
      (node (ref "SW1") (pin "15") (pinfunction "O6_15") (pintype "passive"))
      (node (ref "U9") (pin "5") (pinfunction "2I0_5") (pintype "passive"))
    )
    (net (code "59") (name "/F_SW_SEL6") (class "Default")
      (node (ref "R67") (pin "1") (pinfunction "1_1") (pintype "passive"))
      (node (ref "SW1") (pin "14") (pinfunction "O7_14") (pintype "passive"))
      (node (ref "U9") (pin "11") (pinfunction "3I0_11") (pintype "passive"))
    )
    (net (code "60") (name "/F_SW_SEL7") (class "Default")
      (node (ref "R68") (pin "1") (pinfunction "1_1") (pintype "passive"))
      (node (ref "SW1") (pin "13") (pinfunction "O8_13") (pintype "passive"))
      (node (ref "U9") (pin "14") (pinfunction "4I0_14") (pintype "passive"))
    )
    (net (code "61") (name "/HP_1MHz_OUT1") (class "Default")
      (node (ref "R116") (pin "2") (pinfunction "2_2") (pintype "passive"))
      (node (ref "R143") (pin "2") (pinfunction "2_2") (pintype "passive"))
      (node (ref "TP19") (pin "1") (pinfunction "TP?_1") (pintype "passive"))
      (node (ref "U16") (pin "10") (pinfunction "OUTC_10") (pintype "passive"))
      (node (ref "U16") (pin "11") (pinfunction "-INC_11") (pintype "passive"))
    )
    (net (code "62") (name "/HP_1MHz_OUT2") (class "Default")
      (node (ref "R117") (pin "2") (pinfunction "2_2") (pintype "passive"))
      (node (ref "R142") (pin "2") (pinfunction "2_2") (pintype "passive"))
      (node (ref "TP21") (pin "1") (pinfunction "TP?_1") (pintype "passive"))
      (node (ref "U17") (pin "10") (pinfunction "OUTC_10") (pintype "passive"))
      (node (ref "U17") (pin "11") (pinfunction "-INC_11") (pintype "passive"))
    )
    (net (code "63") (name "/L") (class "Default")
      (node (ref "F1") (pin "2") (pinfunction "2_2") (pintype "passive"))
      (node (ref "F2") (pin "1") (pinfunction "1_1") (pintype "passive"))
      (node (ref "X1") (pin "6") (pinfunction "Pri-_6") (pintype "passive"))
    )
    (net (code "64") (name "/LP_1k_OUT1") (class "Default")
      (node (ref "C64") (pin "1") (pinfunction "1_1") (pintype "passive"))
      (node (ref "R133") (pin "2") (pinfunction "2_2") (pintype "passive"))
      (node (ref "TP9") (pin "1") (pinfunction "TP?_1") (pintype "passive"))
      (node (ref "U10") (pin "6") (pinfunction "-INB_6") (pintype "passive"))
      (node (ref "U10") (pin "7") (pinfunction "OUTB_7") (pintype "passive"))
    )
    (net (code "65") (name "/LP_1k_OUT2") (class "Default")
      (node (ref "C66") (pin "1") (pinfunction "1_1") (pintype "passive"))
      (node (ref "R132") (pin "2") (pinfunction "2_2") (pintype "passive"))
      (node (ref "TP11") (pin "1") (pinfunction "TP?_1") (pintype "passive"))
      (node (ref "U11") (pin "6") (pinfunction "-INB_6") (pintype "passive"))
      (node (ref "U11") (pin "7") (pinfunction "OUTB_7") (pintype "passive"))
    )
    (net (code "66") (name "/MISO") (class "Default")
      (node (ref "J1") (pin "1") (pinfunction "MISO_1") (pintype "passive"))
      (node (ref "TP_MISO") (pin "1") (pinfunction "TP?_1") (pintype "passive"))
      (node (ref "U6") (pin "11") (pinfunction "PB3(PDO/PCINT3/MISO)_11") (pintype "passive"))
    )
    (net (code "67") (name "/MOSI") (class "Default")
      (node (ref "J1") (pin "4") (pinfunction "MOSI_4") (pintype "passive"))
      (node (ref "TP_MOSI") (pin "1") (pinfunction "TP?_1") (pintype "passive"))
      (node (ref "U12") (pin "5") (pinfunction "SDI_5") (pintype "passive"))
      (node (ref "U15") (pin "5") (pinfunction "SDI_5") (pintype "passive"))
      (node (ref "U6") (pin "10") (pinfunction "PB2(PDI/PCINT2/MOSI)_10") (pintype "passive"))
    )
    (net (code "70") (name "/N") (class "Default")
      (node (ref "C23") (pin "1") (pinfunction "1_1") (pintype "passive"))
      (node (ref "CON_N1") (pin "1") (pintype "passive"))
      (node (ref "X1") (pin "1") (pinfunction "Pri+_1") (pintype "passive"))
    )
    (net (code "71") (name "/NOTCH_VOUT1") (class "Default")
      (node (ref "R12") (pin "2") (pinfunction "2_2") (pintype "passive"))
      (node (ref "R121") (pin "1") (pinfunction "1_1") (pintype "passive"))
      (node (ref "TP2") (pin "1") (pinfunction "TP?_1") (pintype "passive"))
      (node (ref "U3") (pin "15") (pinfunction "-IND_15") (pintype "passive"))
      (node (ref "U3") (pin "16") (pinfunction "OUTD_16") (pintype "passive"))
    )
    (net (code "72") (name "/NOTCH_VOUT2") (class "Default")
      (node (ref "R125") (pin "2") (pinfunction "2_2") (pintype "passive"))
      (node (ref "R46") (pin "2") (pinfunction "2_2") (pintype "passive"))
      (node (ref "TP6") (pin "1") (pinfunction "TP?_1") (pintype "passive"))
      (node (ref "U7") (pin "15") (pinfunction "-IND_15") (pintype "passive"))
      (node (ref "U7") (pin "16") (pinfunction "OUTD_16") (pintype "passive"))
    )
    (net (code "73") (name "/PB5") (class "Default")
      (node (ref "TP28") (pin "1") (pinfunction "TP?_1") (pintype "passive"))
      (node (ref "U6") (pin "29") (pinfunction "PB5(PCINT5/OC1A/~{OC4B}/ADC12)_29") (pintype "passive"))
    )
    (net (code "74") (name "/PB6") (class "Default")
      (node (ref "TP29") (pin "1") (pinfunction "TP?_1") (pintype "passive"))
      (node (ref "U6") (pin "30") (pinfunction "PB6(PCINT6/OC1B/OC4B/ADC13)_30") (pintype "passive"))
    )
    (net (code "75") (name "/PB7") (class "Default")
      (node (ref "TP30") (pin "1") (pinfunction "TP?_1") (pintype "passive"))
      (node (ref "U6") (pin "12") (pinfunction "PB7(PCINT7/OC0A/OC1C/~{RTS})_12") (pintype "passive"))
    )
    (net (code "76") (name "/PC6") (class "Default")
      (node (ref "TP31") (pin "1") (pinfunction "TP?_1") (pintype "passive"))
      (node (ref "U6") (pin "31") (pinfunction "PC6(OC3A/~{OC4A})_31") (pintype "passive"))
    )
    (net (code "77") (name "/PC7") (class "Default")
      (node (ref "TP32") (pin "1") (pinfunction "TP?_1") (pintype "passive"))
      (node (ref "U6") (pin "32") (pinfunction "PC7(ICP3/CLK0/OC4A)_32") (pintype "passive"))
    )
    (net (code "78") (name "/PD2") (class "Default")
      (node (ref "TP33") (pin "1") (pinfunction "TP?_1") (pintype "passive"))
      (node (ref "U6") (pin "20") (pinfunction "PD2(RXD1/INT2)_20") (pintype "passive"))
    )
    (net (code "79") (name "/PD5") (class "Default")
      (node (ref "TP34") (pin "1") (pinfunction "TP?_1") (pintype "passive"))
      (node (ref "U6") (pin "22") (pinfunction "PD5(XCK1/~{CTS})_22") (pintype "passive"))
    )
    (net (code "80") (name "/PD6") (class "Default")
      (node (ref "TP35") (pin "1") (pinfunction "TP?_1") (pintype "passive"))
      (node (ref "U6") (pin "26") (pinfunction "PD6(T1/~{OC4D}/ADC9)_26") (pintype "passive"))
    )
    (net (code "81") (name "/PRE_AMP_OUT1") (class "Default")
      (node (ref "R1") (pin "1") (pinfunction "1_1") (pintype "passive"))
      (node (ref "R120") (pin "2") (pinfunction "2_2") (pintype "passive"))
      (node (ref "R9") (pin "1") (pinfunction "1_1") (pintype "passive"))
      (node (ref "TP1") (pin "1") (pinfunction "TP?_1") (pintype "passive"))
      (node (ref "U2") (pin "1") (pinfunction "OUT_1") (pintype "passive"))
      (node (ref "U4") (pin "4") (pinfunction "S1A_4") (pintype "passive"))
    )
    (net (code "82") (name "/PRE_AMP_OUT2") (class "Default")
      (node (ref "R124") (pin "2") (pinfunction "2_2") (pintype "passive"))
      (node (ref "R37") (pin "1") (pinfunction "1_1") (pintype "passive"))
      (node (ref "R51") (pin "1") (pinfunction "1_1") (pintype "passive"))
      (node (ref "TP4") (pin "1") (pinfunction "TP?_1") (pintype "passive"))
      (node (ref "U4") (pin "11") (pinfunction "S2A_11") (pintype "passive"))
      (node (ref "U5") (pin "1") (pinfunction "OUT_1") (pintype "passive"))
    )
    (net (code "83") (name "/Reset") (class "Default")
      (node (ref "C40") (pin "1") (pinfunction "1_1") (pintype "passive"))
      (node (ref "J1") (pin "5") (pinfunction "RST_5") (pintype "passive"))
      (node (ref "R53") (pin "1") (pinfunction "1_1") (pintype "passive"))
      (node (ref "S1") (pin "1") (pinfunction "1_1") (pintype "passive"))
      (node (ref "S1") (pin "2") (pinfunction "2_2") (pintype "passive"))
      (node (ref "U6") (pin "13") (pinfunction "~{RESET}_13") (pintype "passive"))
    )
    (net (code "84") (name "/SCK") (class "Default")
      (node (ref "J1") (pin "3") (pinfunction "SCK_3") (pintype "passive"))
      (node (ref "TP_SCK") (pin "1") (pinfunction "TP?_1") (pintype "passive"))
      (node (ref "U12") (pin "3") (pinfunction "SCK_3") (pintype "passive"))
      (node (ref "U15") (pin "3") (pinfunction "SCK_3") (pintype "passive"))
      (node (ref "U6") (pin "9") (pinfunction "PB1(PCINT1/SCLK)_9") (pintype "passive"))
    )
    (net (code "85") (name "/SCL") (class "Default")
      (node (ref "TPSCL") (pin "1") (pinfunction "TP?_1") (pintype "passive"))
      (node (ref "U6") (pin "18") (pinfunction "PD0(OC0B/SCL/INT0)_18") (pintype "passive"))
    )
    (net (code "86") (name "/SDA") (class "Default")
      (node (ref "TPSDA") (pin "1") (pinfunction "TP?_1") (pintype "passive"))
      (node (ref "U6") (pin "19") (pinfunction "PD1(SDA/INT1)_19") (pintype "passive"))
    )
    (net (code "87") (name "/STAT_LED") (class "Default")
      (node (ref "D_STAT1") (pin "1") (pinfunction "A_1") (pintype "passive"))
      (node (ref "U6") (pin "21") (pinfunction "PD3(TXD1/INT3)_21") (pintype "passive"))
    )
    (net (code "88") (name "/VOLT_SIG") (class "Default")
      (node (ref "R27") (pin "2") (pinfunction "2_2") (pintype "passive"))
      (node (ref "R29") (pin "1") (pinfunction "1_1") (pintype "passive"))
      (node (ref "R31") (pin "2") (pinfunction "2_2") (pintype "passive"))
      (node (ref "R32") (pin "2") (pinfunction "2_2") (pintype "passive"))
      (node (ref "TP3") (pin "1") (pinfunction "TP?_1") (pintype "passive"))
      (node (ref "U2") (pin "3") (pinfunction "IN+_3") (pintype "passive"))
    )
    (net (code "89") (name "GND") (class "Default")
      (node (ref "C1") (pin "2") (pinfunction "2_2") (pintype "passive"))
      (node (ref "C102") (pin "1") (pinfunction "1_1") (pintype "passive"))
      (node (ref "C103") (pin "1") (pinfunction "1_1") (pintype "passive"))
      (node (ref "C104") (pin "1") (pinfunction "1_1") (pintype "passive"))
      (node (ref "C105") (pin "1") (pinfunction "1_1") (pintype "passive"))
      (node (ref "C106") (pin "1") (pinfunction "1_1") (pintype "passive"))
      (node (ref "C113") (pin "1") (pinfunction "1_1") (pintype "passive"))
      (node (ref "C114") (pin "1") (pinfunction "1_1") (pintype "passive"))
      (node (ref "C115") (pin "1") (pinfunction "1_1") (pintype "passive"))
      (node (ref "C116") (pin "2") (pinfunction "2_2") (pintype "passive"))
      (node (ref "C117") (pin "1") (pinfunction "1_1") (pintype "passive"))
      (node (ref "C118") (pin "2") (pinfunction "2_2") (pintype "passive"))
      (node (ref "C13") (pin "1") (pinfunction "1_1") (pintype "passive"))
      (node (ref "C16") (pin "2") (pinfunction "2_2") (pintype "passive"))
      (node (ref "C17") (pin "2") (pinfunction "2_2") (pintype "passive"))
      (node (ref "C18") (pin "1") (pinfunction "1_1") (pintype "passive"))
      (node (ref "C19") (pin "1") (pinfunction "1_1") (pintype "passive"))
      (node (ref "C2") (pin "2") (pinfunction "2_2") (pintype "passive"))
      (node (ref "C23") (pin "2") (pinfunction "2_2") (pintype "passive"))
      (node (ref "C24") (pin "1") (pinfunction "1_1") (pintype "passive"))
      (node (ref "C25") (pin "1") (pinfunction "1_1") (pintype "passive"))
      (node (ref "C26") (pin "1") (pinfunction "1_1") (pintype "passive"))
      (node (ref "C27") (pin "2") (pinfunction "2_2") (pintype "passive"))
      (node (ref "C28") (pin "2") (pinfunction "2_2") (pintype "passive"))
      (node (ref "C29") (pin "2") (pinfunction "2_2") (pintype "passive"))
      (node (ref "C3") (pin "2") (pinfunction "2_2") (pintype "passive"))
      (node (ref "C30") (pin "2") (pinfunction "2_2") (pintype "passive"))
      (node (ref "C33") (pin "2") (pinfunction "2_2") (pintype "passive"))
      (node (ref "C34") (pin "2") (pinfunction "2_2") (pintype "passive"))
      (node (ref "C35") (pin "2") (pinfunction "2_2") (pintype "passive"))
      (node (ref "C36") (pin "2") (pinfunction "2_2") (pintype "passive"))
      (node (ref "C39") (pin "2") (pinfunction "2_2") (pintype "passive"))
      (node (ref "C4") (pin "2") (pinfunction "2_2") (pintype "passive"))
      (node (ref "C40") (pin "2") (pinfunction "2_2") (pintype "passive"))
      (node (ref "C41") (pin "2") (pinfunction "2_2") (pintype "passive"))
      (node (ref "C44") (pin "2") (pinfunction "2_2") (pintype "passive"))
      (node (ref "C45") (pin "2") (pinfunction "2_2") (pintype "passive"))
      (node (ref "C48") (pin "2") (pinfunction "2_2") (pintype "passive"))
      (node (ref "C49") (pin "1") (pinfunction "1_1") (pintype "passive"))
      (node (ref "C5") (pin "2") (pinfunction "2_2") (pintype "passive"))
      (node (ref "C50") (pin "1") (pinfunction "1_1") (pintype "passive"))
      (node (ref "C51") (pin "1") (pinfunction "1_1") (pintype "passive"))
      (node (ref "C58") (pin "1") (pinfunction "1_1") (pintype "passive"))
      (node (ref "C59") (pin "1") (pinfunction "1_1") (pintype "passive"))
      (node (ref "C6") (pin "2") (pinfunction "2_2") (pintype "passive"))
      (node (ref "C60") (pin "1") (pinfunction "1_1") (pintype "passive"))
      (node (ref "C61") (pin "1") (pinfunction "1_1") (pintype "passive"))
      (node (ref "C62") (pin "1") (pinfunction "1_1") (pintype "passive"))
      (node (ref "C63") (pin "1") (pinfunction "1_1") (pintype "passive"))
      (node (ref "C68") (pin "1") (pinfunction "1_1") (pintype "passive"))
      (node (ref "C69") (pin "1") (pinfunction "1_1") (pintype "passive"))
      (node (ref "C7") (pin "2") (pinfunction "2_2") (pintype "passive"))
      (node (ref "C70") (pin "1") (pinfunction "1_1") (pintype "passive"))
      (node (ref "C71") (pin "1") (pinfunction "1_1") (pintype "passive"))
      (node (ref "C72") (pin "1") (pinfunction "1_1") (pintype "passive"))
      (node (ref "C8") (pin "2") (pinfunction "2_2") (pintype "passive"))
      (node (ref "C81") (pin "1") (pinfunction "1_1") (pintype "passive"))
      (node (ref "C82") (pin "1") (pinfunction "1_1") (pintype "passive"))
      (node (ref "C83") (pin "1") (pinfunction "1_1") (pintype "passive"))
      (node (ref "C84") (pin "1") (pinfunction "1_1") (pintype "passive"))
      (node (ref "C85") (pin "1") (pinfunction "1_1") (pintype "passive"))
      (node (ref "C88") (pin "1") (pinfunction "1_1") (pintype "passive"))
      (node (ref "C91") (pin "1") (pinfunction "1_1") (pintype "passive"))
      (node (ref "C92") (pin "1") (pinfunction "1_1") (pintype "passive"))
      (node (ref "C93") (pin "1") (pinfunction "1_1") (pintype "passive"))
      (node (ref "CN1") (pin "5") (pinfunction "5_5") (pintype "passive"))
      (node (ref "CON1") (pin "2") (pinfunction "2_2") (pintype "passive"))
      (node (ref "CON2") (pin "2") (pinfunction "2_2") (pintype "passive"))
      (node (ref "CON3") (pin "2") (pinfunction "2_2") (pintype "passive"))
      (node (ref "CON6") (pin "2") (pinfunction "2_2") (pintype "passive"))
      (node (ref "CON7") (pin "2") (pinfunction "2_2") (pintype "passive"))
      (node (ref "CON8") (pin "2") (pinfunction "2_2") (pintype "passive"))
      (node (ref "CON9") (pin "2") (pinfunction "2_2") (pintype "passive"))
      (node (ref "D1") (pin "2") (pinfunction "K_2") (pintype "passive"))
      (node (ref "D2") (pin "2") (pinfunction "K_2") (pintype "passive"))
      (node (ref "J1") (pin "6") (pinfunction "GND_6") (pintype "passive"))
      (node (ref "R10") (pin "2") (pinfunction "2_2") (pintype "passive"))
      (node (ref "R108") (pin "1") (pinfunction "1_1") (pintype "passive"))
      (node (ref "R109") (pin "1") (pinfunction "1_1") (pintype "passive"))
      (node (ref "R11") (pin "1") (pinfunction "1_1") (pintype "passive"))
      (node (ref "R110") (pin "1") (pinfunction "1_1") (pintype "passive"))
      (node (ref "R111") (pin "1") (pinfunction "1_1") (pintype "passive"))
      (node (ref "R118") (pin "1") (pinfunction "1_1") (pintype "passive"))
      (node (ref "R119") (pin "1") (pinfunction "1_1") (pintype "passive"))
      (node (ref "R127") (pin "2") (pinfunction "2_2") (pintype "passive"))
      (node (ref "R129") (pin "2") (pinfunction "2_2") (pintype "passive"))
      (node (ref "R15") (pin "2") (pinfunction "2_2") (pintype "passive"))
      (node (ref "R18") (pin "2") (pinfunction "2_2") (pintype "passive"))
      (node (ref "R2") (pin "1") (pinfunction "1_1") (pintype "passive"))
      (node (ref "R21") (pin "1") (pinfunction "1_1") (pintype "passive"))
      (node (ref "R24") (pin "2") (pinfunction "2_2") (pintype "passive"))
      (node (ref "R30") (pin "1") (pinfunction "1_1") (pintype "passive"))
      (node (ref "R31") (pin "1") (pinfunction "1_1") (pintype "passive"))
      (node (ref "R32") (pin "1") (pinfunction "1_1") (pintype "passive"))
      (node (ref "R33") (pin "1") (pinfunction "1_1") (pintype "passive"))
      (node (ref "R35") (pin "2") (pinfunction "2_2") (pintype "passive"))
      (node (ref "R38") (pin "1") (pinfunction "1_1") (pintype "passive"))
      (node (ref "R39") (pin "1") (pinfunction "1_1") (pintype "passive"))
      (node (ref "R40") (pin "1") (pinfunction "1_1") (pintype "passive"))
      (node (ref "R45") (pin "1") (pinfunction "1_1") (pintype "passive"))
      (node (ref "R52") (pin "2") (pinfunction "2_2") (pintype "passive"))
      (node (ref "R56") (pin "2") (pinfunction "2_2") (pintype "passive"))
      (node (ref "R6") (pin "1") (pinfunction "1_1") (pintype "passive"))
      (node (ref "R60") (pin "2") (pinfunction "2_2") (pintype "passive"))
      (node (ref "R76") (pin "1") (pinfunction "1_1") (pintype "passive"))
      (node (ref "R77") (pin "1") (pinfunction "1_1") (pintype "passive"))
      (node (ref "R8") (pin "1") (pinfunction "1_1") (pintype "passive"))
      (node (ref "R91") (pin "1") (pinfunction "1_1") (pintype "passive"))
      (node (ref "R92") (pin "1") (pinfunction "1_1") (pintype "passive"))
      (node (ref "R93") (pin "1") (pinfunction "1_1") (pintype "passive"))
      (node (ref "R94") (pin "1") (pinfunction "1_1") (pintype "passive"))
      (node (ref "S1") (pin "3") (pinfunction "3_3") (pintype "passive"))
      (node (ref "S1") (pin "4") (pinfunction "4_4") (pintype "passive"))
      (node (ref "S2") (pin "1") (pinfunction "1_1") (pintype "passive"))
      (node (ref "S2") (pin "2") (pinfunction "2_2") (pintype "passive"))
      (node (ref "SW1") (pin "1") (pinfunction "I1_1") (pintype "passive"))
      (node (ref "SW1") (pin "2") (pinfunction "I2_2") (pintype "passive"))
      (node (ref "SW1") (pin "3") (pinfunction "I3_3") (pintype "passive"))
      (node (ref "SW1") (pin "4") (pinfunction "I4_4") (pintype "passive"))
      (node (ref "SW1") (pin "5") (pinfunction "I5_5") (pintype "passive"))
      (node (ref "SW1") (pin "6") (pinfunction "I6_6") (pintype "passive"))
      (node (ref "SW1") (pin "7") (pinfunction "I7_7") (pintype "passive"))
      (node (ref "SW1") (pin "8") (pinfunction "I8_8") (pintype "passive"))
      (node (ref "SW1") (pin "9") (pinfunction "I9_9") (pintype "passive"))
      (node (ref "TP_GND") (pin "1") (pinfunction "TP?_1") (pintype "passive"))
      (node (ref "TP_GND2") (pin "1") (pinfunction "TP?_1") (pintype "passive"))
      (node (ref "U12") (pin "10") (pinfunction "GRT_10") (pintype "passive"))
      (node (ref "U12") (pin "11") (pinfunction "GRT_11") (pintype "passive"))
      (node (ref "U12") (pin "2") (pinfunction "DGND_2") (pintype "passive"))
      (node (ref "U15") (pin "10") (pinfunction "GRT_10") (pintype "passive"))
      (node (ref "U15") (pin "11") (pinfunction "GRT_11") (pintype "passive"))
      (node (ref "U15") (pin "2") (pinfunction "DGND_2") (pintype "passive"))
      (node (ref "U18") (pin "14") (pinfunction "GND_14") (pintype "passive"))
      (node (ref "U18") (pin "2") (pinfunction "EN_2") (pintype "passive"))
      (node (ref "U19") (pin "14") (pinfunction "GND_14") (pintype "passive"))
      (node (ref "U19") (pin "2") (pinfunction "EN_2") (pintype "passive"))
      (node (ref "U4") (pin "13") (pinfunction "GND_13") (pintype "passive"))
      (node (ref "U6") (pin "15") (pinfunction "GND_15") (pintype "passive"))
      (node (ref "U6") (pin "23") (pinfunction "GND_23") (pintype "passive"))
      (node (ref "U6") (pin "35") (pinfunction "GND_35") (pintype "passive"))
      (node (ref "U6") (pin "43") (pinfunction "GND_43") (pintype "passive"))
      (node (ref "U6") (pin "5") (pinfunction "UGND_5") (pintype "passive"))
      (node (ref "U8") (pin "15") (pinfunction "E_15") (pintype "passive"))
      (node (ref "U8") (pin "8") (pinfunction "GND_8") (pintype "passive"))
      (node (ref "U9") (pin "15") (pinfunction "E_15") (pintype "passive"))
      (node (ref "U9") (pin "8") (pinfunction "GND_8") (pintype "passive"))
      (node (ref "X1") (pin "10") (pinfunction "Sec+_10") (pintype "passive"))
      (node (ref "X1") (pin "9") (pinfunction "Sec-_9") (pintype "passive"))
    )
    (net (code "90") (name "Net-(C10-Pad2)") (class "Default")
      (node (ref "C10") (pin "2") (pinfunction "2_2") (pintype "passive"))
      (node (ref "C9") (pin "2") (pinfunction "2_2") (pintype "passive"))
      (node (ref "R16") (pin "2") (pinfunction "2_2") (pintype "passive"))
      (node (ref "R17") (pin "1") (pinfunction "1_1") (pintype "passive"))
    )
    (net (code "91") (name "Net-(C11-Pad2)") (class "Default")
      (node (ref "C11") (pin "2") (pinfunction "2_2") (pintype "passive"))
      (node (ref "C12") (pin "2") (pinfunction "2_2") (pintype "passive"))
      (node (ref "R19") (pin "1") (pinfunction "1_1") (pintype "passive"))
      (node (ref "R20") (pin "2") (pinfunction "2_2") (pintype "passive"))
    )
    (net (code "92") (name "Net-(C14-Pad1)") (class "Default")
      (node (ref "C14") (pin "1") (pinfunction "1_1") (pintype "passive"))
      (node (ref "C15") (pin "2") (pinfunction "2_2") (pintype "passive"))
      (node (ref "R22") (pin "2") (pinfunction "2_2") (pintype "passive"))
      (node (ref "R23") (pin "2") (pinfunction "2_2") (pintype "passive"))
    )
    (net (code "93") (name "Net-(C14-Pad2)") (class "Default")
      (node (ref "C14") (pin "2") (pinfunction "2_2") (pintype "passive"))
      (node (ref "R120") (pin "1") (pinfunction "1_1") (pintype "passive"))
      (node (ref "R16") (pin "1") (pinfunction "1_1") (pintype "passive"))
    )
    (net (code "94") (name "Net-(C20-Pad2)") (class "Default")
      (node (ref "C20") (pin "2") (pinfunction "2_2") (pintype "passive"))
      (node (ref "C21") (pin "1") (pinfunction "1_1") (pintype "passive"))
      (node (ref "R25") (pin "2") (pinfunction "2_2") (pintype "passive"))
      (node (ref "R26") (pin "2") (pinfunction "2_2") (pintype "passive"))
    )
    (net (code "95") (name "Net-(C22-Pad1)") (class "Default")
      (node (ref "C22") (pin "1") (pinfunction "1_1") (pintype "passive"))
      (node (ref "F2") (pin "2") (pinfunction "2_2") (pintype "passive"))
    )
    (net (code "96") (name "Net-(C22-Pad2)") (class "Default")
      (node (ref "C22") (pin "2") (pinfunction "2_2") (pintype "passive"))
      (node (ref "R27") (pin "1") (pinfunction "1_1") (pintype "passive"))
      (node (ref "R29") (pin "2") (pinfunction "2_2") (pintype "passive"))
      (node (ref "R30") (pin "2") (pinfunction "2_2") (pintype "passive"))
      (node (ref "R33") (pin "2") (pinfunction "2_2") (pintype "passive"))
    )
    (net (code "97") (name "Net-(C31-Pad2)") (class "Default")
      (node (ref "C31") (pin "2") (pinfunction "2_2") (pintype "passive"))
      (node (ref "C32") (pin "2") (pinfunction "2_2") (pintype "passive"))
      (node (ref "R41") (pin "2") (pinfunction "2_2") (pintype "passive"))
      (node (ref "R42") (pin "1") (pinfunction "1_1") (pintype "passive"))
    )
    (net (code "98") (name "Net-(C37-Pad1)") (class "Default")
      (node (ref "C37") (pin "1") (pinfunction "1_1") (pintype "passive"))
      (node (ref "C38") (pin "2") (pinfunction "2_2") (pintype "passive"))
      (node (ref "R49") (pin "2") (pinfunction "2_2") (pintype "passive"))
      (node (ref "R50") (pin "2") (pinfunction "2_2") (pintype "passive"))
    )
    (net (code "99") (name "Net-(C37-Pad2)") (class "Default")
      (node (ref "C37") (pin "2") (pinfunction "2_2") (pintype "passive"))
      (node (ref "R124") (pin "1") (pinfunction "1_1") (pintype "passive"))
      (node (ref "R41") (pin "1") (pinfunction "1_1") (pintype "passive"))
    )
    (net (code "100") (name "Net-(C42-Pad2)") (class "Default")
      (node (ref "C42") (pin "2") (pinfunction "2_2") (pintype "passive"))
      (node (ref "C43") (pin "2") (pinfunction "2_2") (pintype "passive"))
      (node (ref "R54") (pin "1") (pinfunction "1_1") (pintype "passive"))
      (node (ref "R55") (pin "2") (pinfunction "2_2") (pintype "passive"))
    )
    (net (code "101") (name "Net-(C46-Pad2)") (class "Default")
      (node (ref "C46") (pin "2") (pinfunction "2_2") (pintype "passive"))
      (node (ref "C47") (pin "1") (pinfunction "1_1") (pintype "passive"))
      (node (ref "R58") (pin "2") (pinfunction "2_2") (pintype "passive"))
      (node (ref "R59") (pin "2") (pinfunction "2_2") (pintype "passive"))
    )
    (net (code "102") (name "Net-(C52-Pad1)") (class "Default")
      (node (ref "C52") (pin "1") (pinfunction "1_1") (pintype "passive"))
      (node (ref "R72") (pin "2") (pinfunction "2_2") (pintype "passive"))
      (node (ref "R73") (pin "1") (pinfunction "1_1") (pintype "passive"))
    )
    (net (code "103") (name "Net-(C53-Pad1)") (class "Default")
      (node (ref "C53") (pin "1") (pinfunction "1_1") (pintype "passive"))
      (node (ref "R74") (pin "2") (pinfunction "2_2") (pintype "passive"))
      (node (ref "R75") (pin "1") (pinfunction "1_1") (pintype "passive"))
    )
    (net (code "104") (name "Net-(C54-Pad1)") (class "Default")
      (node (ref "C54") (pin "1") (pinfunction "1_1") (pintype "passive"))
      (node (ref "C55") (pin "2") (pinfunction "2_2") (pintype "passive"))
      (node (ref "R70") (pin "1") (pinfunction "1_1") (pintype "passive"))
    )
    (net (code "105") (name "Net-(C56-Pad1)") (class "Default")
      (node (ref "C56") (pin "1") (pinfunction "1_1") (pintype "passive"))
      (node (ref "C57") (pin "2") (pinfunction "2_2") (pintype "passive"))
      (node (ref "R71") (pin "1") (pinfunction "1_1") (pintype "passive"))
    )
    (net (code "106") (name "Net-(C64-Pad2)") (class "Default")
      (node (ref "C64") (pin "2") (pinfunction "2_2") (pintype "passive"))
      (node (ref "R78") (pin "2") (pinfunction "2_2") (pintype "passive"))
      (node (ref "R79") (pin "1") (pinfunction "1_1") (pintype "passive"))
    )
    (net (code "107") (name "Net-(C65-Pad2)") (class "Default")
      (node (ref "C65") (pin "2") (pinfunction "2_2") (pintype "passive"))
      (node (ref "R83") (pin "2") (pinfunction "2_2") (pintype "passive"))
      (node (ref "R84") (pin "1") (pinfunction "1_1") (pintype "passive"))
    )
    (net (code "108") (name "Net-(C66-Pad2)") (class "Default")
      (node (ref "C66") (pin "2") (pinfunction "2_2") (pintype "passive"))
      (node (ref "R81") (pin "2") (pinfunction "2_2") (pintype "passive"))
      (node (ref "R82") (pin "1") (pinfunction "1_1") (pintype "passive"))
    )
    (net (code "109") (name "Net-(C67-Pad2)") (class "Default")
      (node (ref "C67") (pin "2") (pinfunction "2_2") (pintype "passive"))
      (node (ref "R85") (pin "2") (pinfunction "2_2") (pintype "passive"))
      (node (ref "R86") (pin "1") (pinfunction "1_1") (pintype "passive"))
    )
    (net (code "110") (name "Net-(C73-Pad1)") (class "Default")
      (node (ref "C73") (pin "1") (pinfunction "1_1") (pintype "passive"))
      (node (ref "C74") (pin "2") (pinfunction "2_2") (pintype "passive"))
      (node (ref "R89") (pin "1") (pinfunction "1_1") (pintype "passive"))
    )
    (net (code "111") (name "Net-(C75-Pad1)") (class "Default")
      (node (ref "C75") (pin "1") (pinfunction "1_1") (pintype "passive"))
      (node (ref "C76") (pin "2") (pinfunction "2_2") (pintype "passive"))
      (node (ref "R87") (pin "1") (pinfunction "1_1") (pintype "passive"))
    )
    (net (code "112") (name "Net-(C77-Pad1)") (class "Default")
      (node (ref "C77") (pin "1") (pinfunction "1_1") (pintype "passive"))
      (node (ref "C78") (pin "2") (pinfunction "2_2") (pintype "passive"))
      (node (ref "R90") (pin "1") (pinfunction "1_1") (pintype "passive"))
    )
    (net (code "113") (name "Net-(C79-Pad1)") (class "Default")
      (node (ref "C79") (pin "1") (pinfunction "1_1") (pintype "passive"))
      (node (ref "C80") (pin "2") (pinfunction "2_2") (pintype "passive"))
      (node (ref "R88") (pin "1") (pinfunction "1_1") (pintype "passive"))
    )
    (net (code "114") (name "Net-(C86-Pad2)") (class "Default")
      (node (ref "C86") (pin "2") (pinfunction "2_2") (pintype "passive"))
      (node (ref "R97") (pin "2") (pinfunction "2_2") (pintype "passive"))
      (node (ref "R98") (pin "1") (pinfunction "1_1") (pintype "passive"))
    )
    (net (code "115") (name "Net-(C87-Pad2)") (class "Default")
      (node (ref "C87") (pin "2") (pinfunction "2_2") (pintype "passive"))
      (node (ref "R101") (pin "2") (pinfunction "2_2") (pintype "passive"))
      (node (ref "R102") (pin "1") (pinfunction "1_1") (pintype "passive"))
    )
    (net (code "116") (name "Net-(C89-Pad2)") (class "Default")
      (node (ref "C89") (pin "2") (pinfunction "2_2") (pintype "passive"))
      (node (ref "R95") (pin "2") (pinfunction "2_2") (pintype "passive"))
      (node (ref "R96") (pin "1") (pinfunction "1_1") (pintype "passive"))
    )
    (net (code "117") (name "Net-(C90-Pad2)") (class "Default")
      (node (ref "C90") (pin "2") (pinfunction "2_2") (pintype "passive"))
      (node (ref "R100") (pin "1") (pinfunction "1_1") (pintype "passive"))
      (node (ref "R99") (pin "2") (pinfunction "2_2") (pintype "passive"))
    )
    (net (code "118") (name "Net-(C94-Pad1)") (class "Default")
      (node (ref "C94") (pin "1") (pinfunction "1_1") (pintype "passive"))
      (node (ref "C95") (pin "2") (pinfunction "2_2") (pintype "passive"))
      (node (ref "R105") (pin "1") (pinfunction "1_1") (pintype "passive"))
    )
    (net (code "119") (name "Net-(C96-Pad1)") (class "Default")
      (node (ref "C96") (pin "1") (pinfunction "1_1") (pintype "passive"))
      (node (ref "C97") (pin "2") (pinfunction "2_2") (pintype "passive"))
      (node (ref "R104") (pin "1") (pinfunction "1_1") (pintype "passive"))
    )
    (net (code "120") (name "Net-(C98-Pad1)") (class "Default")
      (node (ref "C98") (pin "1") (pinfunction "1_1") (pintype "passive"))
      (node (ref "C99") (pin "2") (pinfunction "2_2") (pintype "passive"))
      (node (ref "R107") (pin "1") (pinfunction "1_1") (pintype "passive"))
    )
    (net (code "121") (name "Net-(C100-Pad1)") (class "Default")
      (node (ref "C100") (pin "1") (pinfunction "1_1") (pintype "passive"))
      (node (ref "C101") (pin "2") (pinfunction "2_2") (pintype "passive"))
      (node (ref "R106") (pin "1") (pinfunction "1_1") (pintype "passive"))
    )
    (net (code "122") (name "Net-(C107-Pad1)") (class "Default")
      (node (ref "C107") (pin "1") (pinfunction "1_1") (pintype "passive"))
      (node (ref "C108") (pin "2") (pinfunction "2_2") (pintype "passive"))
      (node (ref "R116") (pin "1") (pinfunction "1_1") (pintype "passive"))
    )
    (net (code "123") (name "Net-(C109-Pad1)") (class "Default")
      (node (ref "C109") (pin "1") (pinfunction "1_1") (pintype "passive"))
      (node (ref "C110") (pin "2") (pinfunction "2_2") (pintype "passive"))
      (node (ref "R117") (pin "1") (pinfunction "1_1") (pintype "passive"))
    )
    (net (code "124") (name "Net-(C111-Pad2)") (class "Default")
      (node (ref "C111") (pin "2") (pinfunction "2_2") (pintype "passive"))
      (node (ref "R112") (pin "2") (pinfunction "2_2") (pintype "passive"))
      (node (ref "R113") (pin "1") (pinfunction "1_1") (pintype "passive"))
    )
    (net (code "125") (name "Net-(C112-Pad2)") (class "Default")
      (node (ref "C112") (pin "2") (pinfunction "2_2") (pintype "passive"))
      (node (ref "R114") (pin "2") (pinfunction "2_2") (pintype "passive"))
      (node (ref "R115") (pin "1") (pinfunction "1_1") (pintype "passive"))
    )
    (net (code "126") (name "Net-(CN1-Pad2)") (class "Default")
      (node (ref "CN1") (pin "2") (pinfunction "2_2") (pintype "passive"))
      (node (ref "R43") (pin "1") (pinfunction "1_1") (pintype "passive"))
    )
    (net (code "127") (name "Net-(CN1-Pad3)") (class "Default")
      (node (ref "CN1") (pin "3") (pinfunction "3_3") (pintype "passive"))
      (node (ref "R47") (pin "1") (pinfunction "1_1") (pintype "passive"))
    )
    (net (code "128") (name "Net-(CON1-Pad1)") (class "Default")
      (node (ref "CON1") (pin "1") (pinfunction "1_1") (pintype "passive"))
      (node (ref "R1") (pin "2") (pinfunction "2_2") (pintype "passive"))
      (node (ref "R2") (pin "2") (pinfunction "2_2") (pintype "passive"))
    )
    (net (code "129") (name "Net-(CON6-Pad1)") (class "Default")
      (node (ref "CON6") (pin "1") (pinfunction "1_1") (pintype "passive"))
      (node (ref "R37") (pin "2") (pinfunction "2_2") (pintype "passive"))
      (node (ref "R38") (pin "2") (pinfunction "2_2") (pintype "passive"))
    )
    (net (code "130") (name "Net-(CON_L1-Pad1)") (class "Default")
      (node (ref "CON_L1") (pin "1") (pintype "passive"))
      (node (ref "F1") (pin "1") (pinfunction "1_1") (pintype "passive"))
    )
    (net (code "131") (name "Net-(D1-A)") (class "Default")
      (node (ref "CON2") (pin "1") (pinfunction "1_1") (pintype "passive"))
      (node (ref "D1") (pin "1") (pinfunction "A_1") (pintype "passive"))
      (node (ref "R3") (pin "1") (pinfunction "1_1") (pintype "passive"))
    )
    (net (code "132") (name "Net-(D2-A)") (class "Default")
      (node (ref "CON3") (pin "1") (pinfunction "1_1") (pintype "passive"))
      (node (ref "D2") (pin "1") (pinfunction "A_1") (pintype "passive"))
      (node (ref "R7") (pin "1") (pinfunction "1_1") (pintype "passive"))
    )
    (net (code "133") (name "Net-(D3-A)") (class "Default")
      (node (ref "CON4") (pin "1") (pinfunction "1_1") (pintype "passive"))
      (node (ref "D3") (pin "1") (pinfunction "A_1") (pintype "passive"))
      (node (ref "R15") (pin "1") (pinfunction "1_1") (pintype "passive"))
    )
    (net (code "134") (name "Net-(D4-A)") (class "Default")
      (node (ref "CON5") (pin "1") (pinfunction "1_1") (pintype "passive"))
      (node (ref "D4") (pin "1") (pinfunction "A_1") (pintype "passive"))
      (node (ref "R24") (pin "1") (pinfunction "1_1") (pintype "passive"))
    )
    (net (code "135") (name "Net-(D_STAT1-K)") (class "Default")
      (node (ref "D_STAT1") (pin "2") (pinfunction "K_2") (pintype "passive"))
      (node (ref "R56") (pin "1") (pinfunction "1_1") (pintype "passive"))
    )
    (net (code "136") (name "Net-(TP5-TP?)") (class "Default")
      (node (ref "CON7") (pin "1") (pinfunction "1_1") (pintype "passive"))
      (node (ref "R39") (pin "2") (pinfunction "2_2") (pintype "passive"))
      (node (ref "TP5") (pin "1") (pinfunction "TP?_1") (pintype "passive"))
      (node (ref "U5") (pin "3") (pinfunction "IN+_3") (pintype "passive"))
    )
    (net (code "137") (name "Net-(TP7-TP?)") (class "Default")
      (node (ref "TP7") (pin "1") (pinfunction "TP?_1") (pintype "passive"))
      (node (ref "U6") (pin "25") (pinfunction "PD4(ICP1/ADC8)_25") (pintype "passive"))
    )
    (net (code "138") (name "Net-(TP24-TP?)") (class "Default")
      (node (ref "R122") (pin "1") (pinfunction "1_1") (pintype "passive"))
      (node (ref "TP24") (pin "1") (pinfunction "TP?_1") (pintype "passive"))
      (node (ref "U4") (pin "6") (pinfunction "D1_6") (pintype "passive"))
    )
    (net (code "139") (name "Net-(TP25-TP?)") (class "Default")
      (node (ref "R123") (pin "1") (pinfunction "1_1") (pintype "passive"))
      (node (ref "TP25") (pin "1") (pinfunction "TP?_1") (pintype "passive"))
      (node (ref "U4") (pin "9") (pinfunction "D2_9") (pintype "passive"))
    )
    (net (code "140") (name "Net-(TP26-TP?)") (class "Default")
      (node (ref "CON8") (pin "1") (pinfunction "1_1") (pintype "passive"))
      (node (ref "R80") (pin "1") (pinfunction "1_1") (pintype "passive"))
      (node (ref "TP26") (pin "1") (pinfunction "TP?_1") (pintype "passive"))
    )
    (net (code "141") (name "Net-(TP27-TP?)") (class "Default")
      (node (ref "CON9") (pin "1") (pinfunction "1_1") (pintype "passive"))
      (node (ref "R103") (pin "1") (pinfunction "1_1") (pintype "passive"))
      (node (ref "TP27") (pin "1") (pinfunction "TP?_1") (pintype "passive"))
    )
    (net (code "142") (name "Net-(U1-~-Pad1)") (class "Default")
      (node (ref "U1") (pin "1") (pinfunction "~_1") (pintype "passive"))
      (node (ref "X1") (pin "12") (pinfunction "Sec-_12") (pintype "passive"))
    )
    (net (code "143") (name "Net-(U1-~-Pad2)") (class "Default")
      (node (ref "U1") (pin "2") (pinfunction "~_2") (pintype "passive"))
      (node (ref "X1") (pin "7") (pinfunction "Sec+_7") (pintype "passive"))
    )
    (net (code "144") (name "Net-(U2-IN-)") (class "Default")
      (node (ref "R10") (pin "1") (pinfunction "1_1") (pintype "passive"))
      (node (ref "R9") (pin "2") (pinfunction "2_2") (pintype "passive"))
      (node (ref "U2") (pin "4") (pinfunction "IN-_4") (pintype "passive"))
    )
    (net (code "145") (name "Net-(U2-~{SHDN})") (class "Default")
      (node (ref "R5") (pin "1") (pinfunction "1_1") (pintype "passive"))
      (node (ref "U2") (pin "5") (pinfunction "~{SHDN}_5") (pintype "passive"))
    )
    (net (code "146") (name "Net-(U3-+INA)") (class "Default")
      (node (ref "C15") (pin "1") (pinfunction "1_1") (pintype "passive"))
      (node (ref "R17") (pin "2") (pinfunction "2_2") (pintype "passive"))
      (node (ref "U3") (pin "3") (pinfunction "+INA_3") (pintype "passive"))
    )
    (net (code "147") (name "Net-(U3-+INB)") (class "Default")
      (node (ref "R11") (pin "2") (pinfunction "2_2") (pintype "passive"))
      (node (ref "R14") (pin "1") (pinfunction "1_1") (pintype "passive"))
      (node (ref "U3") (pin "5") (pinfunction "+INB_5") (pintype "passive"))
    )
    (net (code "148") (name "Net-(U3-+INC)") (class "Default")
      (node (ref "R12") (pin "1") (pinfunction "1_1") (pintype "passive"))
      (node (ref "R8") (pin "2") (pinfunction "2_2") (pintype "passive"))
      (node (ref "U3") (pin "12") (pinfunction "+INC_12") (pintype "passive"))
    )
    (net (code "149") (name "Net-(U3-+IND)") (class "Default")
      (node (ref "C20") (pin "1") (pinfunction "1_1") (pintype "passive"))
      (node (ref "R19") (pin "2") (pinfunction "2_2") (pintype "passive"))
      (node (ref "U3") (pin "14") (pinfunction "+IND_14") (pintype "passive"))
    )
    (net (code "150") (name "Net-(U3--INA)") (class "Default")
      (node (ref "C21") (pin "2") (pinfunction "2_2") (pintype "passive"))
      (node (ref "R14") (pin "2") (pinfunction "2_2") (pintype "passive"))
      (node (ref "R20") (pin "1") (pinfunction "1_1") (pintype "passive"))
      (node (ref "U3") (pin "1") (pinfunction "OUTA_1") (pintype "passive"))
      (node (ref "U3") (pin "2") (pinfunction "-INA_2") (pintype "passive"))
    )
    (net (code "151") (name "Net-(U3--INB)") (class "Default")
      (node (ref "C10") (pin "1") (pinfunction "1_1") (pintype "passive"))
      (node (ref "C9") (pin "1") (pinfunction "1_1") (pintype "passive"))
      (node (ref "R22") (pin "1") (pinfunction "1_1") (pintype "passive"))
      (node (ref "R23") (pin "1") (pinfunction "1_1") (pintype "passive"))
      (node (ref "U3") (pin "6") (pinfunction "-INB_6") (pintype "passive"))
      (node (ref "U3") (pin "7") (pinfunction "OUTB_7") (pintype "passive"))
    )
    (net (code "152") (name "Net-(U3--INC)") (class "Default")
      (node (ref "C11") (pin "1") (pinfunction "1_1") (pintype "passive"))
      (node (ref "C12") (pin "1") (pinfunction "1_1") (pintype "passive"))
      (node (ref "R25") (pin "1") (pinfunction "1_1") (pintype "passive"))
      (node (ref "R26") (pin "1") (pinfunction "1_1") (pintype "passive"))
      (node (ref "U3") (pin "10") (pinfunction "OUTC_10") (pintype "passive"))
      (node (ref "U3") (pin "11") (pinfunction "-INC_11") (pintype "passive"))
    )
    (net (code "153") (name "Net-(U4-EN)") (class "Default")
      (node (ref "R34") (pin "2") (pinfunction "2_2") (pintype "passive"))
      (node (ref "U4") (pin "2") (pinfunction "EN_2") (pintype "passive"))
    )
    (net (code "154") (name "Net-(U4-S1B)") (class "Default")
      (node (ref "R121") (pin "2") (pinfunction "2_2") (pintype "passive"))
      (node (ref "U4") (pin "5") (pinfunction "S1B_5") (pintype "passive"))
    )
    (net (code "155") (name "Net-(U4-S2B)") (class "Default")
      (node (ref "R125") (pin "1") (pinfunction "1_1") (pintype "passive"))
      (node (ref "U4") (pin "10") (pinfunction "S2B_10") (pintype "passive"))
    )
    (net (code "156") (name "Net-(U5-IN-)") (class "Default")
      (node (ref "R51") (pin "2") (pinfunction "2_2") (pintype "passive"))
      (node (ref "R52") (pin "1") (pinfunction "1_1") (pintype "passive"))
      (node (ref "U5") (pin "4") (pinfunction "IN-_4") (pintype "passive"))
    )
    (net (code "157") (name "Net-(U5-~{SHDN})") (class "Default")
      (node (ref "R44") (pin "1") (pinfunction "1_1") (pintype "passive"))
      (node (ref "U5") (pin "5") (pinfunction "~{SHDN}_5") (pintype "passive"))
    )
    (net (code "158") (name "Net-(U6-D+)") (class "Default")
      (node (ref "R47") (pin "2") (pinfunction "2_2") (pintype "passive"))
      (node (ref "U6") (pin "4") (pinfunction "D+_4") (pintype "passive"))
    )
    (net (code "159") (name "Net-(U6-D-)") (class "Default")
      (node (ref "R43") (pin "2") (pinfunction "2_2") (pintype "passive"))
      (node (ref "U6") (pin "3") (pinfunction "D-_3") (pintype "passive"))
    )
    (net (code "160") (name "Net-(U6-UCAP)") (class "Default")
      (node (ref "C48") (pin "1") (pinfunction "1_1") (pintype "passive"))
      (node (ref "U6") (pin "6") (pinfunction "UCAP_6") (pintype "passive"))
    )
    (net (code "161") (name "Net-(U6-XTAL1)") (class "Default")
      (node (ref "C41") (pin "1") (pinfunction "1_1") (pintype "passive"))
      (node (ref "U6") (pin "17") (pinfunction "XTAL1_17") (pintype "passive"))
      (node (ref "Y1") (pin "1") (pinfunction "1_1") (pintype "passive"))
    )
    (net (code "162") (name "Net-(U6-XTAL2)") (class "Default")
      (node (ref "C39") (pin "1") (pinfunction "1_1") (pintype "passive"))
      (node (ref "U6") (pin "16") (pinfunction "XTAL2_16") (pintype "passive"))
      (node (ref "Y1") (pin "2") (pinfunction "2_2") (pintype "passive"))
    )
    (net (code "163") (name "Net-(U7-+INA)") (class "Default")
      (node (ref "C38") (pin "1") (pinfunction "1_1") (pintype "passive"))
      (node (ref "R42") (pin "2") (pinfunction "2_2") (pintype "passive"))
      (node (ref "U7") (pin "3") (pinfunction "+INA_3") (pintype "passive"))
    )
    (net (code "164") (name "Net-(U7-+INB)") (class "Default")
      (node (ref "R45") (pin "2") (pinfunction "2_2") (pintype "passive"))
      (node (ref "R48") (pin "1") (pinfunction "1_1") (pintype "passive"))
      (node (ref "U7") (pin "5") (pinfunction "+INB_5") (pintype "passive"))
    )
    (net (code "165") (name "Net-(U7-+INC)") (class "Default")
      (node (ref "R40") (pin "2") (pinfunction "2_2") (pintype "passive"))
      (node (ref "R46") (pin "1") (pinfunction "1_1") (pintype "passive"))
      (node (ref "U7") (pin "12") (pinfunction "+INC_12") (pintype "passive"))
    )
    (net (code "166") (name "Net-(U7-+IND)") (class "Default")
      (node (ref "C46") (pin "1") (pinfunction "1_1") (pintype "passive"))
      (node (ref "R54") (pin "2") (pinfunction "2_2") (pintype "passive"))
      (node (ref "U7") (pin "14") (pinfunction "+IND_14") (pintype "passive"))
    )
    (net (code "167") (name "Net-(U7--INA)") (class "Default")
      (node (ref "C47") (pin "2") (pinfunction "2_2") (pintype "passive"))
      (node (ref "R48") (pin "2") (pinfunction "2_2") (pintype "passive"))
      (node (ref "R55") (pin "1") (pinfunction "1_1") (pintype "passive"))
      (node (ref "U7") (pin "1") (pinfunction "OUTA_1") (pintype "passive"))
      (node (ref "U7") (pin "2") (pinfunction "-INA_2") (pintype "passive"))
    )
    (net (code "168") (name "Net-(U7--INB)") (class "Default")
      (node (ref "C31") (pin "1") (pinfunction "1_1") (pintype "passive"))
      (node (ref "C32") (pin "1") (pinfunction "1_1") (pintype "passive"))
      (node (ref "R49") (pin "1") (pinfunction "1_1") (pintype "passive"))
      (node (ref "R50") (pin "1") (pinfunction "1_1") (pintype "passive"))
      (node (ref "U7") (pin "6") (pinfunction "-INB_6") (pintype "passive"))
      (node (ref "U7") (pin "7") (pinfunction "OUTB_7") (pintype "passive"))
    )
    (net (code "169") (name "Net-(U7--INC)") (class "Default")
      (node (ref "C42") (pin "1") (pinfunction "1_1") (pintype "passive"))
      (node (ref "C43") (pin "1") (pinfunction "1_1") (pintype "passive"))
      (node (ref "R58") (pin "1") (pinfunction "1_1") (pintype "passive"))
      (node (ref "R59") (pin "1") (pinfunction "1_1") (pintype "passive"))
      (node (ref "U7") (pin "10") (pinfunction "OUTC_10") (pintype "passive"))
      (node (ref "U7") (pin "11") (pinfunction "-INC_11") (pintype "passive"))
    )
    (net (code "170") (name "Net-(U10-+INA)") (class "Default")
      (node (ref "C58") (pin "2") (pinfunction "2_2") (pintype "passive"))
      (node (ref "R73") (pin "2") (pinfunction "2_2") (pintype "passive"))
      (node (ref "U10") (pin "3") (pinfunction "+INA_3") (pintype "passive"))
    )
    (net (code "171") (name "Net-(U10-+INB)") (class "Default")
      (node (ref "C68") (pin "2") (pinfunction "2_2") (pintype "passive"))
      (node (ref "R79") (pin "2") (pinfunction "2_2") (pintype "passive"))
      (node (ref "U10") (pin "5") (pinfunction "+INB_5") (pintype "passive"))
    )
    (net (code "172") (name "Net-(U10-+INC)") (class "Default")
      (node (ref "C69") (pin "2") (pinfunction "2_2") (pintype "passive"))
      (node (ref "R83") (pin "1") (pinfunction "1_1") (pintype "passive"))
      (node (ref "U10") (pin "12") (pinfunction "+INC_12") (pintype "passive"))
    )
    (net (code "173") (name "Net-(U10-+IND)") (class "Default")
      (node (ref "C54") (pin "2") (pinfunction "2_2") (pintype "passive"))
      (node (ref "R76") (pin "2") (pinfunction "2_2") (pintype "passive"))
      (node (ref "U10") (pin "14") (pinfunction "+IND_14") (pintype "passive"))
    )
    (net (code "174") (name "Net-(U10--INA)") (class "Default")
      (node (ref "C52") (pin "2") (pinfunction "2_2") (pintype "passive"))
      (node (ref "R78") (pin "1") (pinfunction "1_1") (pintype "passive"))
      (node (ref "U10") (pin "1") (pinfunction "OUTA_1") (pintype "passive"))
      (node (ref "U10") (pin "2") (pinfunction "-INA_2") (pintype "passive"))
    )
    (net (code "175") (name "Net-(U10--IND)") (class "Default")
      (node (ref "R70") (pin "2") (pinfunction "2_2") (pintype "passive"))
      (node (ref "R84") (pin "2") (pinfunction "2_2") (pintype "passive"))
      (node (ref "U10") (pin "15") (pinfunction "-IND_15") (pintype "passive"))
      (node (ref "U10") (pin "16") (pinfunction "OUTD_16") (pintype "passive"))
    )
    (net (code "176") (name "Net-(U11-+INA)") (class "Default")
      (node (ref "C61") (pin "2") (pinfunction "2_2") (pintype "passive"))
      (node (ref "R75") (pin "2") (pinfunction "2_2") (pintype "passive"))
      (node (ref "U11") (pin "3") (pinfunction "+INA_3") (pintype "passive"))
    )
    (net (code "177") (name "Net-(U11-+INB)") (class "Default")
      (node (ref "C70") (pin "2") (pinfunction "2_2") (pintype "passive"))
      (node (ref "R82") (pin "2") (pinfunction "2_2") (pintype "passive"))
      (node (ref "U11") (pin "5") (pinfunction "+INB_5") (pintype "passive"))
    )
    (net (code "178") (name "Net-(U11-+INC)") (class "Default")
      (node (ref "C71") (pin "2") (pinfunction "2_2") (pintype "passive"))
      (node (ref "R85") (pin "1") (pinfunction "1_1") (pintype "passive"))
      (node (ref "U11") (pin "12") (pinfunction "+INC_12") (pintype "passive"))
    )
    (net (code "179") (name "Net-(U11-+IND)") (class "Default")
      (node (ref "C56") (pin "2") (pinfunction "2_2") (pintype "passive"))
      (node (ref "R77") (pin "2") (pinfunction "2_2") (pintype "passive"))
      (node (ref "U11") (pin "14") (pinfunction "+IND_14") (pintype "passive"))
    )
    (net (code "180") (name "Net-(U11--INA)") (class "Default")
      (node (ref "C53") (pin "2") (pinfunction "2_2") (pintype "passive"))
      (node (ref "R81") (pin "1") (pinfunction "1_1") (pintype "passive"))
      (node (ref "U11") (pin "1") (pinfunction "OUTA_1") (pintype "passive"))
      (node (ref "U11") (pin "2") (pinfunction "-INA_2") (pintype "passive"))
    )
    (net (code "181") (name "Net-(U11--IND)") (class "Default")
      (node (ref "R71") (pin "2") (pinfunction "2_2") (pintype "passive"))
      (node (ref "R86") (pin "2") (pinfunction "2_2") (pintype "passive"))
      (node (ref "U11") (pin "15") (pinfunction "-IND_15") (pintype "passive"))
      (node (ref "U11") (pin "16") (pinfunction "OUTD_16") (pintype "passive"))
    )
    (net (code "182") (name "Net-(U12-IN+)") (class "Default")
      (node (ref "R126") (pin "1") (pinfunction "1_1") (pintype "passive"))
      (node (ref "R127") (pin "1") (pinfunction "1_1") (pintype "passive"))
      (node (ref "U12") (pin "12") (pinfunction "IN+_12") (pintype "passive"))
    )
    (net (code "183") (name "Net-(U12-VOUT)") (class "Default")
      (node (ref "R80") (pin "2") (pinfunction "2_2") (pintype "passive"))
      (node (ref "U12") (pin "13") (pinfunction "VOUT_13") (pintype "passive"))
    )
    (net (code "184") (name "Net-(U13-+INA)") (class "Default")
      (node (ref "C74") (pin "1") (pinfunction "1_1") (pintype "passive"))
      (node (ref "R91") (pin "2") (pinfunction "2_2") (pintype "passive"))
      (node (ref "U13") (pin "3") (pinfunction "+INA_3") (pintype "passive"))
    )
    (net (code "185") (name "Net-(U13-+INB)") (class "Default")
      (node (ref "C85") (pin "2") (pinfunction "2_2") (pintype "passive"))
      (node (ref "R96") (pin "2") (pinfunction "2_2") (pintype "passive"))
      (node (ref "U13") (pin "5") (pinfunction "+INB_5") (pintype "passive"))
    )
    (net (code "186") (name "Net-(U13-+INC)") (class "Default")
      (node (ref "C91") (pin "2") (pinfunction "2_2") (pintype "passive"))
      (node (ref "R97") (pin "1") (pinfunction "1_1") (pintype "passive"))
      (node (ref "U13") (pin "12") (pinfunction "+INC_12") (pintype "passive"))
    )
    (net (code "187") (name "Net-(U13-+IND)") (class "Default")
      (node (ref "C75") (pin "2") (pinfunction "2_2") (pintype "passive"))
      (node (ref "R92") (pin "2") (pinfunction "2_2") (pintype "passive"))
      (node (ref "U13") (pin "14") (pinfunction "+IND_14") (pintype "passive"))
    )
    (net (code "188") (name "Net-(U13--INA)") (class "Default")
      (node (ref "R89") (pin "2") (pinfunction "2_2") (pintype "passive"))
      (node (ref "R95") (pin "1") (pinfunction "1_1") (pintype "passive"))
      (node (ref "U13") (pin "1") (pinfunction "OUTA_1") (pintype "passive"))
      (node (ref "U13") (pin "2") (pinfunction "-INA_2") (pintype "passive"))
    )
    (net (code "189") (name "Net-(U13--IND)") (class "Default")
      (node (ref "R87") (pin "2") (pinfunction "2_2") (pintype "passive"))
      (node (ref "R98") (pin "2") (pinfunction "2_2") (pintype "passive"))
      (node (ref "U13") (pin "15") (pinfunction "-IND_15") (pintype "passive"))
      (node (ref "U13") (pin "16") (pinfunction "OUTD_16") (pintype "passive"))
    )
    (net (code "190") (name "Net-(U14-+INA)") (class "Default")
      (node (ref "C78") (pin "1") (pinfunction "1_1") (pintype "passive"))
      (node (ref "R93") (pin "2") (pinfunction "2_2") (pintype "passive"))
      (node (ref "U14") (pin "3") (pinfunction "+INA_3") (pintype "passive"))
    )
    (net (code "191") (name "Net-(U14-+INB)") (class "Default")
      (node (ref "C92") (pin "2") (pinfunction "2_2") (pintype "passive"))
      (node (ref "R100") (pin "2") (pinfunction "2_2") (pintype "passive"))
      (node (ref "U14") (pin "5") (pinfunction "+INB_5") (pintype "passive"))
    )
    (net (code "192") (name "Net-(U14-+INC)") (class "Default")
      (node (ref "C93") (pin "2") (pinfunction "2_2") (pintype "passive"))
      (node (ref "R101") (pin "1") (pinfunction "1_1") (pintype "passive"))
      (node (ref "U14") (pin "12") (pinfunction "+INC_12") (pintype "passive"))
    )
    (net (code "193") (name "Net-(U14-+IND)") (class "Default")
      (node (ref "C79") (pin "2") (pinfunction "2_2") (pintype "passive"))
      (node (ref "R94") (pin "2") (pinfunction "2_2") (pintype "passive"))
      (node (ref "U14") (pin "14") (pinfunction "+IND_14") (pintype "passive"))
    )
    (net (code "194") (name "Net-(U14--INA)") (class "Default")
      (node (ref "R90") (pin "2") (pinfunction "2_2") (pintype "passive"))
      (node (ref "R99") (pin "1") (pinfunction "1_1") (pintype "passive"))
      (node (ref "U14") (pin "1") (pinfunction "OUTA_1") (pintype "passive"))
      (node (ref "U14") (pin "2") (pinfunction "-INA_2") (pintype "passive"))
    )
    (net (code "195") (name "Net-(U14--IND)") (class "Default")
      (node (ref "R102") (pin "2") (pinfunction "2_2") (pintype "passive"))
      (node (ref "R88") (pin "2") (pinfunction "2_2") (pintype "passive"))
      (node (ref "U14") (pin "15") (pinfunction "-IND_15") (pintype "passive"))
      (node (ref "U14") (pin "16") (pinfunction "OUTD_16") (pintype "passive"))
    )
    (net (code "196") (name "Net-(U15-IN+)") (class "Default")
      (node (ref "R128") (pin "1") (pinfunction "1_1") (pintype "passive"))
      (node (ref "R129") (pin "1") (pinfunction "1_1") (pintype "passive"))
      (node (ref "U15") (pin "12") (pinfunction "IN+_12") (pintype "passive"))
    )
    (net (code "197") (name "Net-(U15-VOUT)") (class "Default")
      (node (ref "R103") (pin "2") (pinfunction "2_2") (pintype "passive"))
      (node (ref "U15") (pin "13") (pinfunction "VOUT_13") (pintype "passive"))
    )
    (net (code "198") (name "Net-(U16-+INA)") (class "Default")
      (node (ref "C95") (pin "1") (pinfunction "1_1") (pintype "passive"))
      (node (ref "R108") (pin "2") (pinfunction "2_2") (pintype "passive"))
      (node (ref "U16") (pin "3") (pinfunction "+INA_3") (pintype "passive"))
    )
    (net (code "199") (name "Net-(U16-+INB)") (class "Default")
      (node (ref "C113") (pin "2") (pinfunction "2_2") (pintype "passive"))
      (node (ref "R113") (pin "2") (pinfunction "2_2") (pintype "passive"))
      (node (ref "U16") (pin "5") (pinfunction "+INB_5") (pintype "passive"))
    )
    (net (code "200") (name "Net-(U16-+INC)") (class "Default")
      (node (ref "C107") (pin "2") (pinfunction "2_2") (pintype "passive"))
      (node (ref "R118") (pin "2") (pinfunction "2_2") (pintype "passive"))
      (node (ref "U16") (pin "12") (pinfunction "+INC_12") (pintype "passive"))
    )
    (net (code "201") (name "Net-(U16-+IND)") (class "Default")
      (node (ref "C96") (pin "2") (pinfunction "2_2") (pintype "passive"))
      (node (ref "R109") (pin "2") (pinfunction "2_2") (pintype "passive"))
      (node (ref "U16") (pin "14") (pinfunction "+IND_14") (pintype "passive"))
    )
    (net (code "202") (name "Net-(U16--INA)") (class "Default")
      (node (ref "R105") (pin "2") (pinfunction "2_2") (pintype "passive"))
      (node (ref "R112") (pin "1") (pinfunction "1_1") (pintype "passive"))
      (node (ref "U16") (pin "1") (pinfunction "OUTA_1") (pintype "passive"))
      (node (ref "U16") (pin "2") (pinfunction "-INA_2") (pintype "passive"))
    )
    (net (code "203") (name "Net-(U16--IND)") (class "Default")
      (node (ref "C108") (pin "1") (pinfunction "1_1") (pintype "passive"))
      (node (ref "R104") (pin "2") (pinfunction "2_2") (pintype "passive"))
      (node (ref "U16") (pin "15") (pinfunction "-IND_15") (pintype "passive"))
      (node (ref "U16") (pin "16") (pinfunction "OUTD_16") (pintype "passive"))
    )
    (net (code "204") (name "Net-(U17-+INA)") (class "Default")
      (node (ref "C99") (pin "1") (pinfunction "1_1") (pintype "passive"))
      (node (ref "R110") (pin "2") (pinfunction "2_2") (pintype "passive"))
      (node (ref "U17") (pin "3") (pinfunction "+INA_3") (pintype "passive"))
    )
    (net (code "205") (name "Net-(U17-+INB)") (class "Default")
      (node (ref "C114") (pin "2") (pinfunction "2_2") (pintype "passive"))
      (node (ref "R115") (pin "2") (pinfunction "2_2") (pintype "passive"))
      (node (ref "U17") (pin "5") (pinfunction "+INB_5") (pintype "passive"))
    )
    (net (code "206") (name "Net-(U17-+INC)") (class "Default")
      (node (ref "C109") (pin "2") (pinfunction "2_2") (pintype "passive"))
      (node (ref "R119") (pin "2") (pinfunction "2_2") (pintype "passive"))
      (node (ref "U17") (pin "12") (pinfunction "+INC_12") (pintype "passive"))
    )
    (net (code "207") (name "Net-(U17-+IND)") (class "Default")
      (node (ref "C100") (pin "2") (pinfunction "2_2") (pintype "passive"))
      (node (ref "R111") (pin "2") (pinfunction "2_2") (pintype "passive"))
      (node (ref "U17") (pin "14") (pinfunction "+IND_14") (pintype "passive"))
    )
    (net (code "208") (name "Net-(U17--INA)") (class "Default")
      (node (ref "R107") (pin "2") (pinfunction "2_2") (pintype "passive"))
      (node (ref "R114") (pin "1") (pinfunction "1_1") (pintype "passive"))
      (node (ref "U17") (pin "1") (pinfunction "OUTA_1") (pintype "passive"))
      (node (ref "U17") (pin "2") (pinfunction "-INA_2") (pintype "passive"))
    )
    (net (code "209") (name "Net-(U17--IND)") (class "Default")
      (node (ref "C110") (pin "1") (pinfunction "1_1") (pintype "passive"))
      (node (ref "R106") (pin "2") (pinfunction "2_2") (pintype "passive"))
      (node (ref "U17") (pin "15") (pinfunction "-IND_15") (pintype "passive"))
      (node (ref "U17") (pin "16") (pinfunction "OUTD_16") (pintype "passive"))
    )
    (net (code "210") (name "Net-(U18-S1)") (class "Default")
      (node (ref "R130") (pin "1") (pinfunction "1_1") (pintype "passive"))
      (node (ref "U18") (pin "4") (pinfunction "S1_4") (pintype "passive"))
    )
    (net (code "211") (name "Net-(U18-S2)") (class "Default")
      (node (ref "R134") (pin "1") (pinfunction "1_1") (pintype "passive"))
      (node (ref "U18") (pin "5") (pinfunction "S2_5") (pintype "passive"))
    )
    (net (code "212") (name "Net-(U18-S3)") (class "Default")
      (node (ref "R132") (pin "1") (pinfunction "1_1") (pintype "passive"))
      (node (ref "U18") (pin "6") (pinfunction "S3_6") (pintype "passive"))
    )
    (net (code "213") (name "Net-(U18-S4)") (class "Default")
      (node (ref "R138") (pin "1") (pinfunction "1_1") (pintype "passive"))
      (node (ref "U18") (pin "7") (pinfunction "S4_7") (pintype "passive"))
    )
    (net (code "214") (name "Net-(U18-S5)") (class "Default")
      (node (ref "R140") (pin "1") (pinfunction "1_1") (pintype "passive"))
      (node (ref "U18") (pin "12") (pinfunction "S5_12") (pintype "passive"))
    )
    (net (code "215") (name "Net-(U18-S6)") (class "Default")
      (node (ref "R142") (pin "1") (pinfunction "1_1") (pintype "passive"))
      (node (ref "U18") (pin "11") (pinfunction "S6_11") (pintype "passive"))
    )
    (net (code "216") (name "Net-(U18-S7)") (class "Default")
      (node (ref "R136") (pin "1") (pinfunction "1_1") (pintype "passive"))
      (node (ref "U18") (pin "10") (pinfunction "S7_10") (pintype "passive"))
    )
    (net (code "217") (name "Net-(U19-S1)") (class "Default")
      (node (ref "R143") (pin "1") (pinfunction "1_1") (pintype "passive"))
      (node (ref "U19") (pin "4") (pinfunction "S1_4") (pintype "passive"))
    )
    (net (code "218") (name "Net-(U19-S2)") (class "Default")
      (node (ref "R141") (pin "1") (pinfunction "1_1") (pintype "passive"))
      (node (ref "U19") (pin "5") (pinfunction "S2_5") (pintype "passive"))
    )
    (net (code "219") (name "Net-(U19-S3)") (class "Default")
      (node (ref "R139") (pin "1") (pinfunction "1_1") (pintype "passive"))
      (node (ref "U19") (pin "6") (pinfunction "S3_6") (pintype "passive"))
    )
    (net (code "220") (name "Net-(U19-S4)") (class "Default")
      (node (ref "R137") (pin "1") (pinfunction "1_1") (pintype "passive"))
      (node (ref "U19") (pin "7") (pinfunction "S4_7") (pintype "passive"))
    )
    (net (code "221") (name "Net-(U19-S5)") (class "Default")
      (node (ref "R131") (pin "1") (pinfunction "1_1") (pintype "passive"))
      (node (ref "U19") (pin "12") (pinfunction "S5_12") (pintype "passive"))
    )
    (net (code "222") (name "Net-(U19-S6)") (class "Default")
      (node (ref "R133") (pin "1") (pinfunction "1_1") (pintype "passive"))
      (node (ref "U19") (pin "11") (pinfunction "S6_11") (pintype "passive"))
    )
    (net (code "223") (name "Net-(U19-S7)") (class "Default")
      (node (ref "R135") (pin "1") (pinfunction "1_1") (pintype "passive"))
      (node (ref "U19") (pin "10") (pinfunction "S7_10") (pintype "passive"))
    )
    (net (code "224") (name "Net-(VR1-ADJ)") (class "Default")
      (node (ref "R4") (pin "2") (pinfunction "2_2") (pintype "passive"))
      (node (ref "R6") (pin "2") (pinfunction "2_2") (pintype "passive"))
      (node (ref "VR1") (pin "2") (pinfunction "ADJ_2") (pintype "passive"))
    )
    (net (code "225") (name "Net-(VR2-ADJ)") (class "Default")
      (node (ref "R13") (pin "2") (pinfunction "2_2") (pintype "passive"))
      (node (ref "R18") (pin "1") (pinfunction "1_1") (pintype "passive"))
      (node (ref "VR2") (pin "2") (pinfunction "ADJ_2") (pintype "passive"))
    )
    (net (code "226") (name "Net-(VR3-ADJ)") (class "Default")
      (node (ref "R21") (pin "2") (pinfunction "2_2") (pintype "passive"))
      (node (ref "R28") (pin "1") (pinfunction "1_1") (pintype "passive"))
      (node (ref "VR3") (pin "2") (pinfunction "ADJ_2") (pintype "passive"))
    )
    (net (code "227") (name "Net-(VR4-ADJ)") (class "Default")
      (node (ref "R35") (pin "1") (pinfunction "1_1") (pintype "passive"))
      (node (ref "R36") (pin "1") (pinfunction "1_1") (pintype "passive"))
      (node (ref "VR4") (pin "2") (pinfunction "ADJ_2") (pintype "passive"))
    )
    (net (code "228") (name "Net-(X1-Pri+-Pad4)") (class "Default")
      (node (ref "X1") (pin "3") (pinfunction "Pri-_3") (pintype "passive"))
      (node (ref "X1") (pin "4") (pinfunction "Pri+_4") (pintype "passive"))
    )
    (net (code "229") (name "VUSB") (class "Default")
      (node (ref "CN1") (pin "1") (pinfunction "1_1") (pintype "passive"))
      (node (ref "U6") (pin "2") (pinfunction "UVCC_2") (pintype "passive"))
      (node (ref "U6") (pin "7") (pinfunction "VBUS_7") (pintype "passive"))
    )
    (net (code "230") (name "unconnected-(CN1-Pad4)") (class "Default")
      (node (ref "CN1") (pin "4") (pinfunction "4_4") (pintype "passive"))
    )
    (net (code "231") (name "unconnected-(SW1-I10-Pad10)") (class "Default")
      (node (ref "SW1") (pin "10") (pinfunction "I10_10") (pintype "passive+no_connect"))
    )
    (net (code "232") (name "unconnected-(SW1-O10-Pad11)") (class "Default")
      (node (ref "SW1") (pin "11") (pinfunction "O10_11") (pintype "passive+no_connect"))
    )
    (net (code "233") (name "unconnected-(U3-NC-Pad8)") (class "Default")
      (node (ref "U3") (pin "8") (pinfunction "NC_8") (pintype "passive"))
    )
    (net (code "234") (name "unconnected-(U3-NC-Pad9)") (class "Default")
      (node (ref "U3") (pin "9") (pinfunction "NC_9") (pintype "passive"))
    )
    (net (code "235") (name "unconnected-(U4-NC-Pad7)") (class "Default")
      (node (ref "U4") (pin "7") (pinfunction "NC_7") (pintype "passive"))
    )
    (net (code "236") (name "unconnected-(U4-NC-Pad8)") (class "Default")
      (node (ref "U4") (pin "8") (pinfunction "NC_8") (pintype "passive"))
    )
    (net (code "237") (name "unconnected-(U7-NC-Pad8)") (class "Default")
      (node (ref "U7") (pin "8") (pinfunction "NC_8") (pintype "passive"))
    )
    (net (code "238") (name "unconnected-(U7-NC-Pad9)") (class "Default")
      (node (ref "U7") (pin "9") (pinfunction "NC_9") (pintype "passive"))
    )
    (net (code "239") (name "unconnected-(U10-NC-Pad8)") (class "Default")
      (node (ref "U10") (pin "8") (pinfunction "NC_8") (pintype "passive"))
    )
    (net (code "240") (name "unconnected-(U10-NC-Pad9)") (class "Default")
      (node (ref "U10") (pin "9") (pinfunction "NC_9") (pintype "passive"))
    )
    (net (code "241") (name "unconnected-(U11-NC-Pad8)") (class "Default")
      (node (ref "U11") (pin "8") (pinfunction "NC_8") (pintype "passive"))
    )
    (net (code "242") (name "unconnected-(U11-NC-Pad9)") (class "Default")
      (node (ref "U11") (pin "9") (pinfunction "NC_9") (pintype "passive"))
    )
    (net (code "243") (name "unconnected-(U12-NC-Pad1)") (class "Default")
      (node (ref "U12") (pin "1") (pinfunction "NC_1") (pintype "passive"))
    )
    (net (code "244") (name "unconnected-(U12-NC-Pad9)") (class "Default")
      (node (ref "U12") (pin "9") (pinfunction "NC_9") (pintype "passive"))
    )
    (net (code "245") (name "unconnected-(U12-NC-Pad14)") (class "Default")
      (node (ref "U12") (pin "14") (pinfunction "NC_14") (pintype "passive"))
    )
    (net (code "246") (name "unconnected-(U12-SDO-Pad6)") (class "Default")
      (node (ref "U12") (pin "6") (pinfunction "SDO_6") (pintype "passive"))
    )
    (net (code "247") (name "unconnected-(U13-NC-Pad8)") (class "Default")
      (node (ref "U13") (pin "8") (pinfunction "NC_8") (pintype "passive"))
    )
    (net (code "248") (name "unconnected-(U13-NC-Pad9)") (class "Default")
      (node (ref "U13") (pin "9") (pinfunction "NC_9") (pintype "passive"))
    )
    (net (code "249") (name "unconnected-(U14-NC-Pad8)") (class "Default")
      (node (ref "U14") (pin "8") (pinfunction "NC_8") (pintype "passive"))
    )
    (net (code "250") (name "unconnected-(U14-NC-Pad9)") (class "Default")
      (node (ref "U14") (pin "9") (pinfunction "NC_9") (pintype "passive"))
    )
    (net (code "251") (name "unconnected-(U15-NC-Pad1)") (class "Default")
      (node (ref "U15") (pin "1") (pinfunction "NC_1") (pintype "passive"))
    )
    (net (code "252") (name "unconnected-(U15-NC-Pad9)") (class "Default")
      (node (ref "U15") (pin "9") (pinfunction "NC_9") (pintype "passive"))
    )
    (net (code "253") (name "unconnected-(U15-NC-Pad14)") (class "Default")
      (node (ref "U15") (pin "14") (pinfunction "NC_14") (pintype "passive"))
    )
    (net (code "254") (name "unconnected-(U15-SDO-Pad6)") (class "Default")
      (node (ref "U15") (pin "6") (pinfunction "SDO_6") (pintype "passive"))
    )
    (net (code "255") (name "unconnected-(U16-NC-Pad8)") (class "Default")
      (node (ref "U16") (pin "8") (pinfunction "NC_8") (pintype "passive"))
    )
    (net (code "256") (name "unconnected-(U16-NC-Pad9)") (class "Default")
      (node (ref "U16") (pin "9") (pinfunction "NC_9") (pintype "passive"))
    )
    (net (code "257") (name "unconnected-(U17-NC-Pad8)") (class "Default")
      (node (ref "U17") (pin "8") (pinfunction "NC_8") (pintype "passive"))
    )
    (net (code "258") (name "unconnected-(U17-NC-Pad9)") (class "Default")
      (node (ref "U17") (pin "9") (pinfunction "NC_9") (pintype "passive"))
    )
  )
)
